# UFBmod_2V2.net
KiCad netlist of a schematic drawn in EAGLE
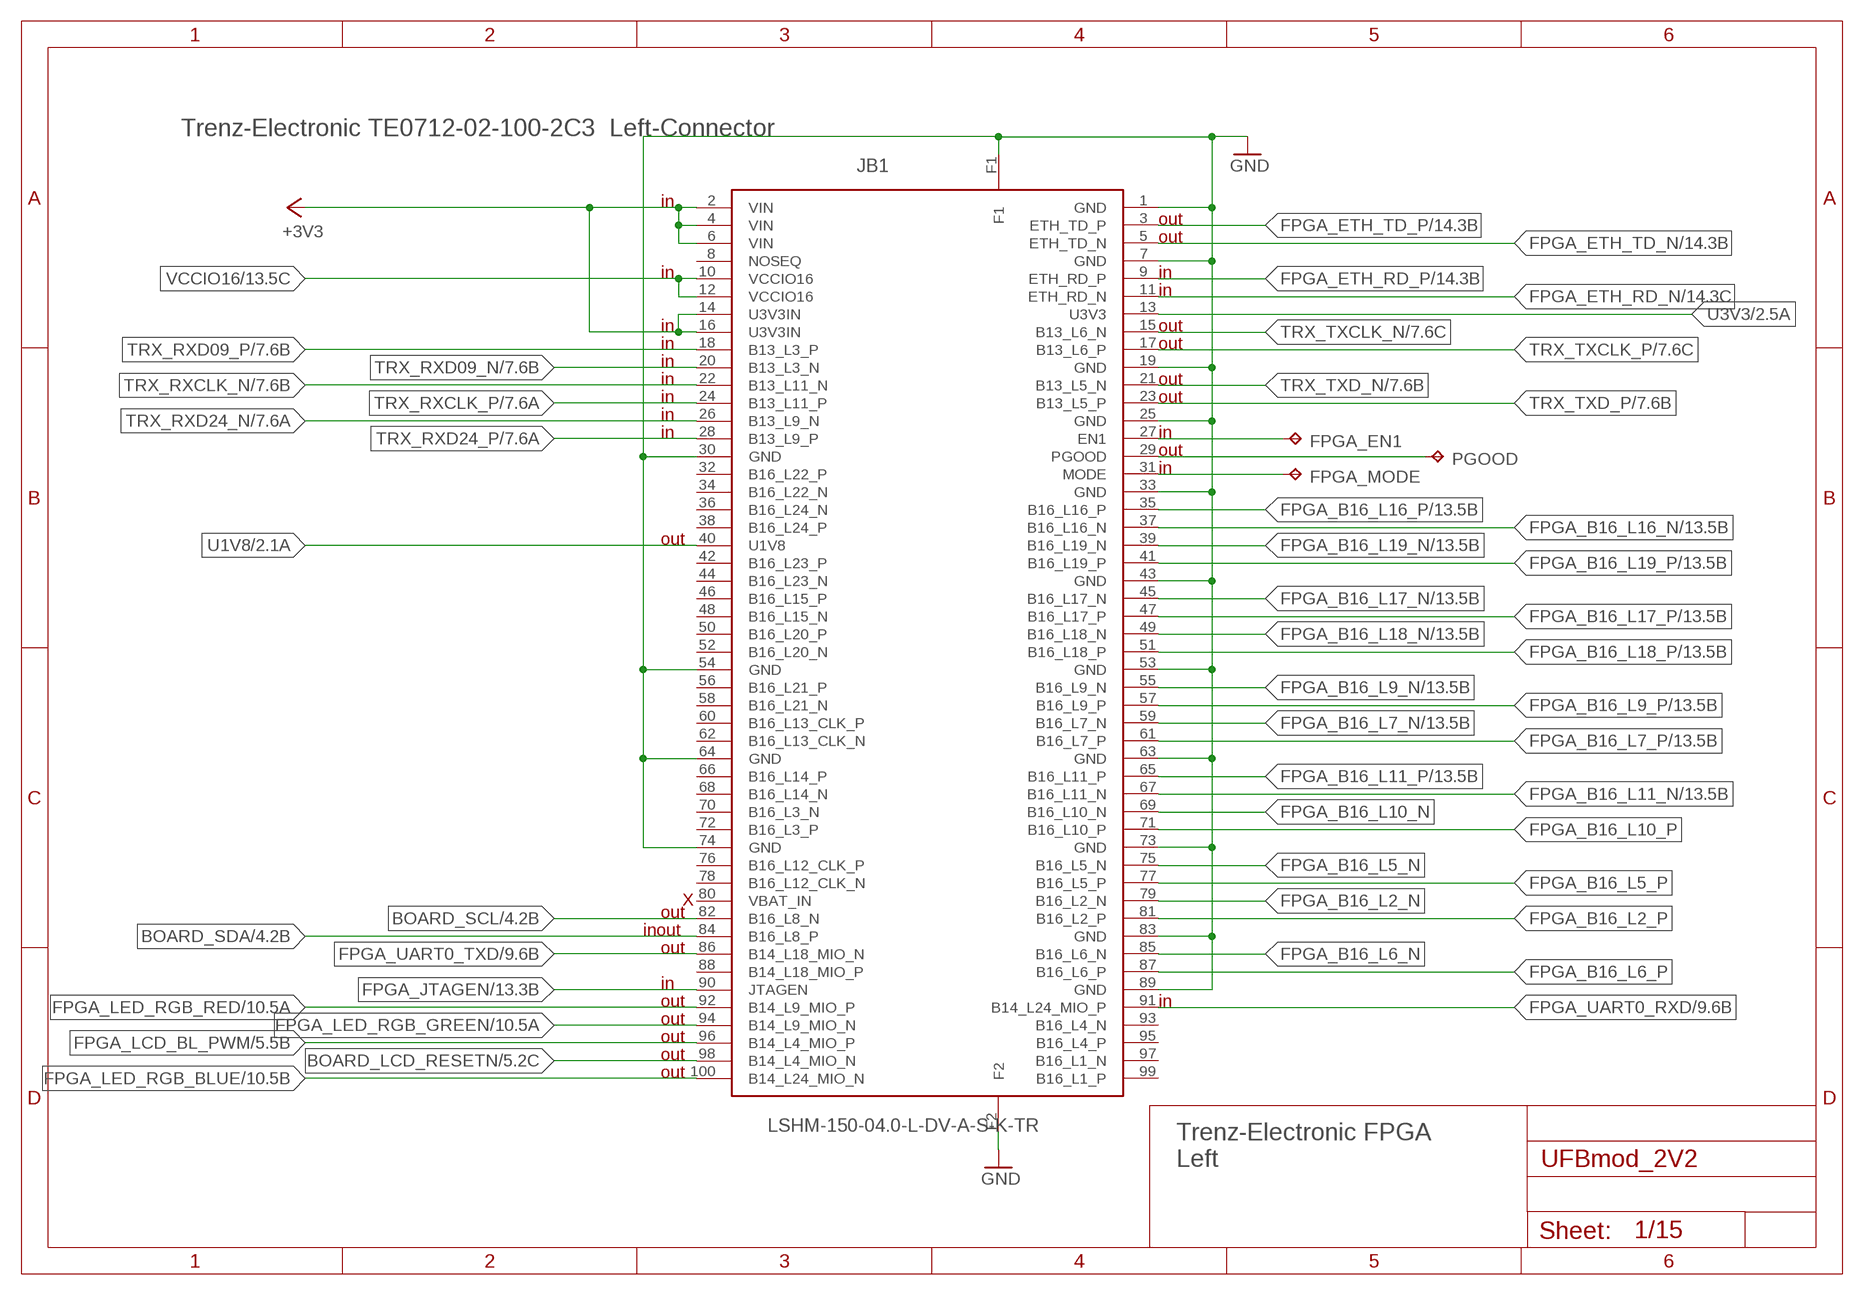
[diagram p0: schematic, sheet 1]
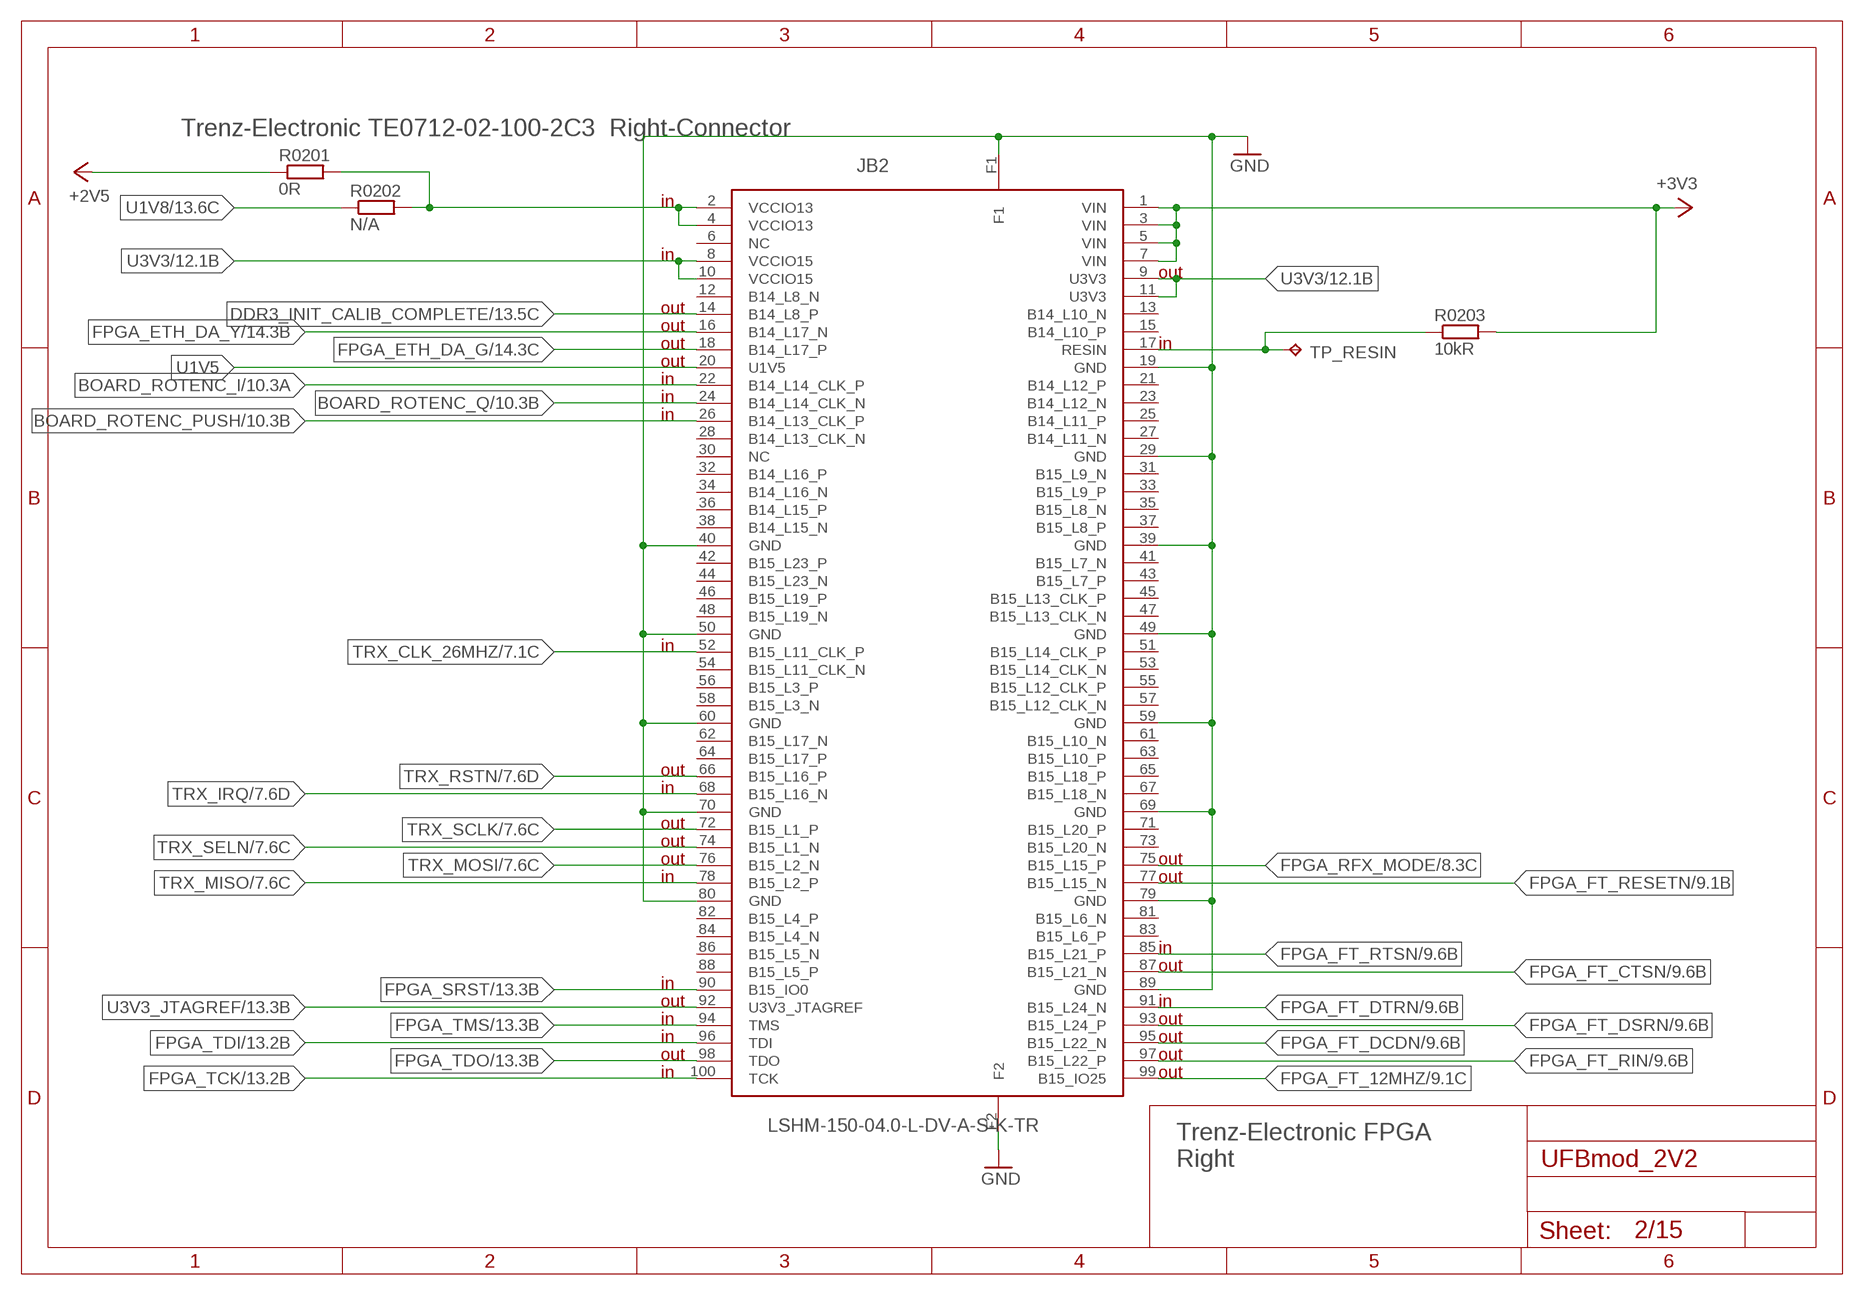
[diagram p1: schematic, sheet 2]
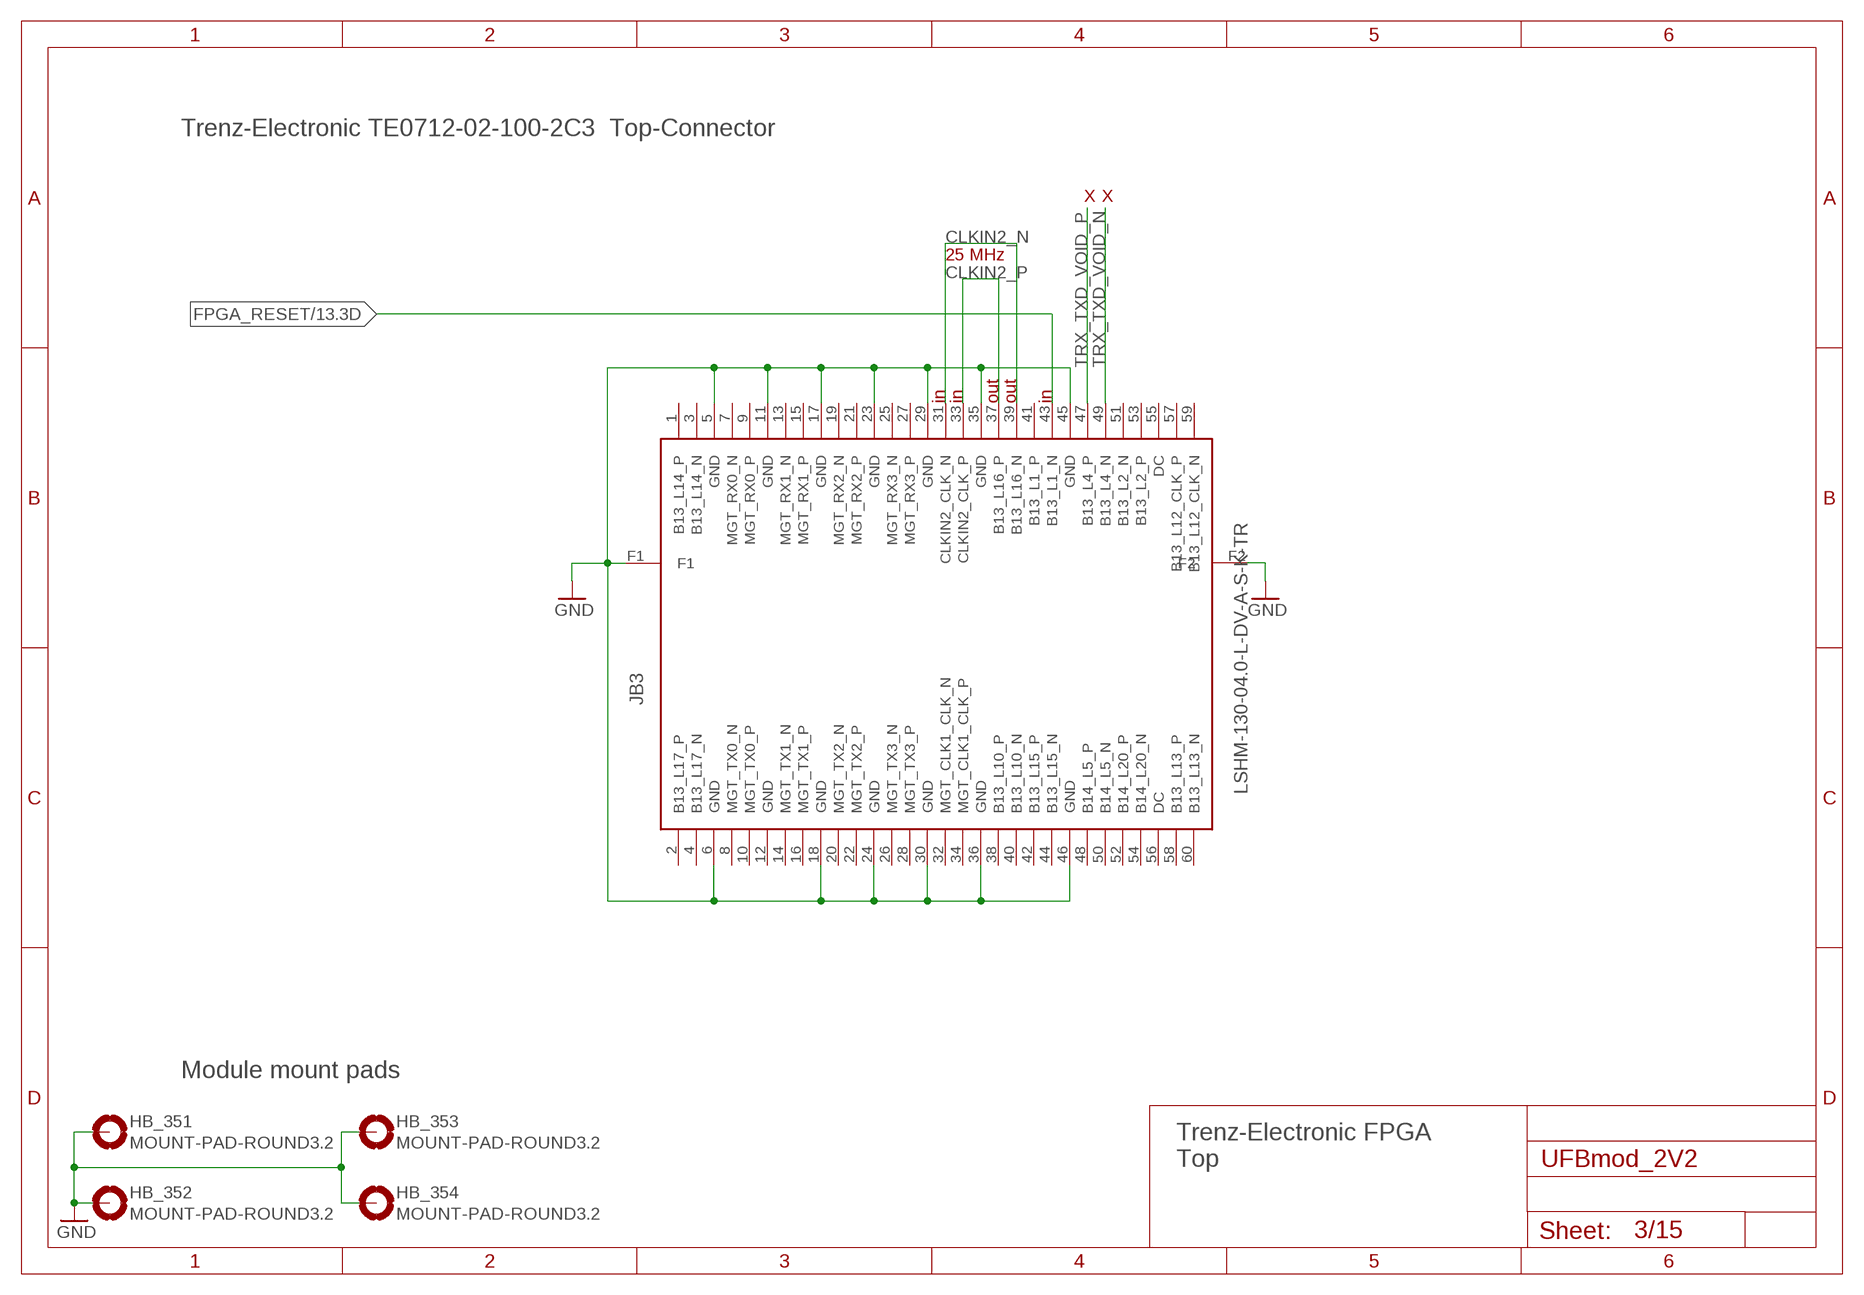
[diagram p2: schematic, sheet 3]
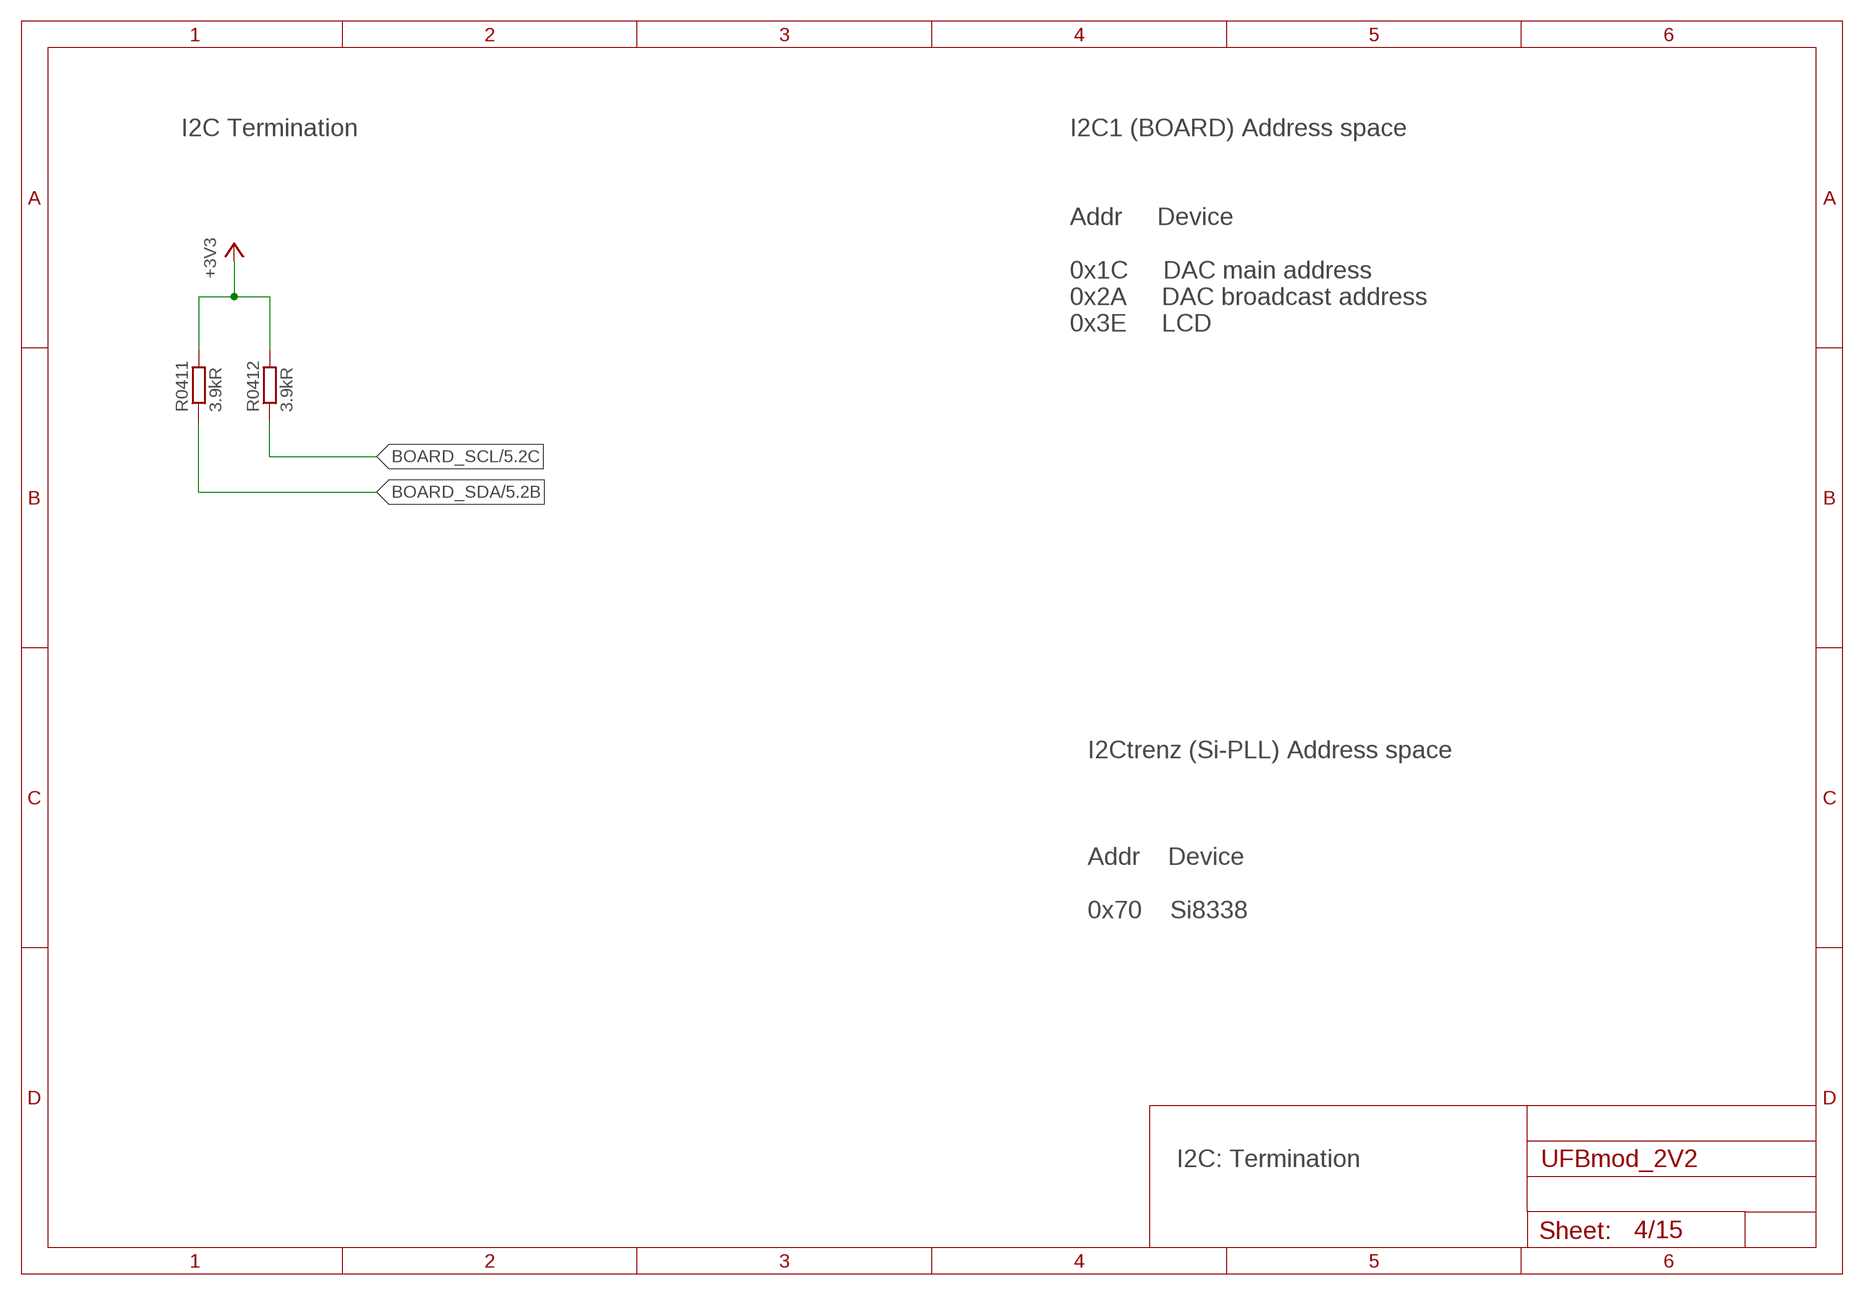
[diagram p3: schematic, sheet 4]
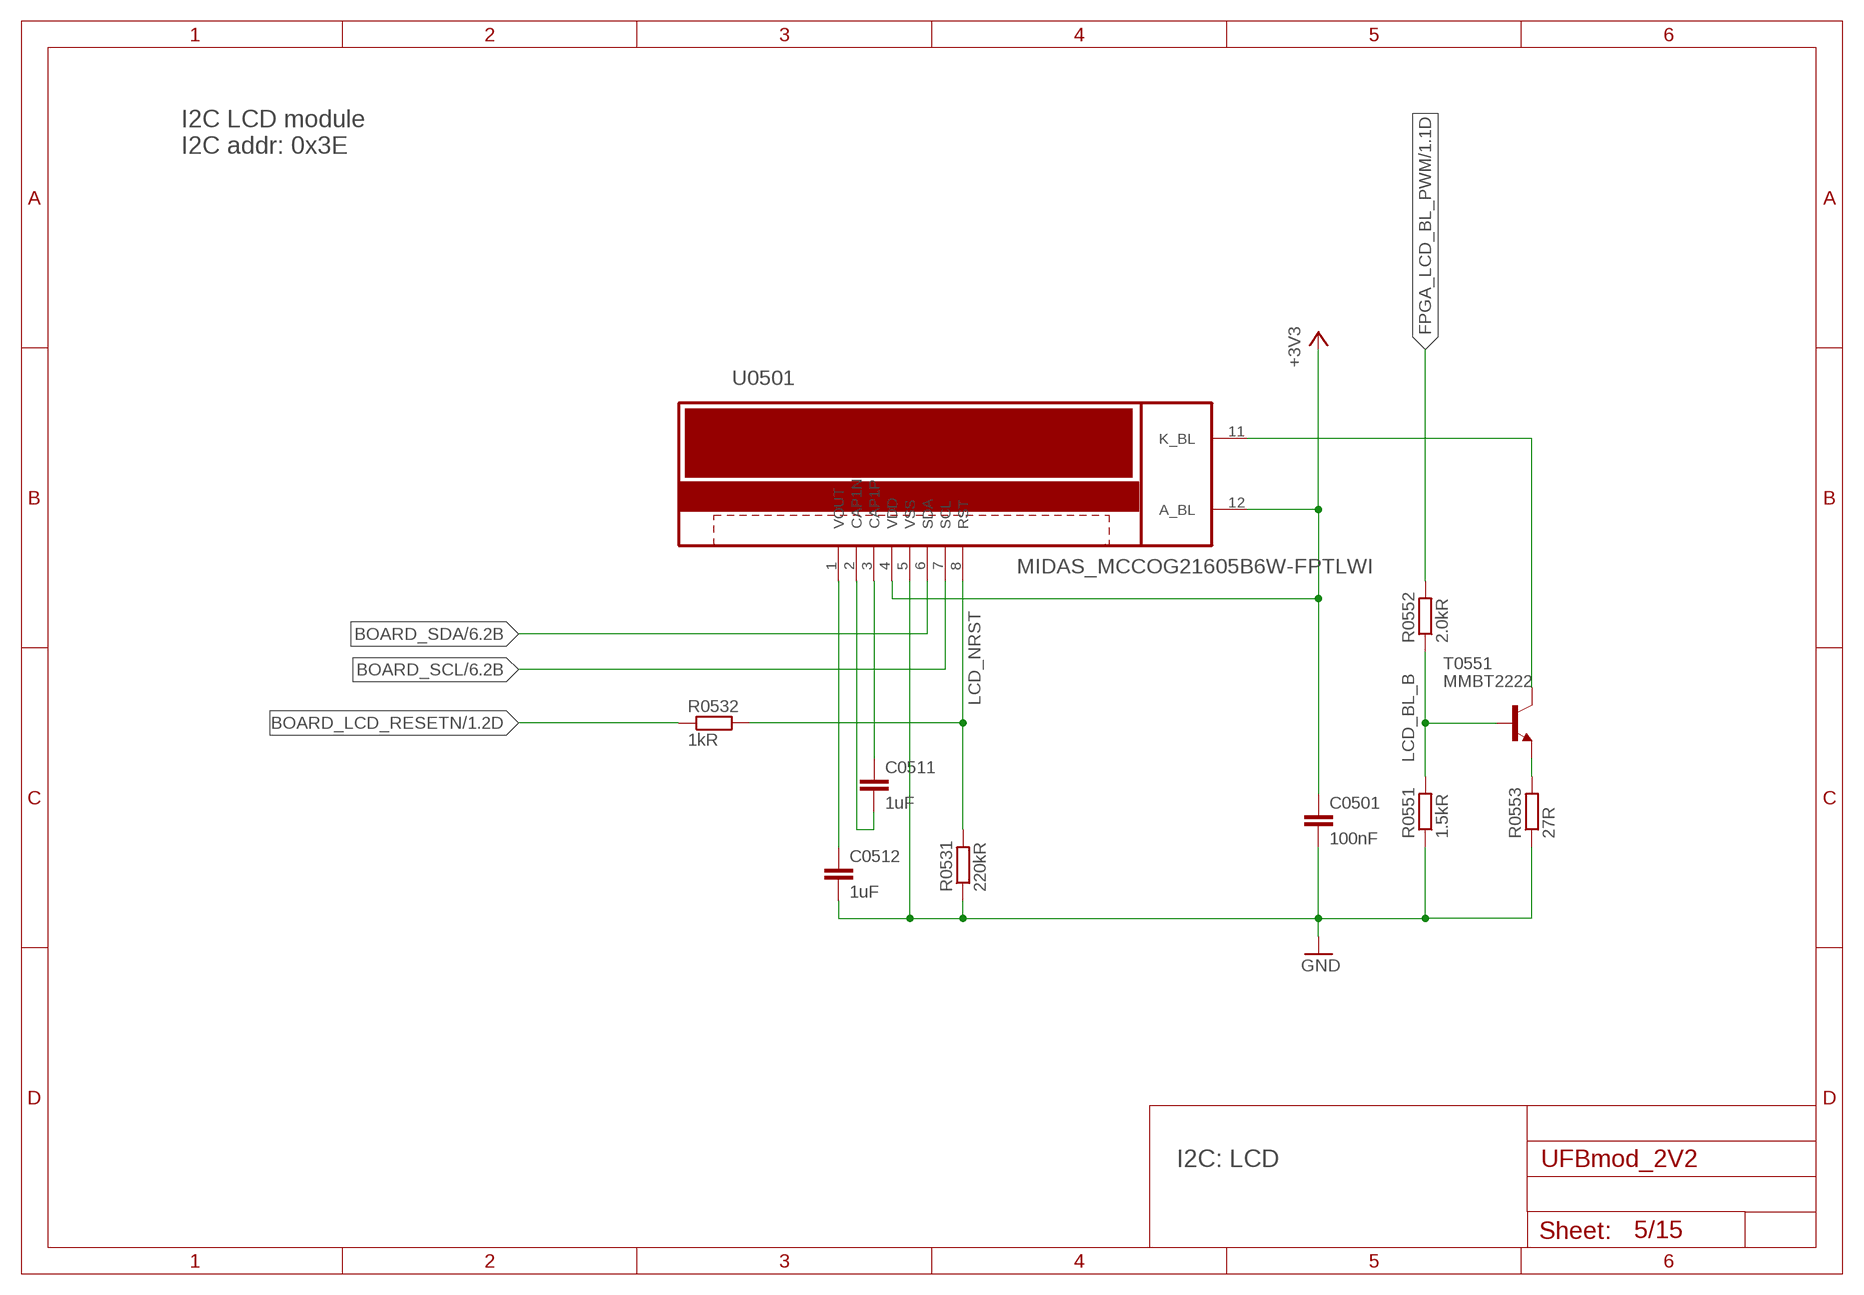
[diagram p4: schematic, sheet 5]
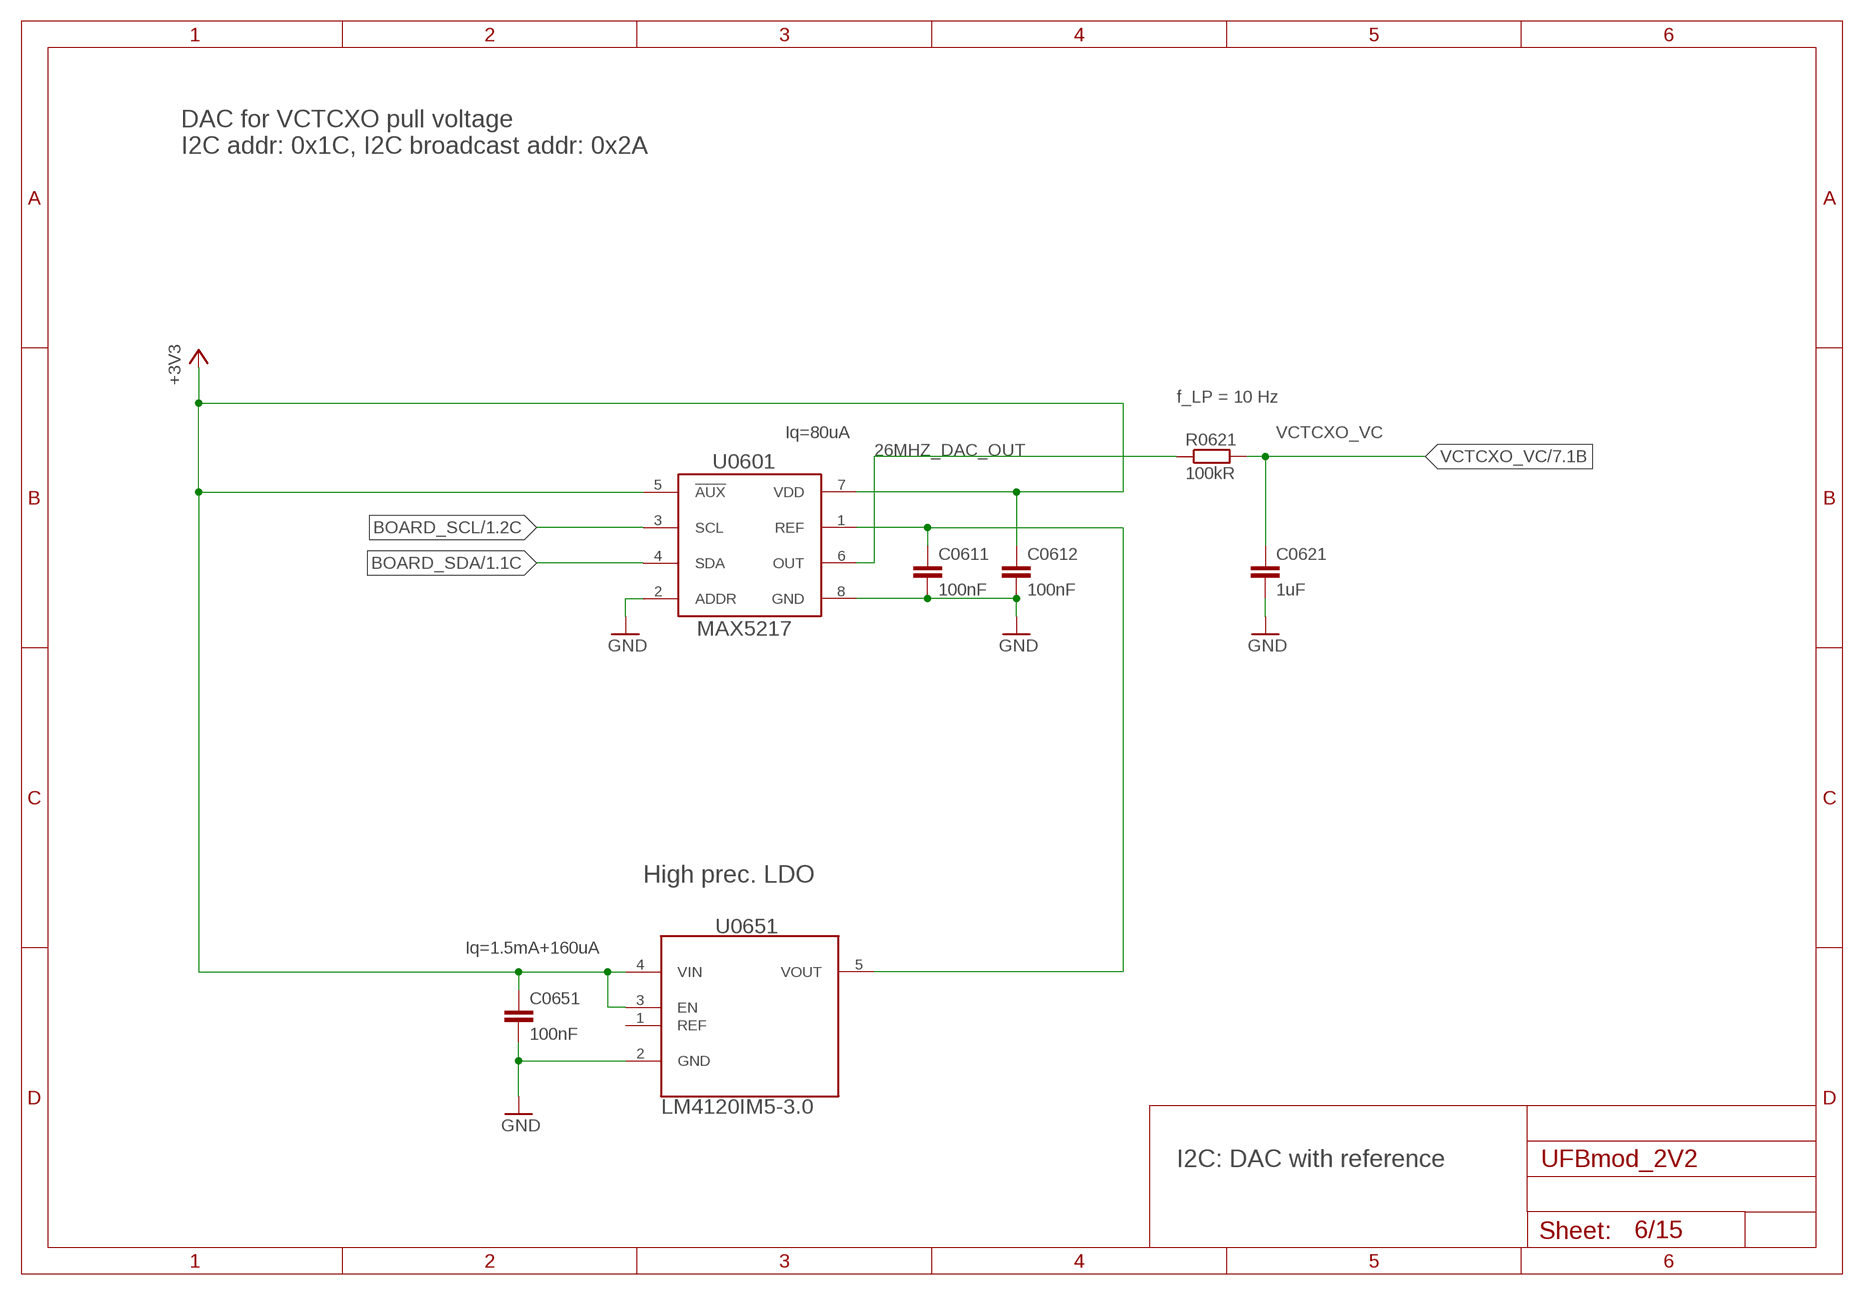
[diagram p5: schematic, sheet 6]
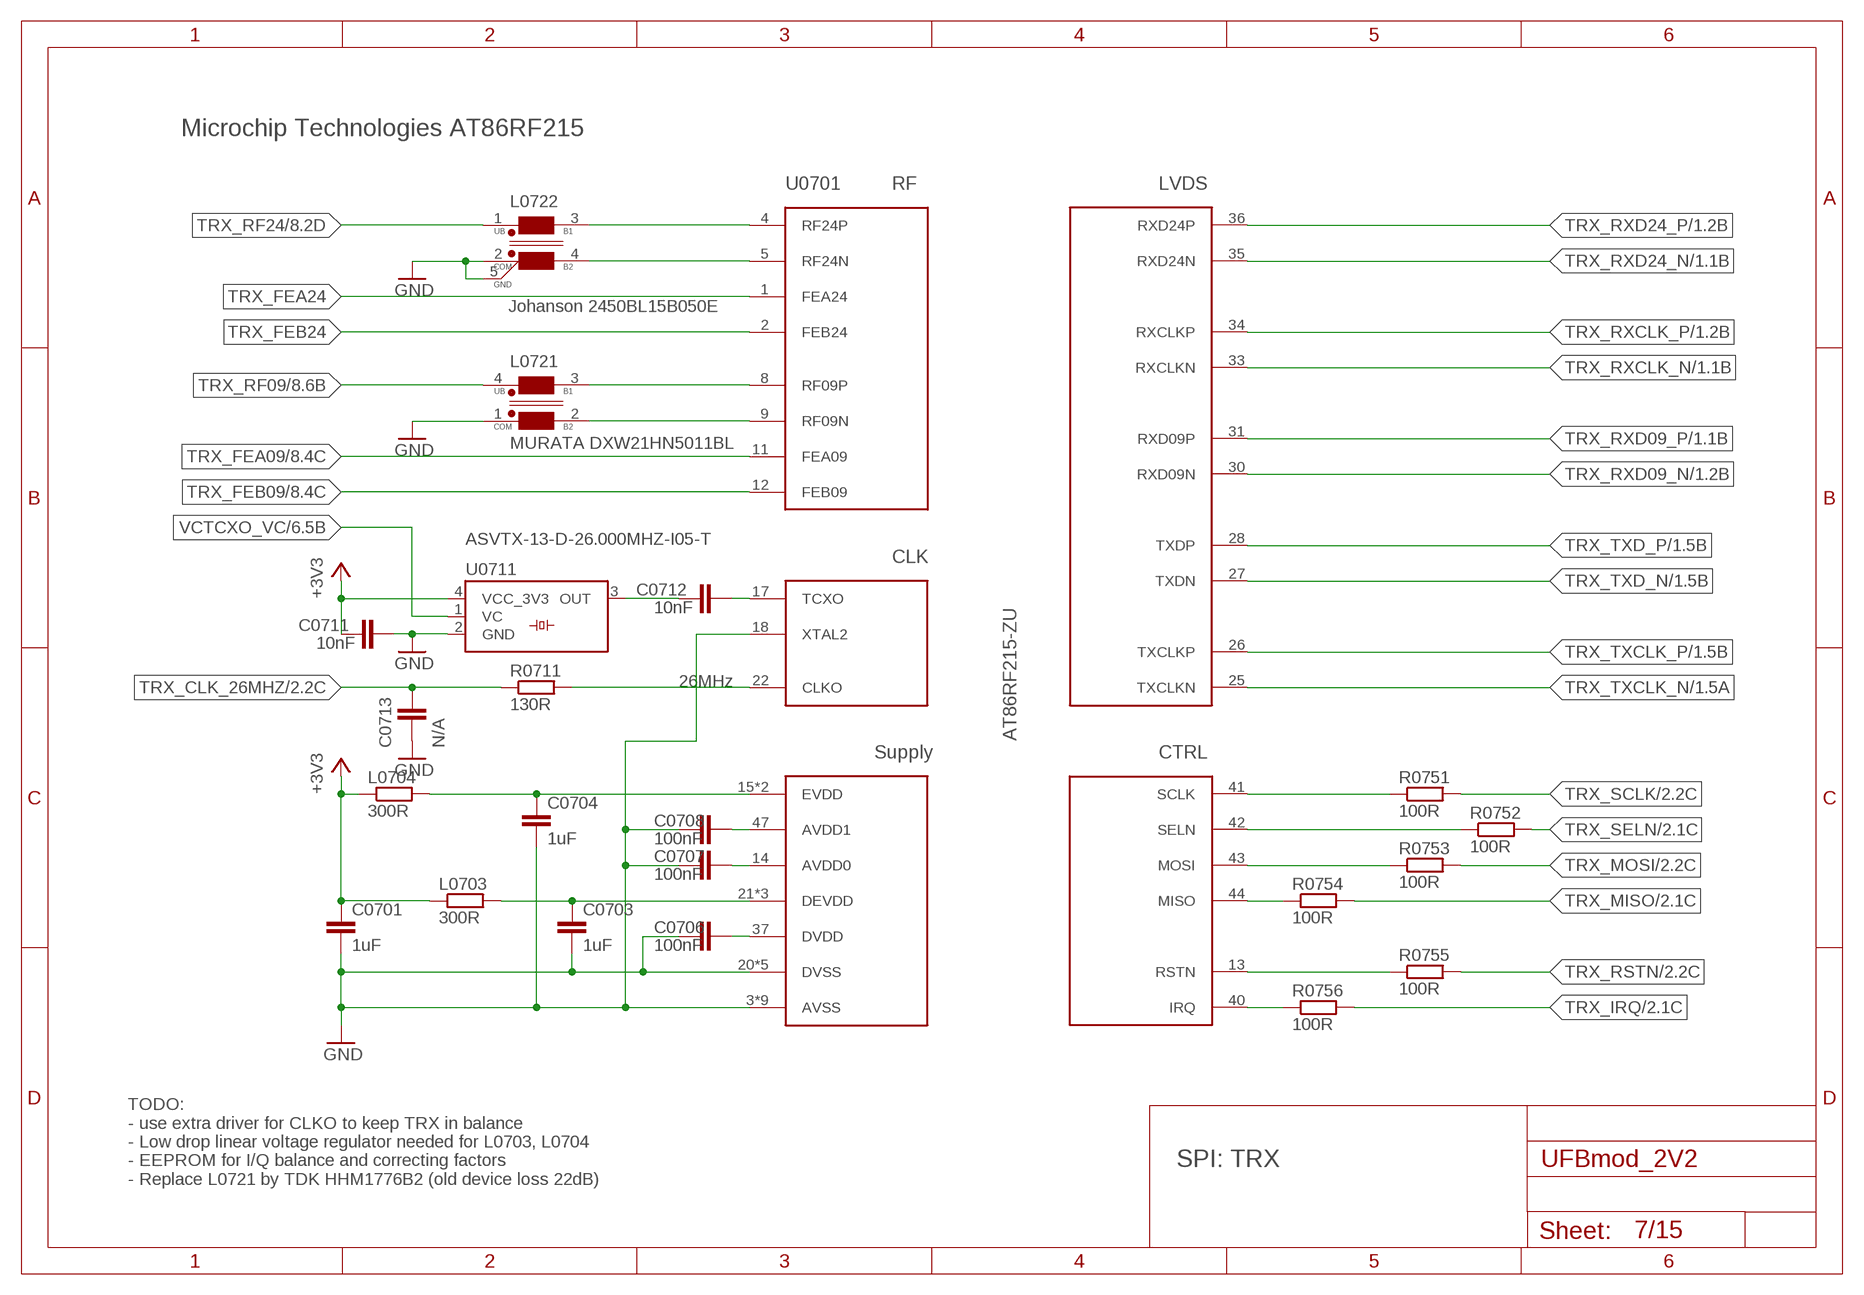
[diagram p6: schematic, sheet 7]
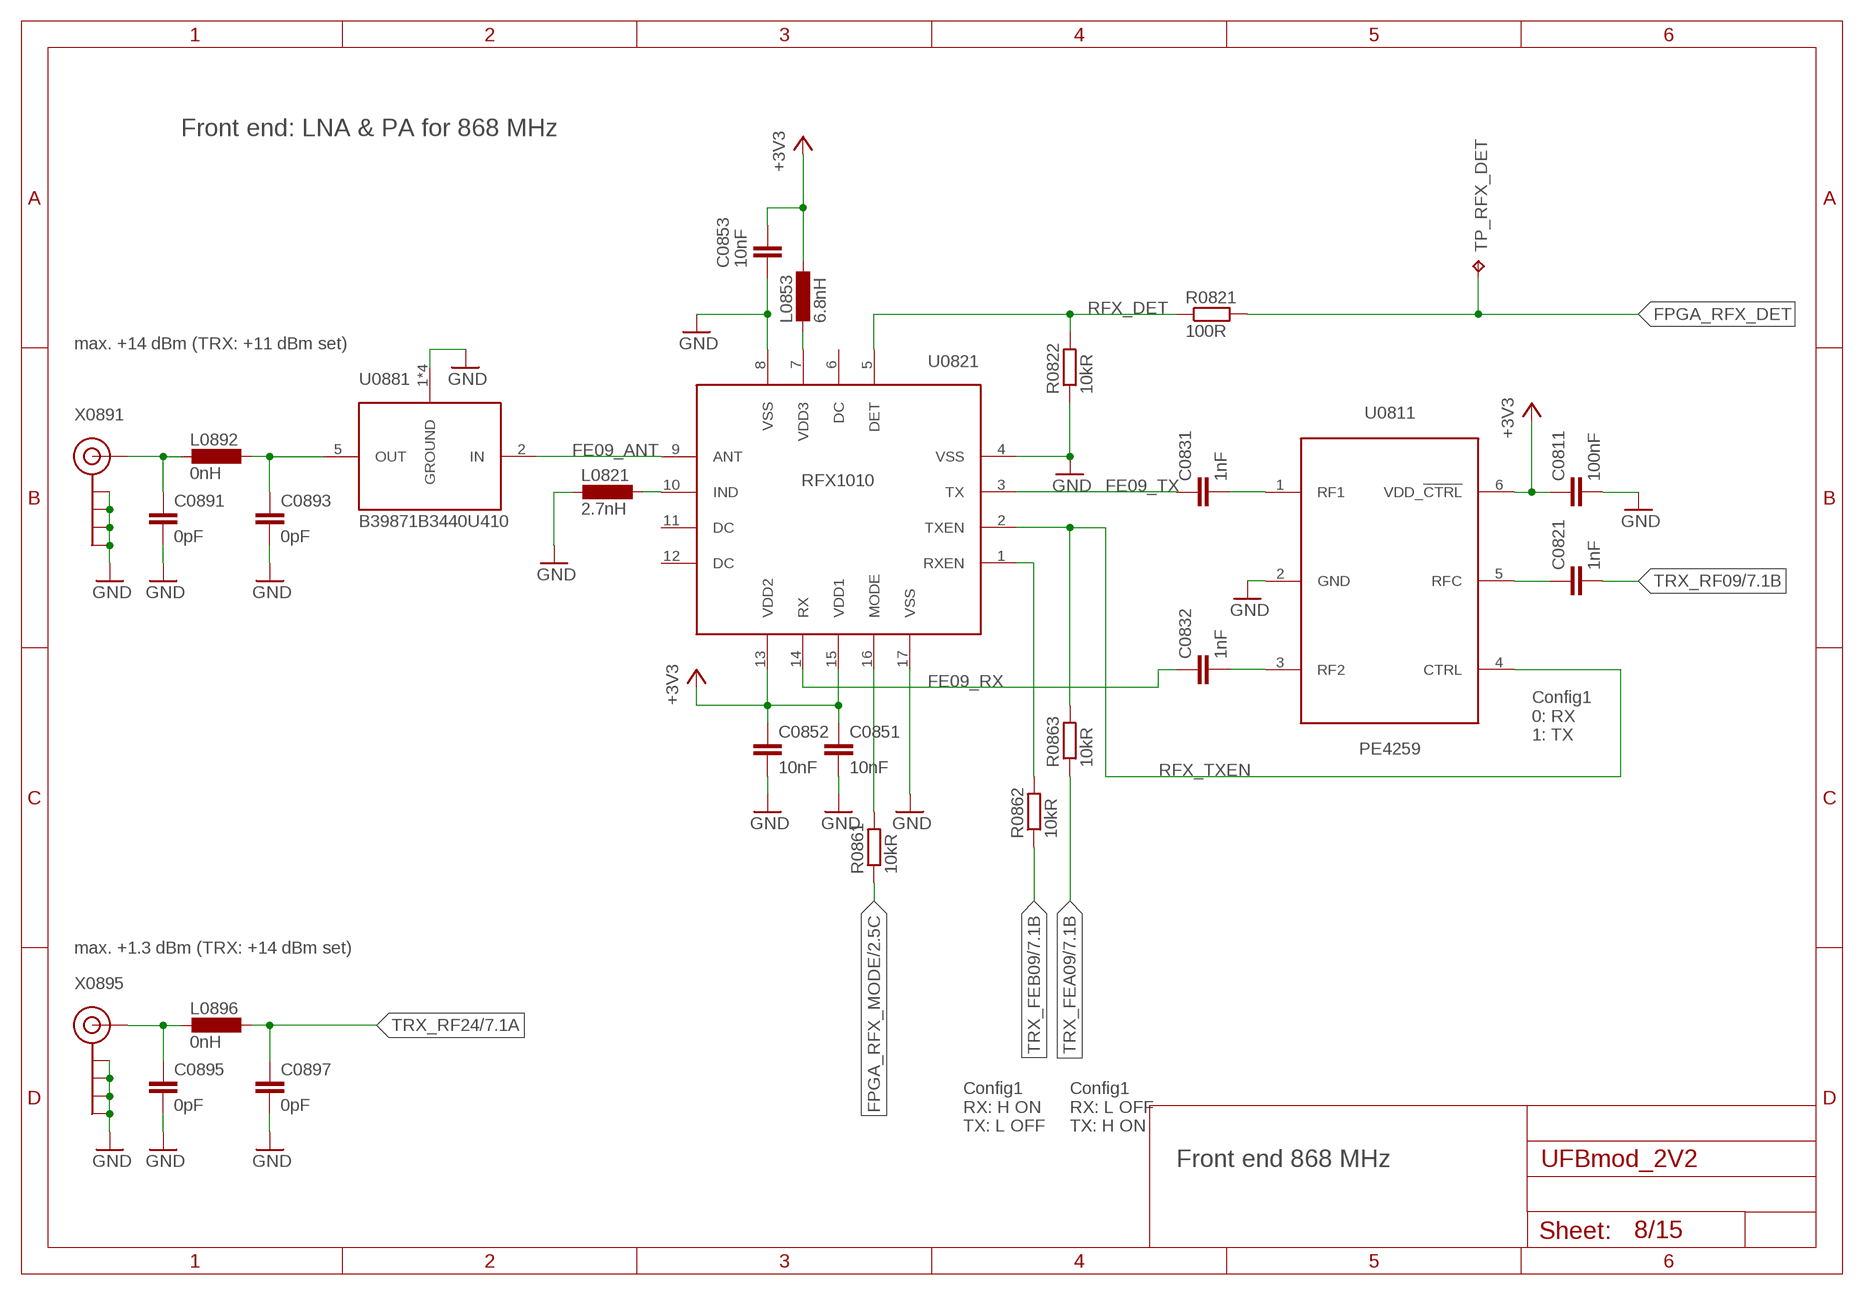
[diagram p7: schematic, sheet 8]
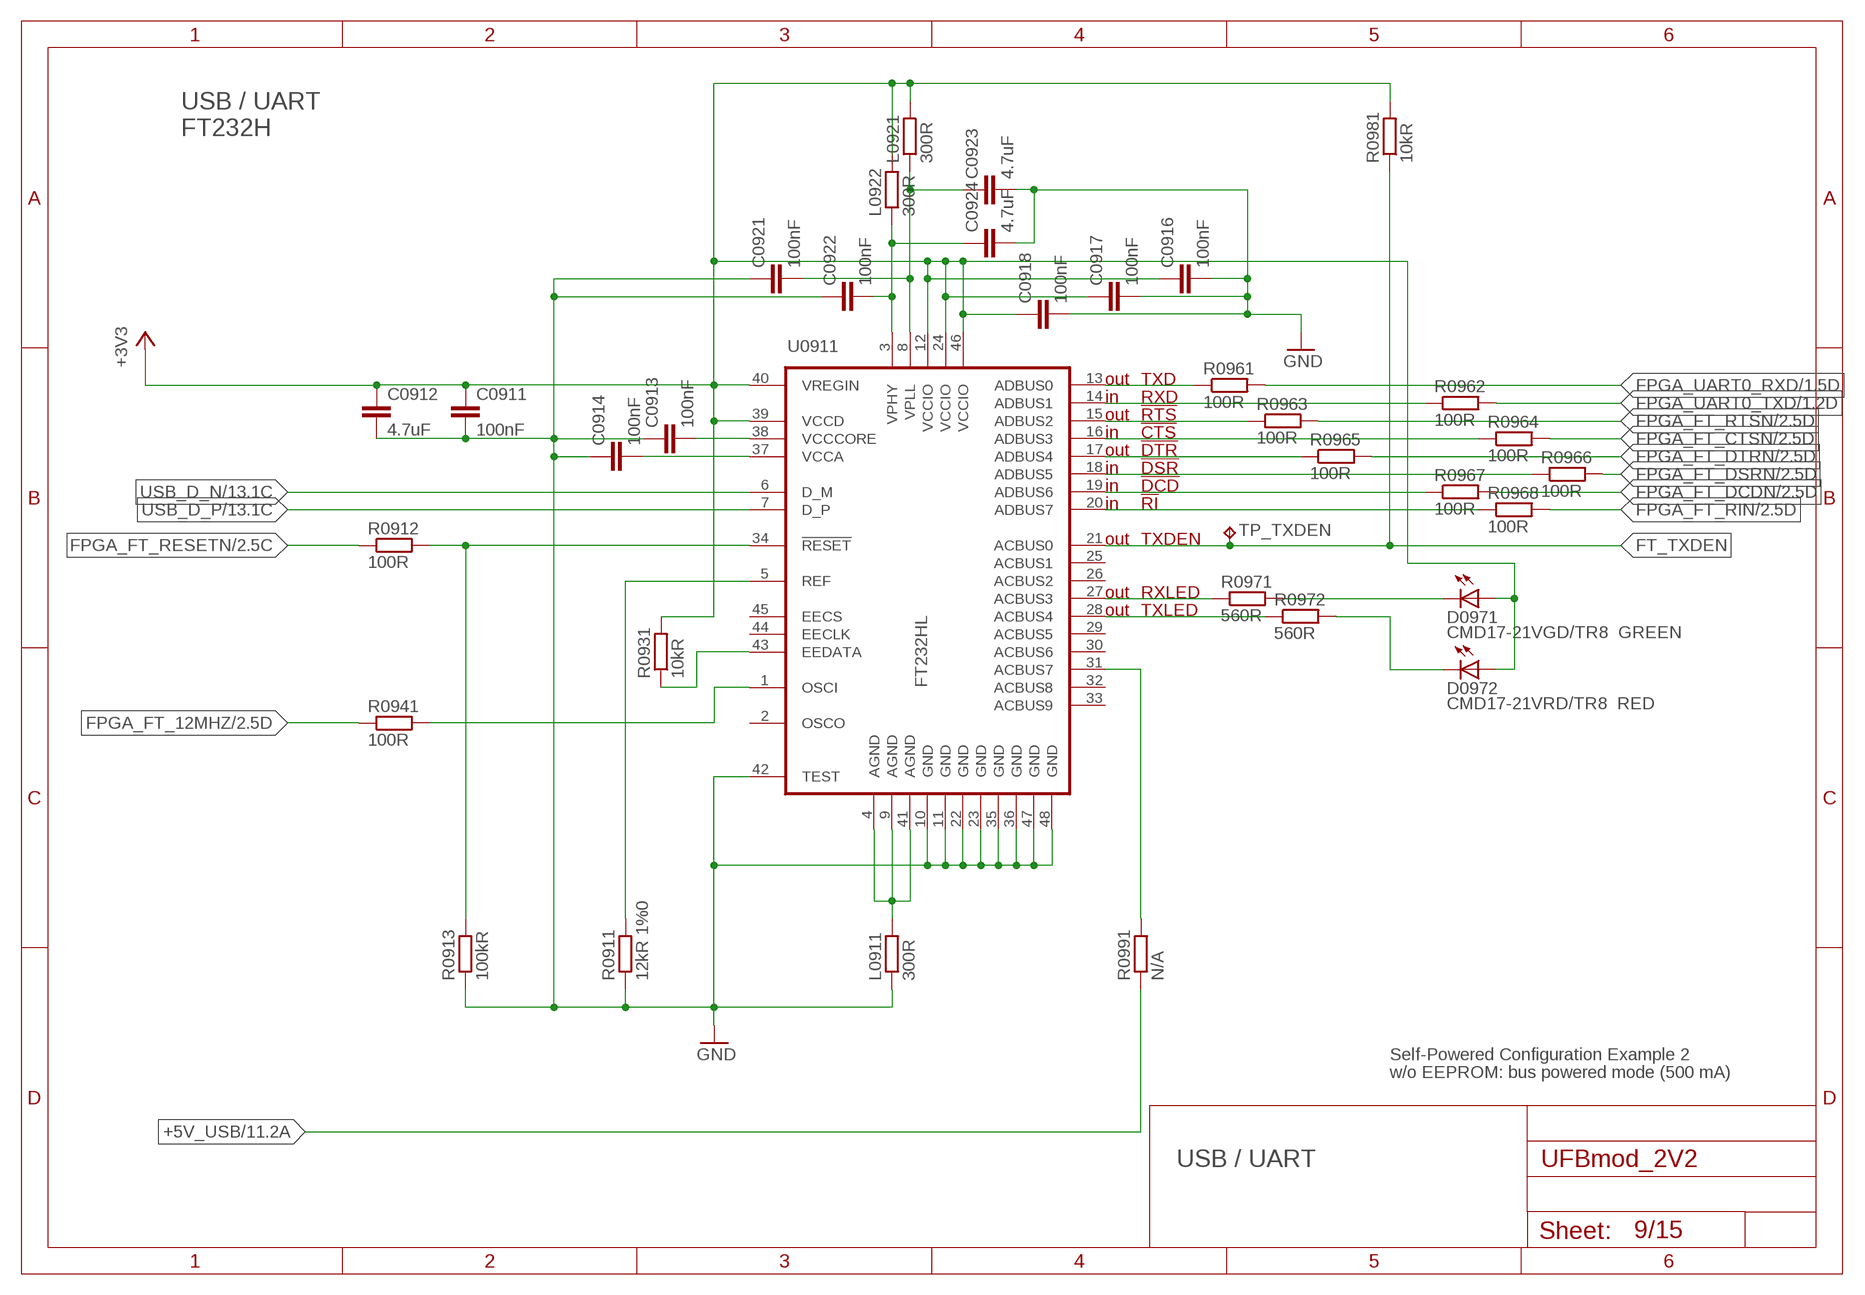
[diagram p8: schematic, sheet 9]
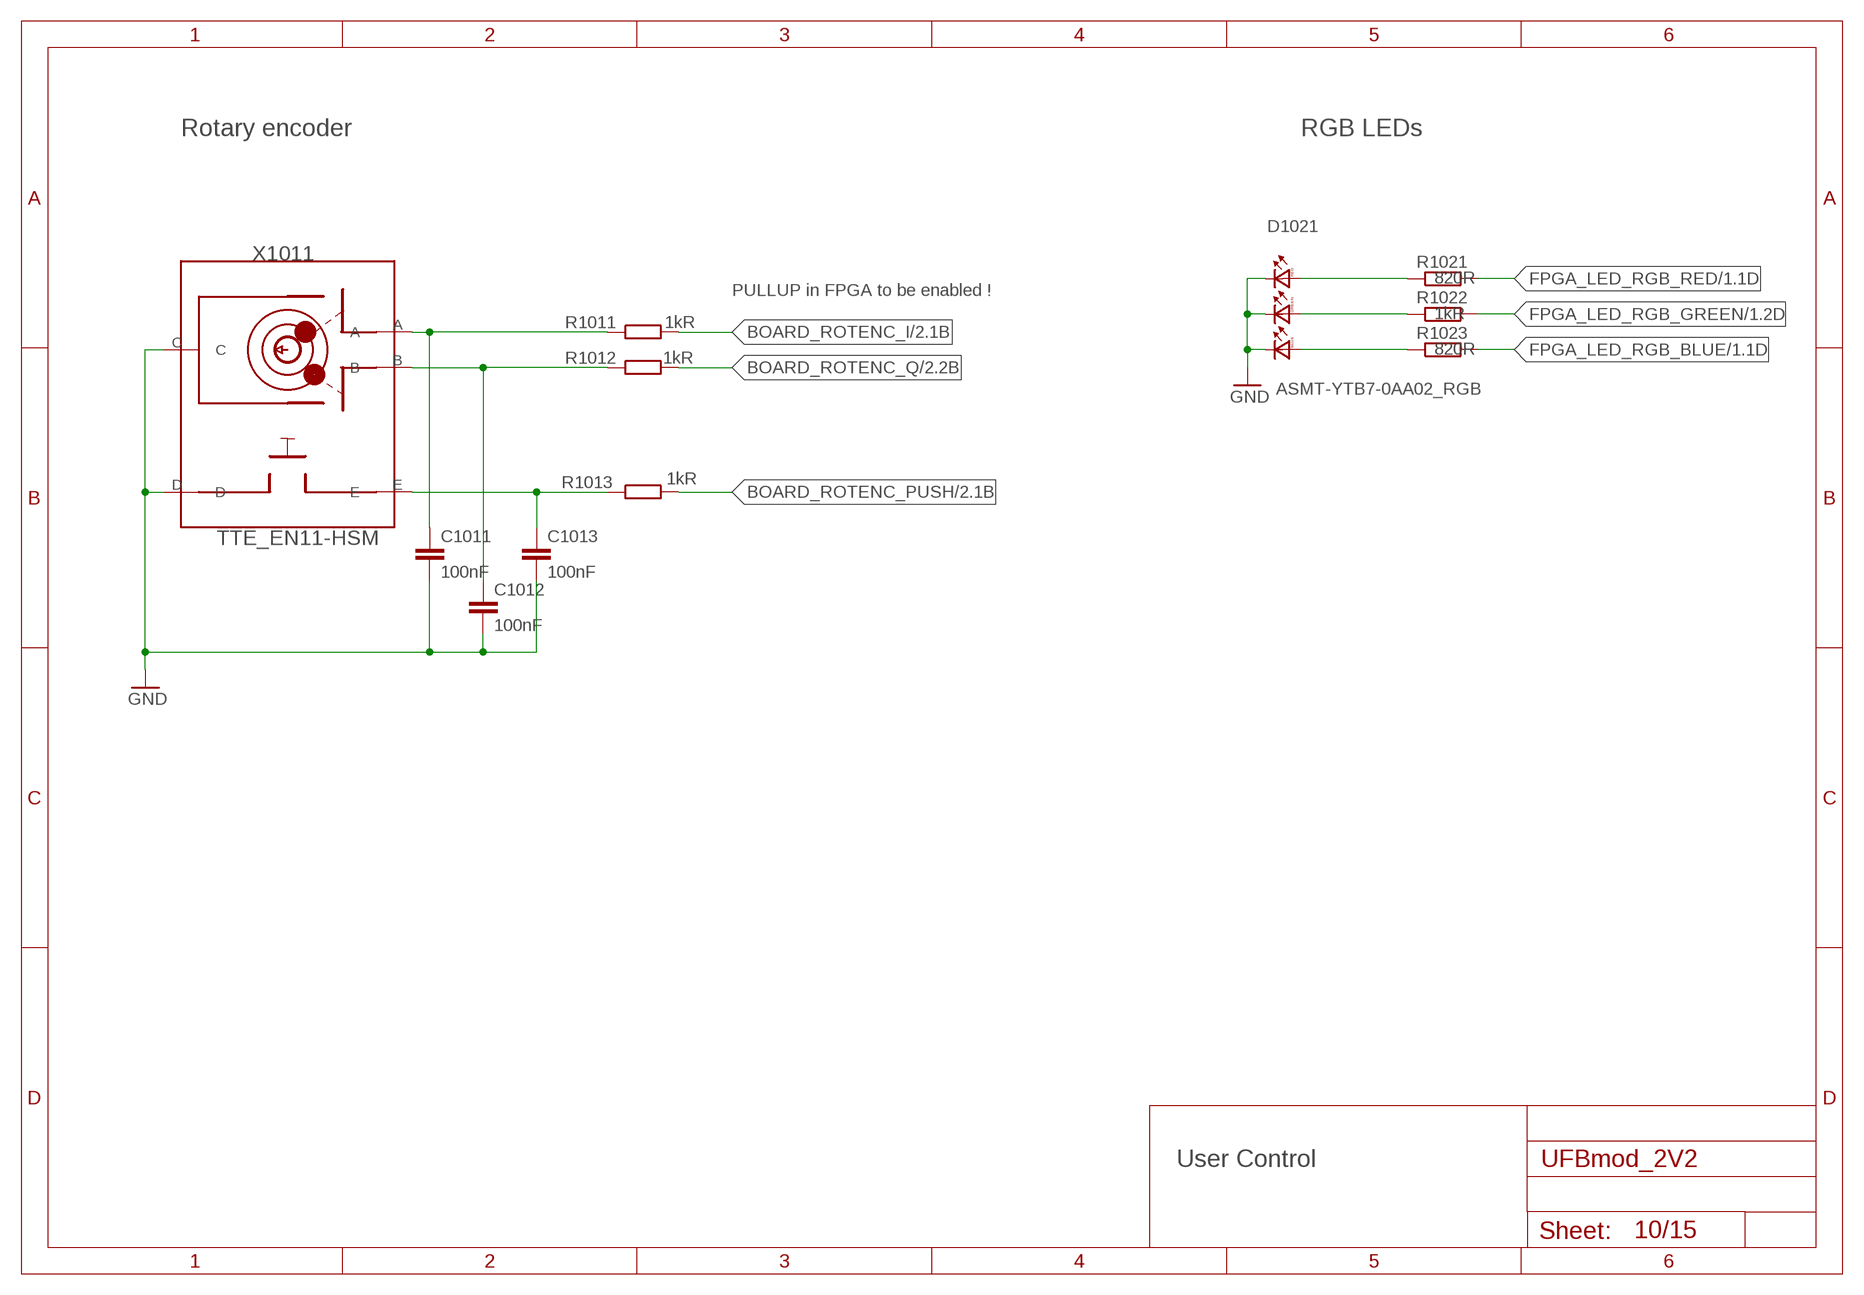
[diagram p9: schematic, sheet 10]
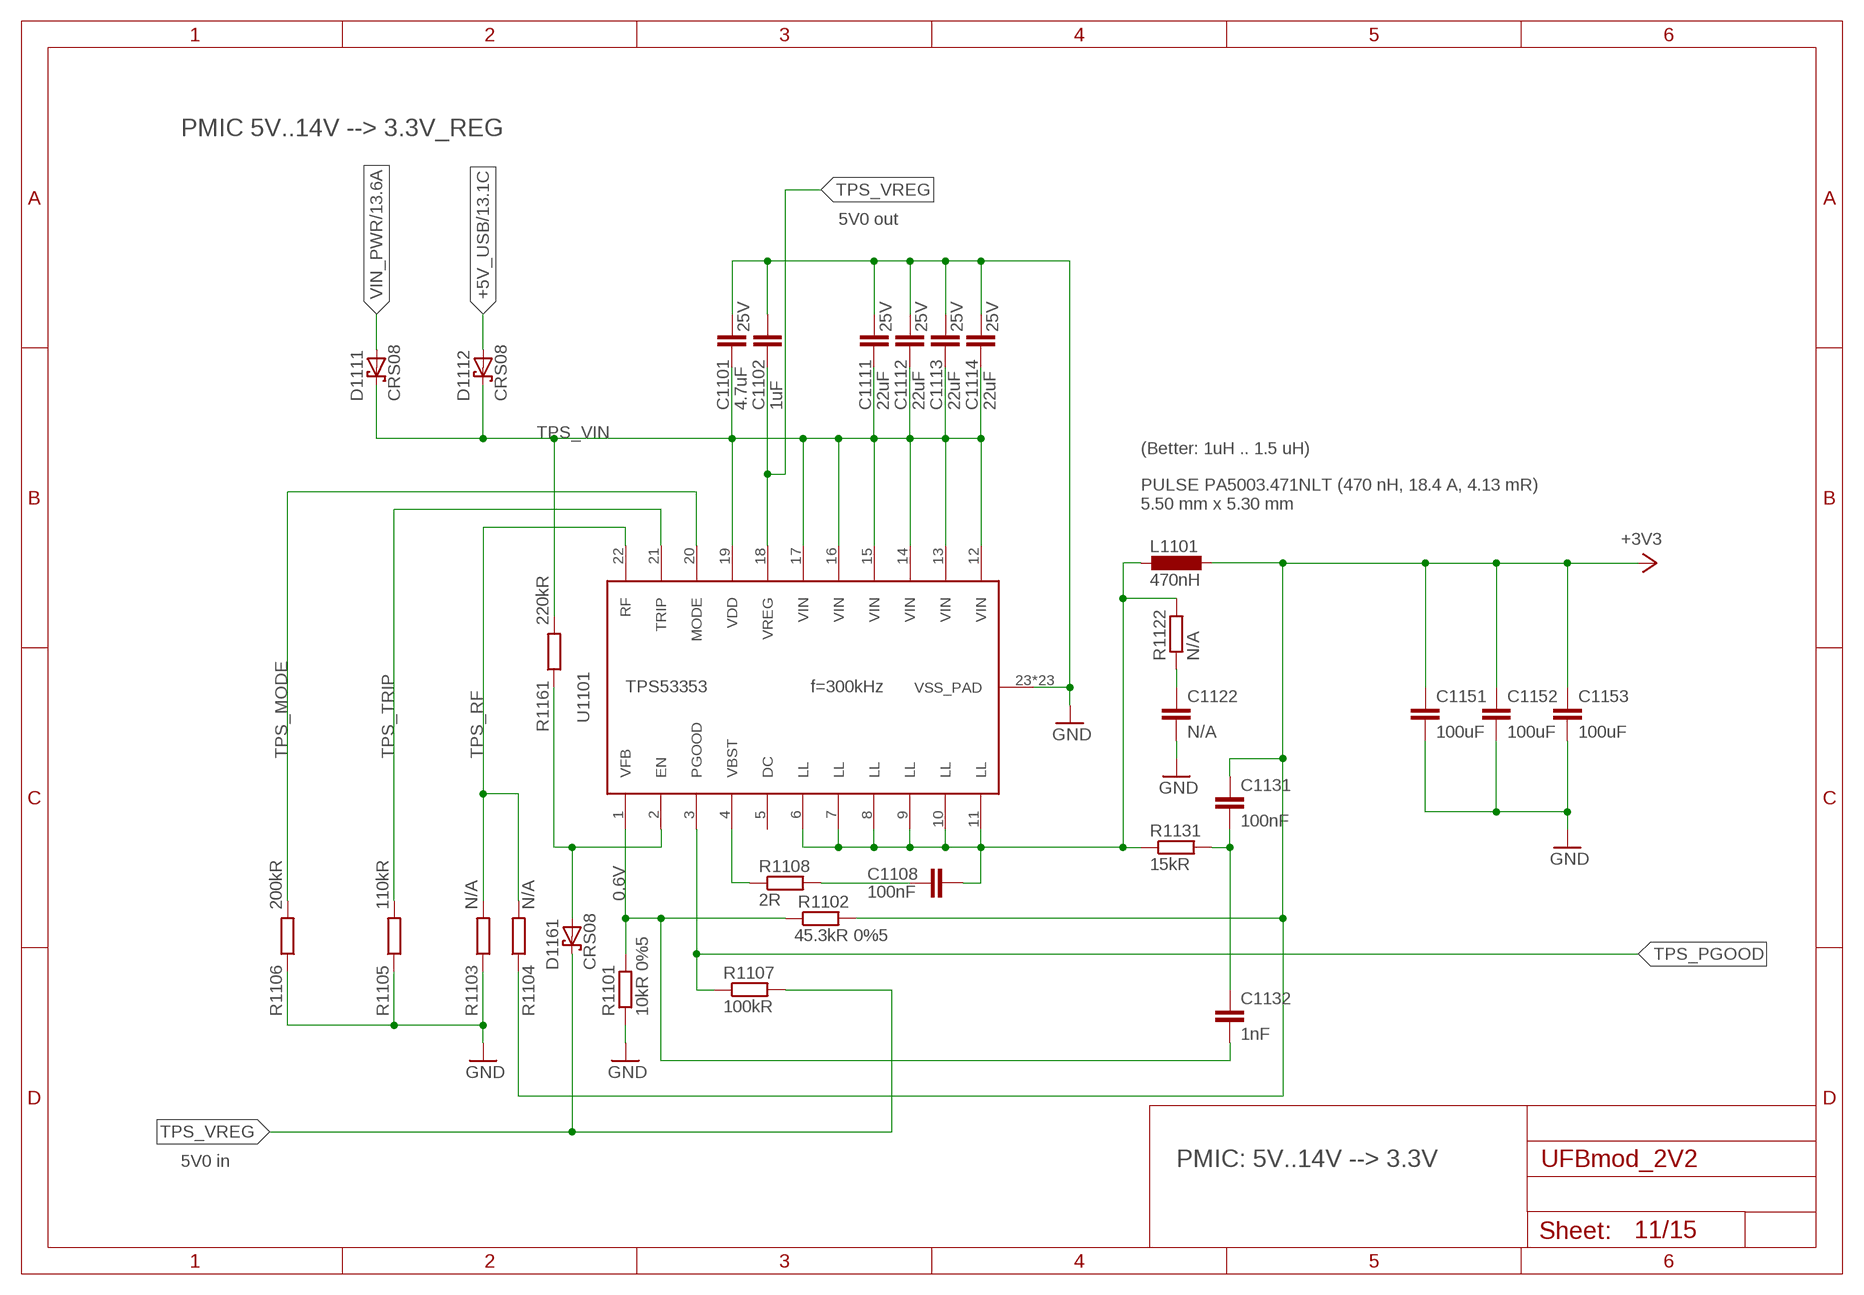
[diagram p10: schematic, sheet 11]
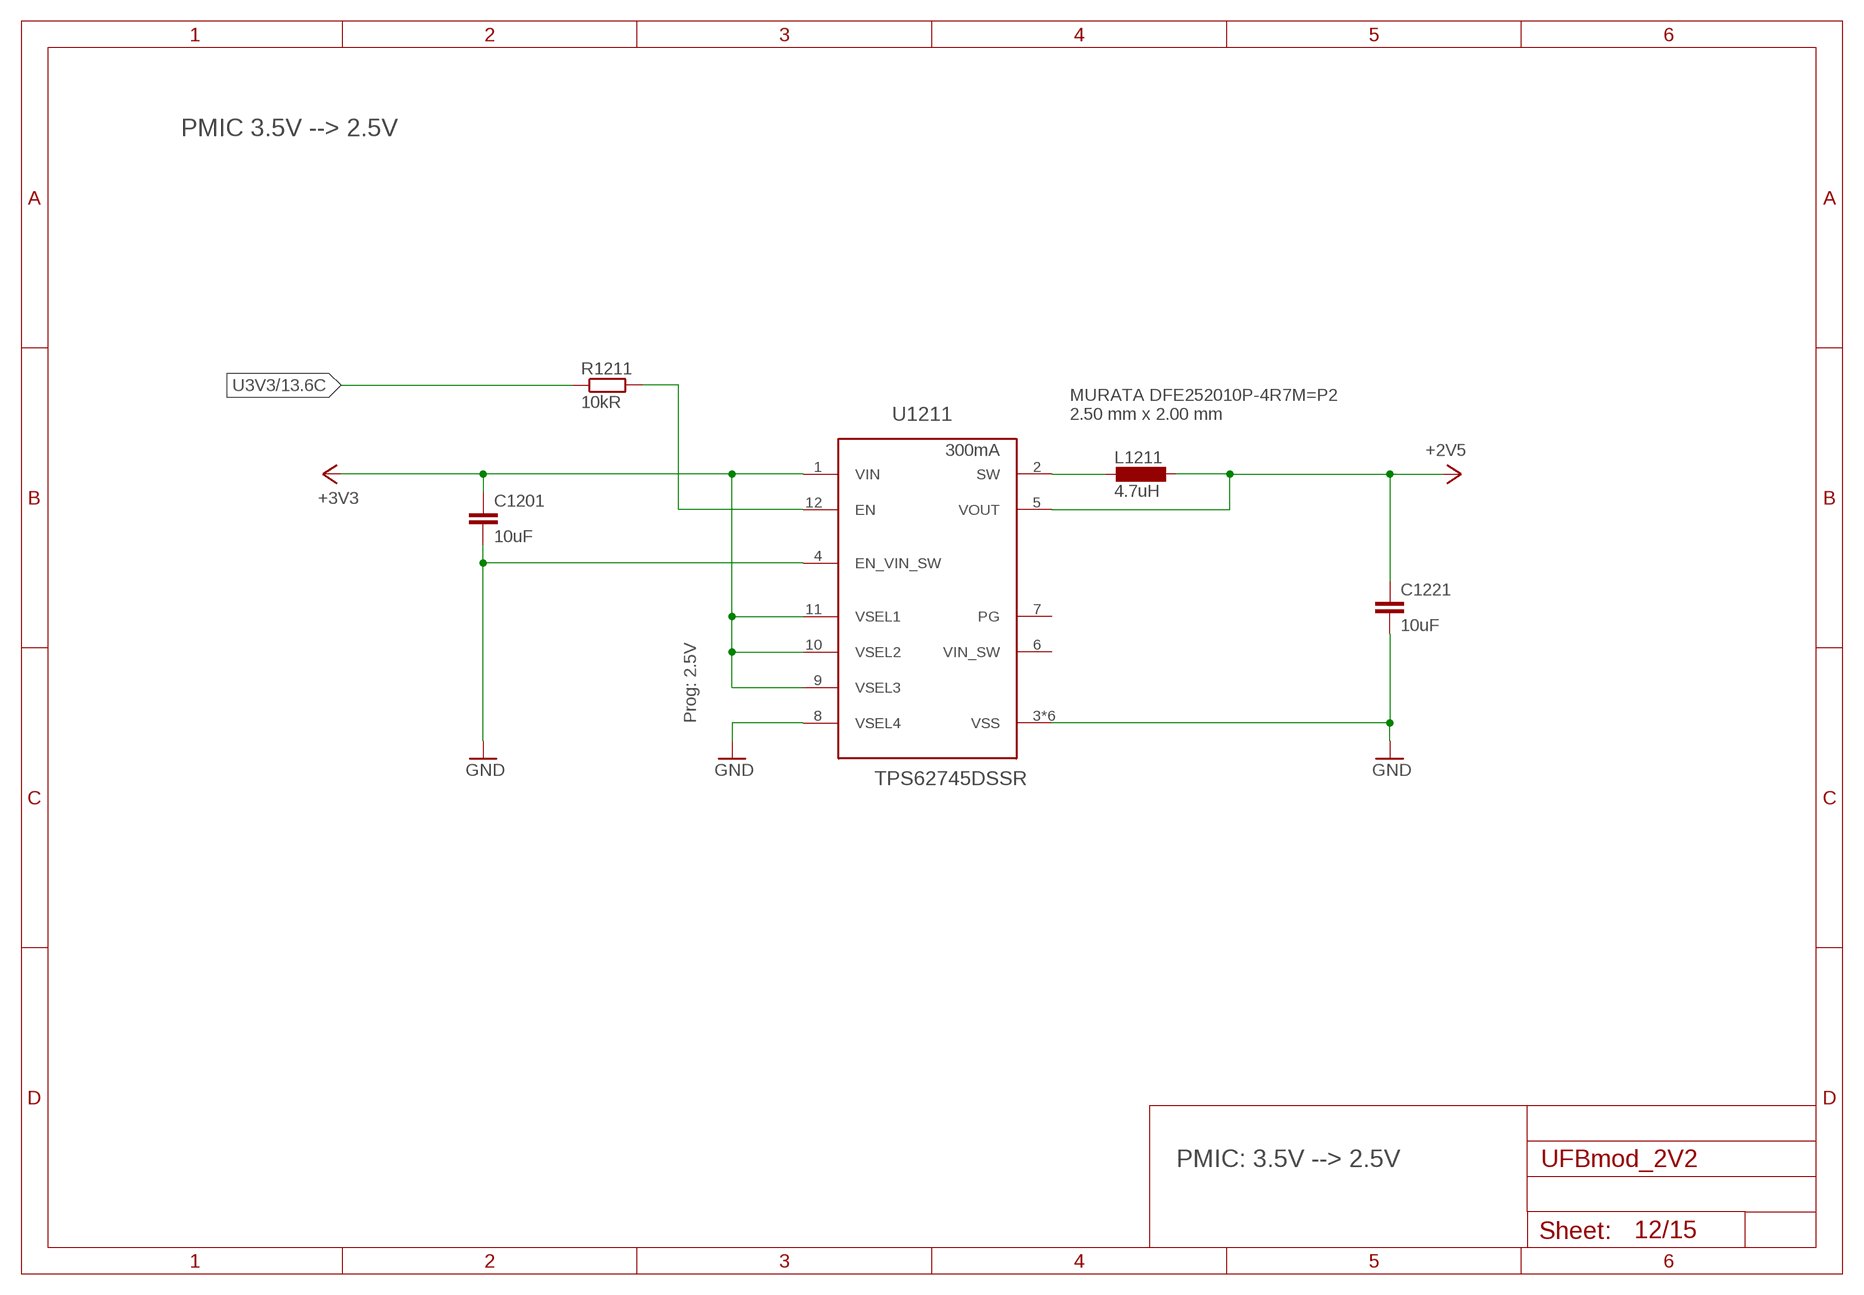
[diagram p11: schematic, sheet 12]
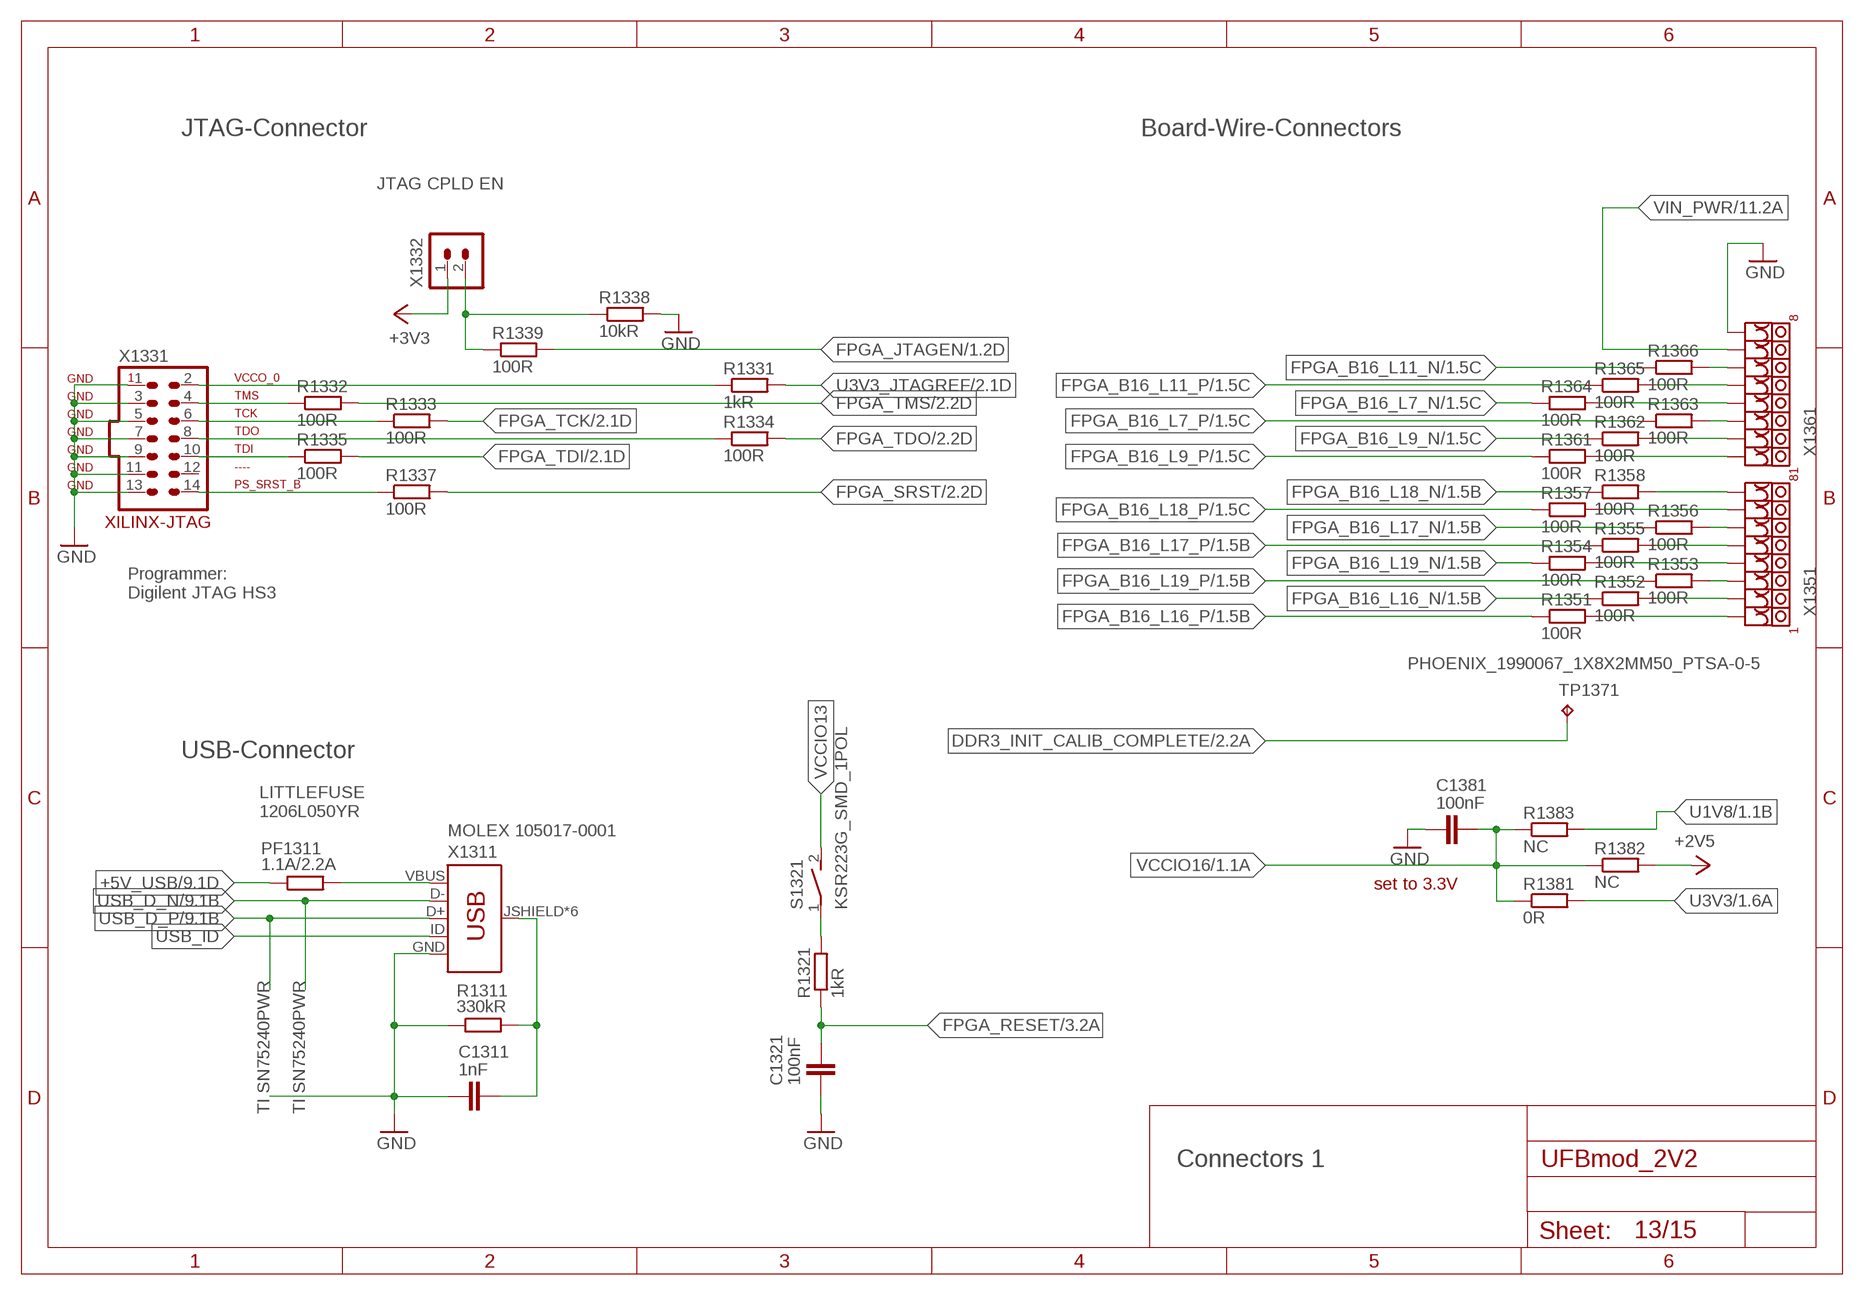
[diagram p12: schematic, sheet 13]
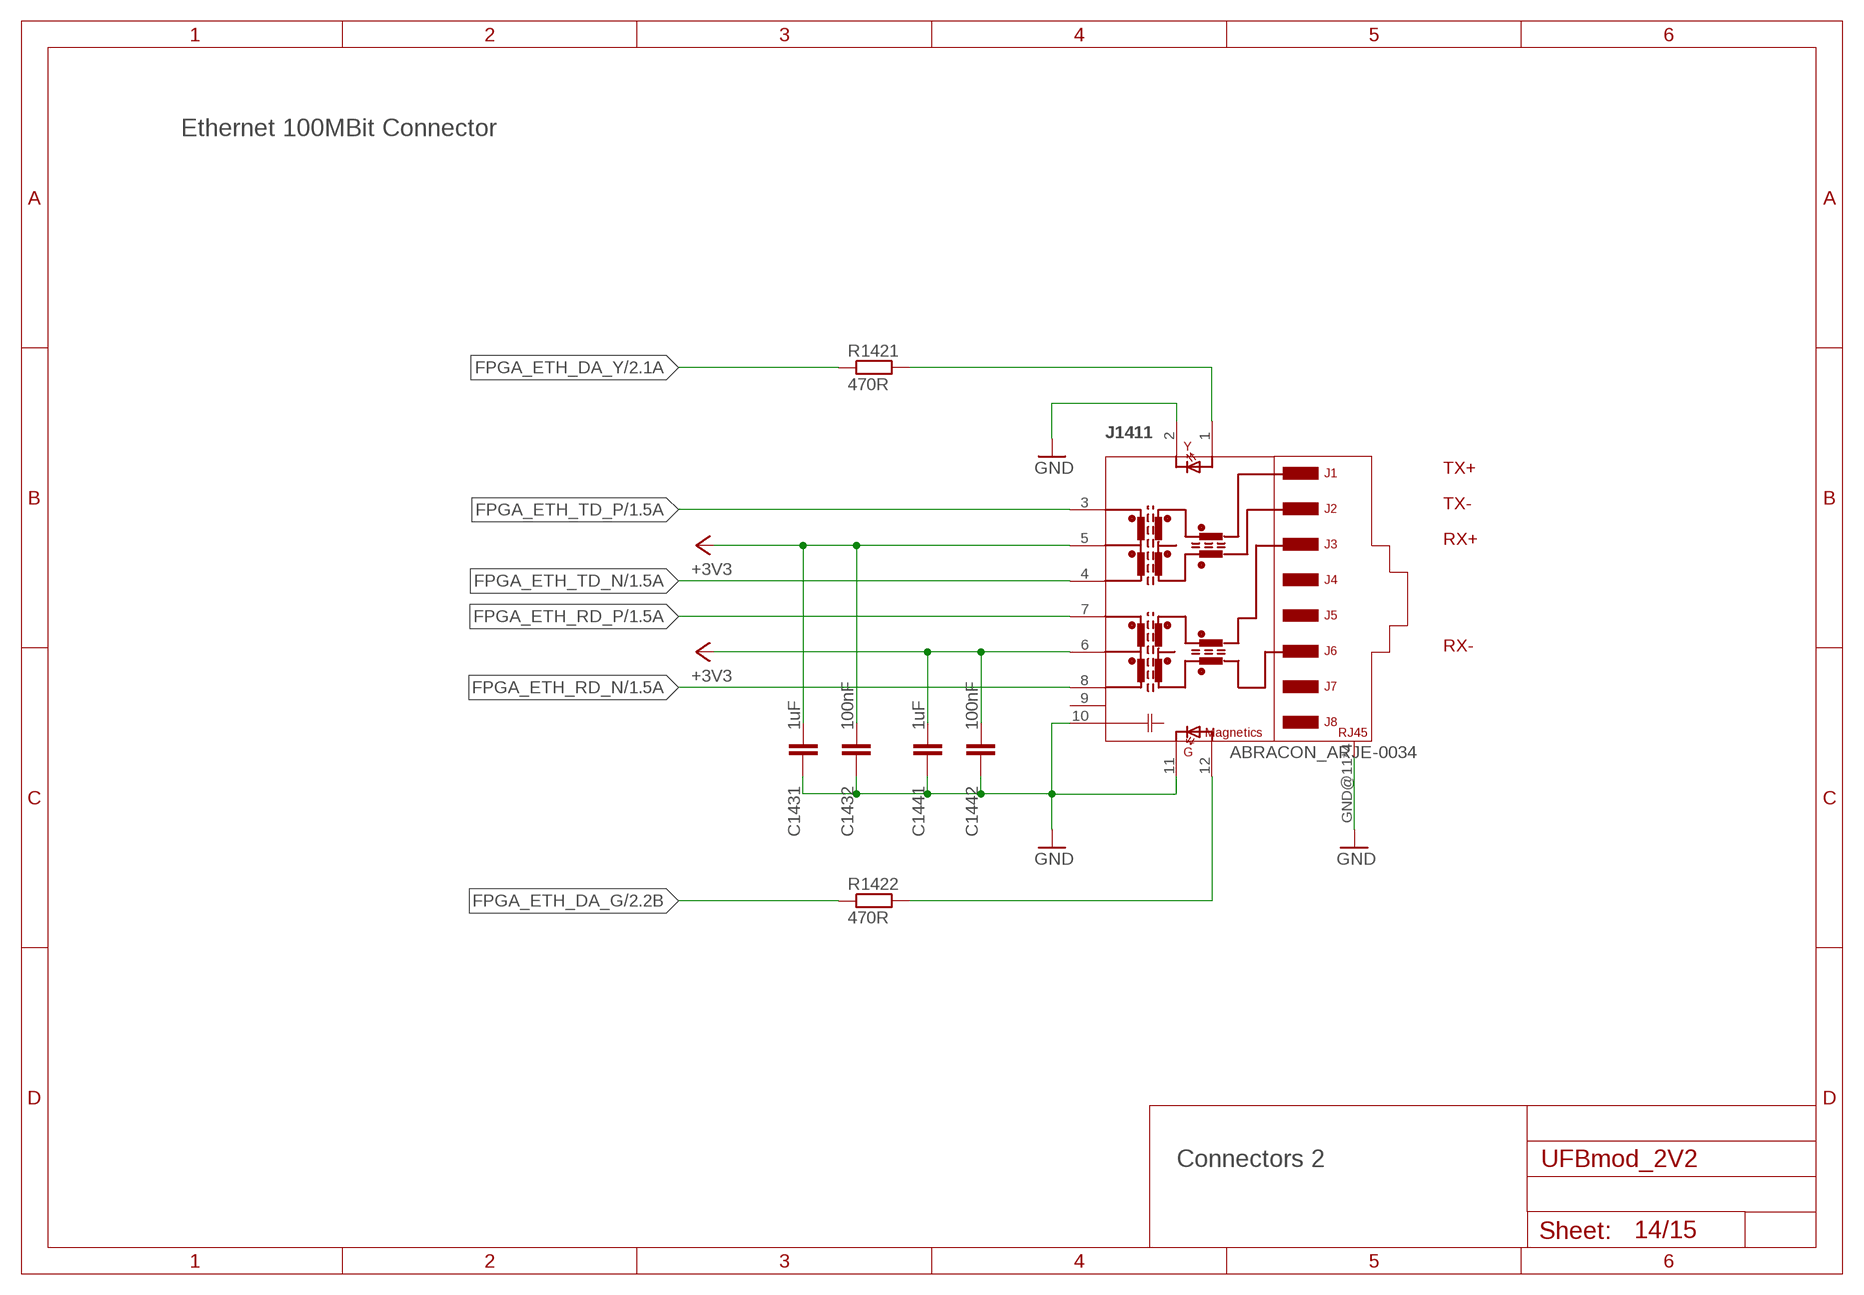
[diagram p13: schematic, sheet 14]
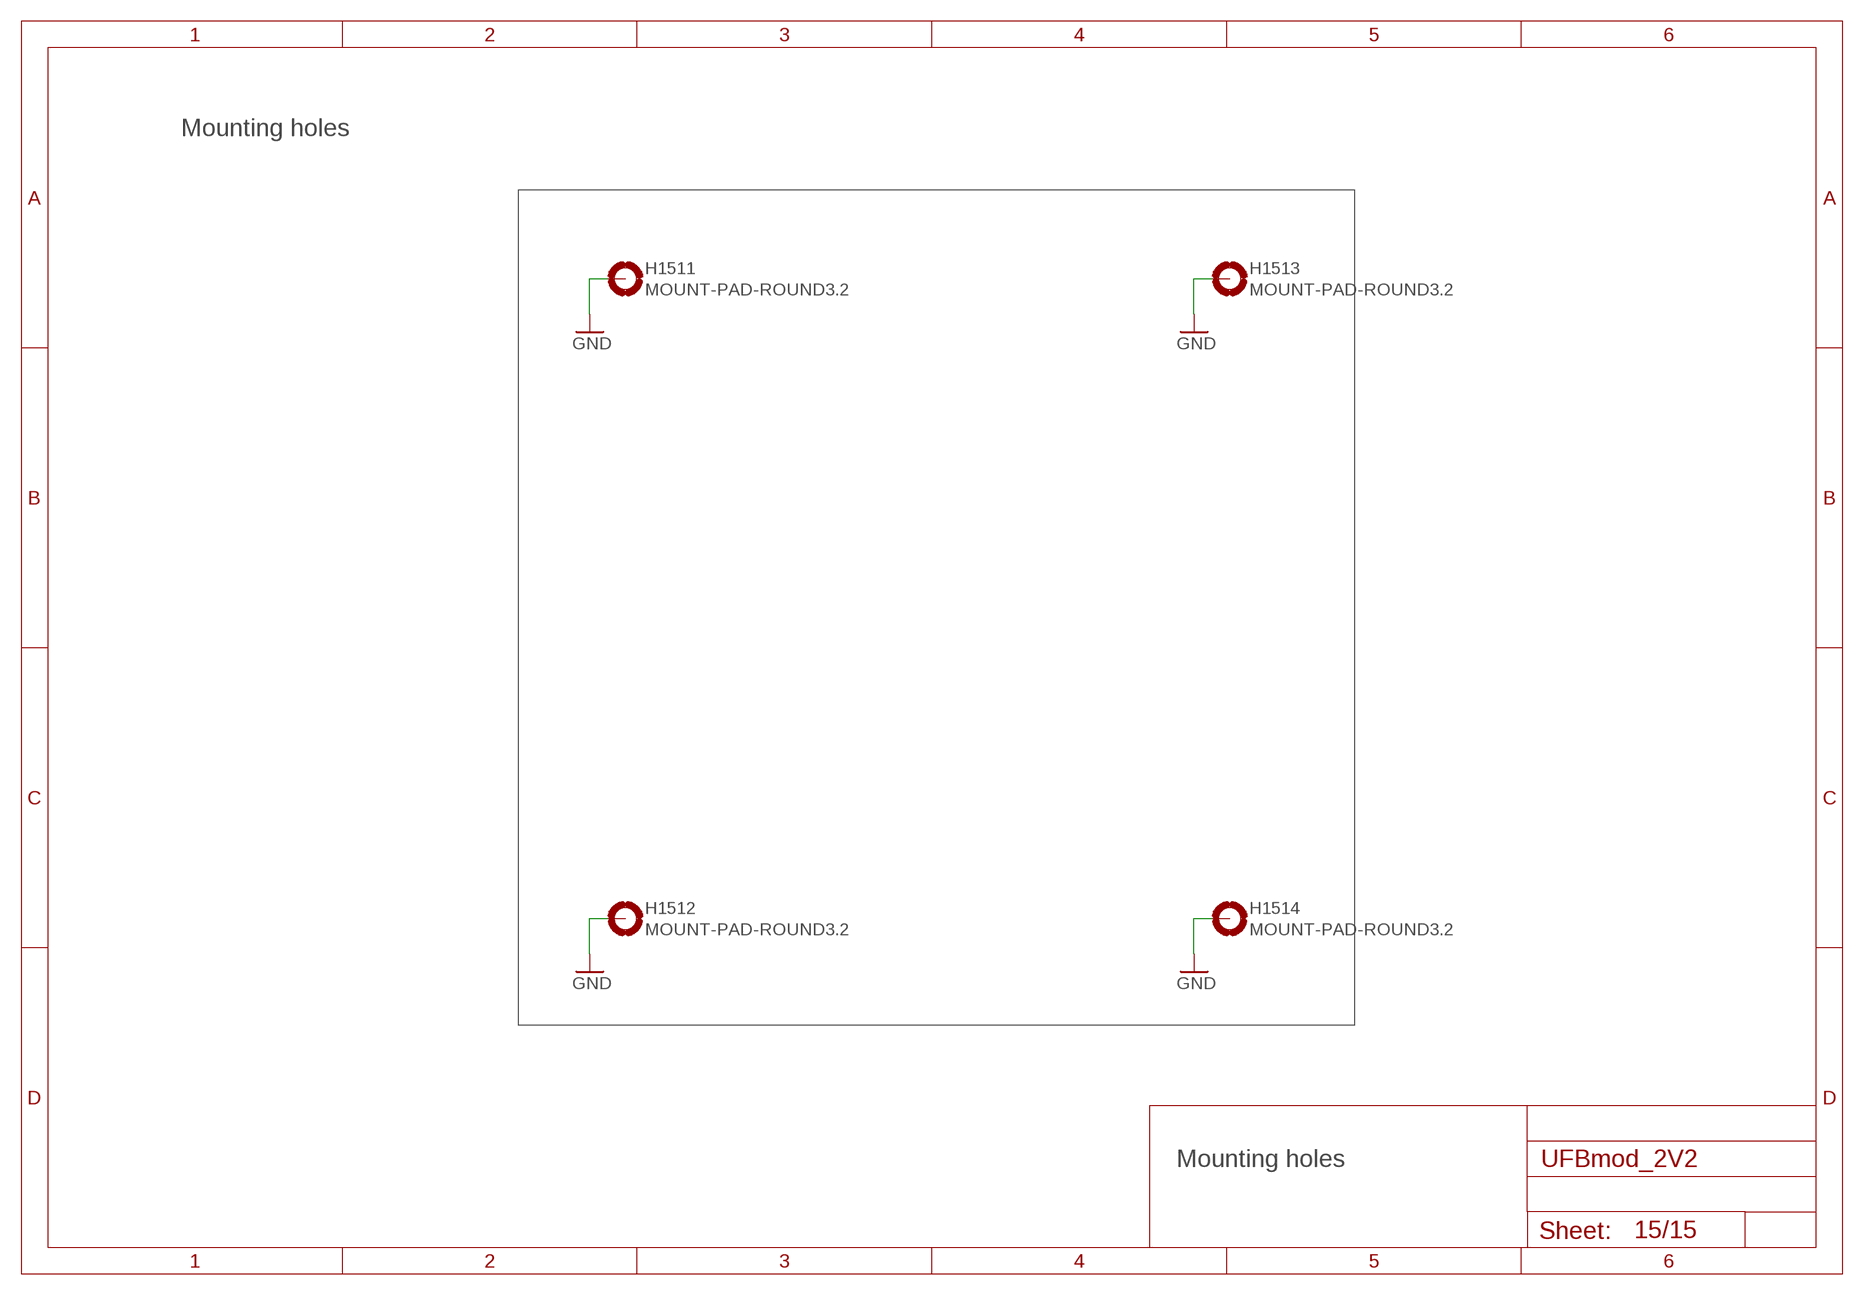
[diagram p14: schematic, sheet 15]

(export (version "E")
  (design (tool "Eeschema 10.0.6"))
  (components
    (comp (ref "JB2")
      (value "LSHM-150-04.0-L-DV-A-S-K-TR")
      (footprint "eagle-import:SAMTEC_LSHM-150-DV")
      (libsource (lib "eagle-import") (part "SAMTEC_LSHM-150-DV_JB2"))
    )
    (comp (ref "R0201")
      (value "0R")
      (footprint "eagle-import:R0402")
      (libsource (lib "eagle-import") (part "R-EU_R0402"))
    )
    (comp (ref "R0202")
      (value "N/A")
      (footprint "eagle-import:R0402")
      (libsource (lib "eagle-import") (part "R-EU_R0402"))
    )
    (comp (ref "R0203")
      (value "10kR")
      (footprint "eagle-import:R0402")
      (libsource (lib "eagle-import") (part "R-EU_R0402"))
    )
    (comp (ref "TP_RESIN")
      (value "TPB1,27")
      (footprint "eagle-import:B1,27")
      (libsource (lib "eagle-import") (part "TPB1,27"))
    )
    (comp (ref "C0911")
      (value "100nF")
      (footprint "eagle-import:C0402")
      (libsource (lib "eagle-import") (part "C-EUC0402"))
    )
    (comp (ref "C0912")
      (value "4.7uF")
      (footprint "eagle-import:C0603")
      (libsource (lib "eagle-import") (part "C-EUC0603"))
    )
    (comp (ref "C0913")
      (value "100nF")
      (footprint "eagle-import:C0402")
      (libsource (lib "eagle-import") (part "C-EUC0402"))
    )
    (comp (ref "C0914")
      (value "100nF")
      (footprint "eagle-import:C0402")
      (libsource (lib "eagle-import") (part "C-EUC0402"))
    )
    (comp (ref "C0916")
      (value "100nF")
      (footprint "eagle-import:C0402")
      (libsource (lib "eagle-import") (part "C-EUC0402"))
    )
    (comp (ref "C0917")
      (value "100nF")
      (footprint "eagle-import:C0402")
      (libsource (lib "eagle-import") (part "C-EUC0402"))
    )
    (comp (ref "C0918")
      (value "100nF")
      (footprint "eagle-import:C0402")
      (libsource (lib "eagle-import") (part "C-EUC0402"))
    )
    (comp (ref "C0921")
      (value "100nF")
      (footprint "eagle-import:C0402")
      (libsource (lib "eagle-import") (part "C-EUC0402"))
    )
    (comp (ref "C0922")
      (value "100nF")
      (footprint "eagle-import:C0402")
      (libsource (lib "eagle-import") (part "C-EUC0402"))
    )
    (comp (ref "C0923")
      (value "4.7uF")
      (footprint "eagle-import:C0603")
      (libsource (lib "eagle-import") (part "C-EUC0603"))
    )
    (comp (ref "C0924")
      (value "4.7uF")
      (footprint "eagle-import:C0603")
      (libsource (lib "eagle-import") (part "C-EUC0603"))
    )
    (comp (ref "D0971")
      (value "CMD17-21VGD/TR8 GREEN")
      (footprint "eagle-import:CHIP-LED0805")
      (libsource (lib "eagle-import") (part "LEDCHIP-LED0805"))
    )
    (comp (ref "D0972")
      (value "CMD17-21VRD/TR8 RED")
      (footprint "eagle-import:CHIP-LED0805")
      (libsource (lib "eagle-import") (part "LEDCHIP-LED0805"))
    )
    (comp (ref "L0911")
      (value "300R")
      (footprint "eagle-import:R1206")
      (libsource (lib "eagle-import") (part "R-EU_R1206"))
    )
    (comp (ref "L0921")
      (value "300R")
      (footprint "eagle-import:R1206")
      (libsource (lib "eagle-import") (part "R-EU_R1206"))
    )
    (comp (ref "L0922")
      (value "300R")
      (footprint "eagle-import:R1206")
      (libsource (lib "eagle-import") (part "R-EU_R1206"))
    )
    (comp (ref "R0911")
      (value "12kR 1%0")
      (footprint "eagle-import:R0402")
      (libsource (lib "eagle-import") (part "R-EU_R0402"))
    )
    (comp (ref "R0912")
      (value "100R")
      (footprint "eagle-import:R0402")
      (libsource (lib "eagle-import") (part "R-EU_R0402"))
    )
    (comp (ref "R0913")
      (value "100kR")
      (footprint "eagle-import:R0402")
      (libsource (lib "eagle-import") (part "R-EU_R0402"))
    )
    (comp (ref "R0931")
      (value "10kR")
      (footprint "eagle-import:R0402")
      (libsource (lib "eagle-import") (part "R-EU_R0402"))
    )
    (comp (ref "R0941")
      (value "100R")
      (footprint "eagle-import:R0402")
      (libsource (lib "eagle-import") (part "R-EU_R0402"))
    )
    (comp (ref "R0961")
      (value "100R")
      (footprint "eagle-import:R0402")
      (libsource (lib "eagle-import") (part "R-EU_R0402"))
    )
    (comp (ref "R0962")
      (value "100R")
      (footprint "eagle-import:R0402")
      (libsource (lib "eagle-import") (part "R-EU_R0402"))
    )
    (comp (ref "R0963")
      (value "100R")
      (footprint "eagle-import:R0402")
      (libsource (lib "eagle-import") (part "R-EU_R0402"))
    )
    (comp (ref "R0964")
      (value "100R")
      (footprint "eagle-import:R0402")
      (libsource (lib "eagle-import") (part "R-EU_R0402"))
    )
    (comp (ref "R0965")
      (value "100R")
      (footprint "eagle-import:R0402")
      (libsource (lib "eagle-import") (part "R-EU_R0402"))
    )
    (comp (ref "R0966")
      (value "100R")
      (footprint "eagle-import:R0402")
      (libsource (lib "eagle-import") (part "R-EU_R0402"))
    )
    (comp (ref "R0967")
      (value "100R")
      (footprint "eagle-import:R0402")
      (libsource (lib "eagle-import") (part "R-EU_R0402"))
    )
    (comp (ref "R0968")
      (value "100R")
      (footprint "eagle-import:R0402")
      (libsource (lib "eagle-import") (part "R-EU_R0402"))
    )
    (comp (ref "R0971")
      (value "560R")
      (footprint "eagle-import:R0402")
      (libsource (lib "eagle-import") (part "R-EU_R0402"))
    )
    (comp (ref "R0972")
      (value "560R")
      (footprint "eagle-import:R0402")
      (libsource (lib "eagle-import") (part "R-EU_R0402"))
    )
    (comp (ref "R0981")
      (value "10kR")
      (footprint "eagle-import:R0402")
      (libsource (lib "eagle-import") (part "R-EU_R0402"))
    )
    (comp (ref "R0991")
      (value "N/A")
      (footprint "eagle-import:R0402")
      (libsource (lib "eagle-import") (part "R-EU_R0402"))
    )
    (comp (ref "TP_TXDEN")
      (value "TPB1,27")
      (footprint "eagle-import:B1,27")
      (libsource (lib "eagle-import") (part "TPB1,27"))
    )
    (comp (ref "U0911")
      (value "FT232HL")
      (footprint "eagle-import:LQFP48")
      (libsource (lib "eagle-import") (part "FTDI232HL"))
    )
    (comp (ref "C1011")
      (value "100nF")
      (footprint "eagle-import:C0402")
      (libsource (lib "eagle-import") (part "C-EUC0402"))
    )
    (comp (ref "C1012")
      (value "100nF")
      (footprint "eagle-import:C0402")
      (libsource (lib "eagle-import") (part "C-EUC0402"))
    )
    (comp (ref "C1013")
      (value "100nF")
      (footprint "eagle-import:C0402")
      (libsource (lib "eagle-import") (part "C-EUC0402"))
    )
    (comp (ref "D1021")
      (value "ASMT-YTB7-0AA02_RGB")
      (footprint "eagle-import:ASMT-YTB7_0AA02_RGB")
      (libsource (lib "eagle-import") (part "ASMT-YTB7-0AA02_RGB"))
    )
    (comp (ref "R1011")
      (value "1kR")
      (footprint "eagle-import:R0402")
      (libsource (lib "eagle-import") (part "R-EU_R0402"))
    )
    (comp (ref "R1012")
      (value "1kR")
      (footprint "eagle-import:R0402")
      (libsource (lib "eagle-import") (part "R-EU_R0402"))
    )
    (comp (ref "R1013")
      (value "1kR")
      (footprint "eagle-import:R0402")
      (libsource (lib "eagle-import") (part "R-EU_R0402"))
    )
    (comp (ref "R1021")
      (value "820R")
      (footprint "eagle-import:R0402")
      (libsource (lib "eagle-import") (part "R-EU_R0402"))
    )
    (comp (ref "R1022")
      (value "1kR")
      (footprint "eagle-import:R0402")
      (libsource (lib "eagle-import") (part "R-EU_R0402"))
    )
    (comp (ref "R1023")
      (value "820R")
      (footprint "eagle-import:R0402")
      (libsource (lib "eagle-import") (part "R-EU_R0402"))
    )
    (comp (ref "X1011")
      (value "TTE_EN11-HSM")
      (footprint "eagle-import:TTE_EN11-HSM")
      (libsource (lib "eagle-import") (part "TTE_EN11-HSM"))
    )
    (comp (ref "C1101")
      (value "4.7uF")
      (footprint "eagle-import:C0805")
      (libsource (lib "eagle-import") (part "C-EUC0805"))
    )
    (comp (ref "C1102")
      (value "1uF")
      (footprint "eagle-import:C0402")
      (libsource (lib "eagle-import") (part "C-EUC0402"))
    )
    (comp (ref "C1108")
      (value "100nF")
      (footprint "eagle-import:C0805")
      (libsource (lib "eagle-import") (part "C-EUC0805"))
    )
    (comp (ref "C1111")
      (value "22uF")
      (footprint "eagle-import:C0805")
      (libsource (lib "eagle-import") (part "C-EUC0805"))
    )
    (comp (ref "C1112")
      (value "22uF")
      (footprint "eagle-import:C0805")
      (libsource (lib "eagle-import") (part "C-EUC0805"))
    )
    (comp (ref "C1113")
      (value "22uF")
      (footprint "eagle-import:C0805")
      (libsource (lib "eagle-import") (part "C-EUC0805"))
    )
    (comp (ref "C1114")
      (value "22uF")
      (footprint "eagle-import:C0805")
      (libsource (lib "eagle-import") (part "C-EUC0805"))
    )
    (comp (ref "C1122")
      (value "N/A")
      (footprint "eagle-import:C0805")
      (libsource (lib "eagle-import") (part "C-EUC0805"))
    )
    (comp (ref "C1131")
      (value "100nF")
      (footprint "eagle-import:C0402")
      (libsource (lib "eagle-import") (part "C-EUC0402"))
    )
    (comp (ref "C1132")
      (value "1nF")
      (footprint "eagle-import:C0402")
      (libsource (lib "eagle-import") (part "C-EUC0402"))
    )
    (comp (ref "C1151")
      (value "100uF")
      (footprint "eagle-import:C0805")
      (libsource (lib "eagle-import") (part "C-EUC0805"))
    )
    (comp (ref "C1152")
      (value "100uF")
      (footprint "eagle-import:C0805")
      (libsource (lib "eagle-import") (part "C-EUC0805"))
    )
    (comp (ref "C1153")
      (value "100uF")
      (footprint "eagle-import:C0805")
      (libsource (lib "eagle-import") (part "C-EUC0805"))
    )
    (comp (ref "D1111")
      (value "CRS08")
      (footprint "eagle-import:SOD80C")
      (libsource (lib "eagle-import") (part "CRS08"))
    )
    (comp (ref "D1112")
      (value "CRS08")
      (footprint "eagle-import:SOD80C")
      (libsource (lib "eagle-import") (part "CRS08"))
    )
    (comp (ref "D1161")
      (value "CRS08")
      (footprint "eagle-import:SOD80C")
      (libsource (lib "eagle-import") (part "CRS08"))
    )
    (comp (ref "L1101")
      (value "470nH")
      (footprint "eagle-import:L5650M")
      (libsource (lib "eagle-import") (part "L-EUL5650M"))
    )
    (comp (ref "R1101")
      (value "10kR 0%5")
      (footprint "eagle-import:R0402")
      (libsource (lib "eagle-import") (part "R-EU_R0402"))
    )
    (comp (ref "R1102")
      (value "45.3kR 0%5")
      (footprint "eagle-import:R0402")
      (libsource (lib "eagle-import") (part "R-EU_R0402"))
    )
    (comp (ref "R1103")
      (value "N/A")
      (footprint "eagle-import:R0402")
      (libsource (lib "eagle-import") (part "R-EU_R0402"))
    )
    (comp (ref "R1104")
      (value "N/A")
      (footprint "eagle-import:R0402")
      (libsource (lib "eagle-import") (part "R-EU_R0402"))
    )
    (comp (ref "R1105")
      (value "110kR")
      (footprint "eagle-import:R0402")
      (libsource (lib "eagle-import") (part "R-EU_R0402"))
    )
    (comp (ref "R1106")
      (value "200kR")
      (footprint "eagle-import:R0402")
      (libsource (lib "eagle-import") (part "R-EU_R0402"))
    )
    (comp (ref "R1107")
      (value "100kR")
      (footprint "eagle-import:R0402")
      (libsource (lib "eagle-import") (part "R-EU_R0402"))
    )
    (comp (ref "R1108")
      (value "2R")
      (footprint "eagle-import:R0805")
      (libsource (lib "eagle-import") (part "R-EU_R0805"))
    )
    (comp (ref "R1122")
      (value "N/A")
      (footprint "eagle-import:R0805")
      (libsource (lib "eagle-import") (part "R-EU_R0805"))
    )
    (comp (ref "R1131")
      (value "15kR")
      (footprint "eagle-import:R0402")
      (libsource (lib "eagle-import") (part "R-EU_R0402"))
    )
    (comp (ref "R1161")
      (value "220kR")
      (footprint "eagle-import:R0402")
      (libsource (lib "eagle-import") (part "R-EU_R0402"))
    )
    (comp (ref "U1101")
      (value "TPS53353")
      (footprint "eagle-import:DQP-22")
      (libsource (lib "eagle-import") (part "TPS53353"))
    )
    (comp (ref "FPGA_EN1")
      (value "TPB1,27")
      (footprint "eagle-import:B1,27")
      (libsource (lib "eagle-import") (part "TPB1,27"))
    )
    (comp (ref "FPGA_MODE")
      (value "TPB1,27")
      (footprint "eagle-import:B1,27")
      (libsource (lib "eagle-import") (part "TPB1,27"))
    )
    (comp (ref "JB1")
      (value "LSHM-150-04.0-L-DV-A-S-K-TR")
      (footprint "eagle-import:SAMTEC_LSHM-150-DV")
      (libsource (lib "eagle-import") (part "SAMTEC_LSHM-150-DV_JB1"))
    )
    (comp (ref "PGOOD")
      (value "TPB1,27")
      (footprint "eagle-import:B1,27")
      (libsource (lib "eagle-import") (part "TPB1,27"))
    )
    (comp (ref "R0411")
      (value "3.9kR")
      (footprint "eagle-import:R0402")
      (libsource (lib "eagle-import") (part "R-EU_R0402"))
    )
    (comp (ref "R0412")
      (value "3.9kR")
      (footprint "eagle-import:R0402")
      (libsource (lib "eagle-import") (part "R-EU_R0402"))
    )
    (comp (ref "H1511")
      (value "MOUNT-PAD-ROUND3.2")
      (footprint "eagle-import:3,2-PAD")
      (libsource (lib "eagle-import") (part "MOUNT-PAD-ROUND3.2"))
    )
    (comp (ref "H1512")
      (value "MOUNT-PAD-ROUND3.2")
      (footprint "eagle-import:3,2-PAD")
      (libsource (lib "eagle-import") (part "MOUNT-PAD-ROUND3.2"))
    )
    (comp (ref "H1513")
      (value "MOUNT-PAD-ROUND3.2")
      (footprint "eagle-import:3,2-PAD")
      (libsource (lib "eagle-import") (part "MOUNT-PAD-ROUND3.2"))
    )
    (comp (ref "H1514")
      (value "MOUNT-PAD-ROUND3.2")
      (footprint "eagle-import:3,2-PAD")
      (libsource (lib "eagle-import") (part "MOUNT-PAD-ROUND3.2"))
    )
    (comp (ref "C0701")
      (value "1uF")
      (footprint "eagle-import:C0402")
      (libsource (lib "eagle-import") (part "C-EUC0402"))
    )
    (comp (ref "C0703")
      (value "1uF")
      (footprint "eagle-import:C0402")
      (libsource (lib "eagle-import") (part "C-EUC0402"))
    )
    (comp (ref "C0704")
      (value "1uF")
      (footprint "eagle-import:C0402")
      (libsource (lib "eagle-import") (part "C-EUC0402"))
    )
    (comp (ref "C0706")
      (value "100nF")
      (footprint "eagle-import:C0402")
      (libsource (lib "eagle-import") (part "C-EUC0402"))
    )
    (comp (ref "C0707")
      (value "100nF")
      (footprint "eagle-import:C0402")
      (libsource (lib "eagle-import") (part "C-EUC0402"))
    )
    (comp (ref "C0708")
      (value "100nF")
      (footprint "eagle-import:C0402")
      (libsource (lib "eagle-import") (part "C-EUC0402"))
    )
    (comp (ref "C0711")
      (value "10nF")
      (footprint "eagle-import:C0402")
      (libsource (lib "eagle-import") (part "C-EUC0402"))
    )
    (comp (ref "C0712")
      (value "10nF")
      (footprint "eagle-import:C0402")
      (libsource (lib "eagle-import") (part "C-EUC0402"))
    )
    (comp (ref "C0713")
      (value "N/A")
      (footprint "eagle-import:C0402")
      (libsource (lib "eagle-import") (part "C-EUC0402"))
    )
    (comp (ref "L0703")
      (value "300R")
      (footprint "eagle-import:R1206")
      (libsource (lib "eagle-import") (part "R-EU_R1206"))
    )
    (comp (ref "L0704")
      (value "300R")
      (footprint "eagle-import:R1206")
      (libsource (lib "eagle-import") (part "R-EU_R1206"))
    )
    (comp (ref "L0721")
      (value "MURATA DXW21HN5011BL")
      (footprint "eagle-import:DXW21HN5011BL")
      (libsource (lib "eagle-import") (part "DXW21HN5011BL"))
    )
    (comp (ref "L0722")
      (value "Johanson 2450BL15B050E")
      (footprint "eagle-import:2450BL15B050")
      (libsource (lib "eagle-import") (part "2450BL15B050"))
    )
    (comp (ref "R0711")
      (value "130R")
      (footprint "eagle-import:R0402")
      (libsource (lib "eagle-import") (part "R-EU_R0402"))
    )
    (comp (ref "R0751")
      (value "100R")
      (footprint "eagle-import:R0402")
      (libsource (lib "eagle-import") (part "R-EU_R0402"))
    )
    (comp (ref "R0752")
      (value "100R")
      (footprint "eagle-import:R0402")
      (libsource (lib "eagle-import") (part "R-EU_R0402"))
    )
    (comp (ref "R0753")
      (value "100R")
      (footprint "eagle-import:R0402")
      (libsource (lib "eagle-import") (part "R-EU_R0402"))
    )
    (comp (ref "R0754")
      (value "100R")
      (footprint "eagle-import:R0402")
      (libsource (lib "eagle-import") (part "R-EU_R0402"))
    )
    (comp (ref "R0755")
      (value "100R")
      (footprint "eagle-import:R0402")
      (libsource (lib "eagle-import") (part "R-EU_R0402"))
    )
    (comp (ref "R0756")
      (value "100R")
      (footprint "eagle-import:R0402")
      (libsource (lib "eagle-import") (part "R-EU_R0402"))
    )
    (comp (ref "U0701")
      (value "AT86RF215-ZU")
      (footprint "eagle-import:QFN48_7X7-0P5-PAD")
      (libsource (lib "eagle-import") (part "AT86RF215"))
    )
    (comp (ref "U0711")
      (value "ASVTX-13-D-26.000MHZ-I05-T")
      (footprint "eagle-import:ASVTX-13")
      (libsource (lib "eagle-import") (part "ASVTX-13-D"))
    )
    (comp (ref "C1431")
      (value "1uF")
      (footprint "eagle-import:C0402")
      (libsource (lib "eagle-import") (part "C-EUC0402"))
    )
    (comp (ref "C1432")
      (value "100nF")
      (footprint "eagle-import:C0402")
      (libsource (lib "eagle-import") (part "C-EUC0402"))
    )
    (comp (ref "C1441")
      (value "1uF")
      (footprint "eagle-import:C0402")
      (libsource (lib "eagle-import") (part "C-EUC0402"))
    )
    (comp (ref "C1442")
      (value "100nF")
      (footprint "eagle-import:C0402")
      (libsource (lib "eagle-import") (part "C-EUC0402"))
    )
    (comp (ref "J1411")
      (value "ABRACON_ARJE-0034")
      (footprint "eagle-import:ARJE-0034_RJ45_WITH_MAGNETICS")
      (libsource (lib "eagle-import") (part "ARJE-0034_RJ45_WITH_MAGNETICS"))
    )
    (comp (ref "R1421")
      (value "470R")
      (footprint "eagle-import:R0402")
      (libsource (lib "eagle-import") (part "R-EU_R0402"))
    )
    (comp (ref "R1422")
      (value "470R")
      (footprint "eagle-import:R0402")
      (libsource (lib "eagle-import") (part "R-EU_R0402"))
    )
    (comp (ref "C1311")
      (value "1nF")
      (footprint "eagle-import:C0402")
      (libsource (lib "eagle-import") (part "C-EUC0402"))
    )
    (comp (ref "C1321")
      (value "100nF")
      (footprint "eagle-import:C0402")
      (libsource (lib "eagle-import") (part "C-EUC0402"))
    )
    (comp (ref "C1381")
      (value "100nF")
      (footprint "eagle-import:C0402")
      (libsource (lib "eagle-import") (part "C-EUC0402"))
    )
    (comp (ref "PF1311")
      (value "1.1A/2.2A")
      (footprint "eagle-import:M1206")
      (libsource (lib "eagle-import") (part "rcl_R-EU_M1206"))
    )
    (comp (ref "R1311")
      (value "330kR")
      (footprint "eagle-import:R0402")
      (libsource (lib "eagle-import") (part "R-EU_R0402"))
    )
    (comp (ref "R1321")
      (value "1kR")
      (footprint "eagle-import:R0402")
      (libsource (lib "eagle-import") (part "R-EU_R0402"))
    )
    (comp (ref "R1331")
      (value "1kR")
      (footprint "eagle-import:R0402")
      (libsource (lib "eagle-import") (part "R-EU_R0402"))
    )
    (comp (ref "R1332")
      (value "100R")
      (footprint "eagle-import:R0402")
      (libsource (lib "eagle-import") (part "R-EU_R0402"))
    )
    (comp (ref "R1333")
      (value "100R")
      (footprint "eagle-import:R0402")
      (libsource (lib "eagle-import") (part "R-EU_R0402"))
    )
    (comp (ref "R1334")
      (value "100R")
      (footprint "eagle-import:R0402")
      (libsource (lib "eagle-import") (part "R-EU_R0402"))
    )
    (comp (ref "R1335")
      (value "100R")
      (footprint "eagle-import:R0402")
      (libsource (lib "eagle-import") (part "R-EU_R0402"))
    )
    (comp (ref "R1337")
      (value "100R")
      (footprint "eagle-import:R0402")
      (libsource (lib "eagle-import") (part "R-EU_R0402"))
    )
    (comp (ref "R1338")
      (value "10kR")
      (footprint "eagle-import:R0402")
      (libsource (lib "eagle-import") (part "R-EU_R0402"))
    )
    (comp (ref "R1339")
      (value "100R")
      (footprint "eagle-import:R0402")
      (libsource (lib "eagle-import") (part "R-EU_R0402"))
    )
    (comp (ref "R1351")
      (value "100R")
      (footprint "eagle-import:R0402")
      (libsource (lib "eagle-import") (part "R-EU_R0402"))
    )
    (comp (ref "R1352")
      (value "100R")
      (footprint "eagle-import:R0402")
      (libsource (lib "eagle-import") (part "R-EU_R0402"))
    )
    (comp (ref "R1353")
      (value "100R")
      (footprint "eagle-import:R0402")
      (libsource (lib "eagle-import") (part "R-EU_R0402"))
    )
    (comp (ref "R1354")
      (value "100R")
      (footprint "eagle-import:R0402")
      (libsource (lib "eagle-import") (part "R-EU_R0402"))
    )
    (comp (ref "R1355")
      (value "100R")
      (footprint "eagle-import:R0402")
      (libsource (lib "eagle-import") (part "R-EU_R0402"))
    )
    (comp (ref "R1356")
      (value "100R")
      (footprint "eagle-import:R0402")
      (libsource (lib "eagle-import") (part "R-EU_R0402"))
    )
    (comp (ref "R1357")
      (value "100R")
      (footprint "eagle-import:R0402")
      (libsource (lib "eagle-import") (part "R-EU_R0402"))
    )
    (comp (ref "R1358")
      (value "100R")
      (footprint "eagle-import:R0402")
      (libsource (lib "eagle-import") (part "R-EU_R0402"))
    )
    (comp (ref "R1361")
      (value "100R")
      (footprint "eagle-import:R0402")
      (libsource (lib "eagle-import") (part "R-EU_R0402"))
    )
    (comp (ref "R1362")
      (value "100R")
      (footprint "eagle-import:R0402")
      (libsource (lib "eagle-import") (part "R-EU_R0402"))
    )
    (comp (ref "R1363")
      (value "100R")
      (footprint "eagle-import:R0402")
      (libsource (lib "eagle-import") (part "R-EU_R0402"))
    )
    (comp (ref "R1364")
      (value "100R")
      (footprint "eagle-import:R0402")
      (libsource (lib "eagle-import") (part "R-EU_R0402"))
    )
    (comp (ref "R1365")
      (value "100R")
      (footprint "eagle-import:R0402")
      (libsource (lib "eagle-import") (part "R-EU_R0402"))
    )
    (comp (ref "R1366")
      (value "100R")
      (footprint "eagle-import:R0402")
      (libsource (lib "eagle-import") (part "R-EU_R0402"))
    )
    (comp (ref "R1381")
      (value "0R")
      (footprint "eagle-import:R0402")
      (libsource (lib "eagle-import") (part "R-EU_R0402"))
    )
    (comp (ref "R1382")
      (value "NC")
      (footprint "eagle-import:R0402")
      (libsource (lib "eagle-import") (part "R-EU_R0402"))
    )
    (comp (ref "R1383")
      (value "NC")
      (footprint "eagle-import:R0402")
      (libsource (lib "eagle-import") (part "R-EU_R0402"))
    )
    (comp (ref "S1321")
      (value "KSR223G_SMD_1POL")
      (footprint "eagle-import:KSR223G_SMD_1POL")
      (libsource (lib "eagle-import") (part "KSR223G_SMD_1POL"))
    )
    (comp (ref "TP1371")
      (value "TPB1,27")
      (footprint "eagle-import:B1,27")
      (libsource (lib "eagle-import") (part "TPB1,27"))
    )
    (comp (ref "X1311")
      (value "MOLEX 105017-0001")
      (footprint "eagle-import:USB-B-MICRO-SMD_MOLEX-105017-0001")
      (libsource (lib "eagle-import") (part "USB_MICRO-B_MOLEX"))
    )
    (comp (ref "X1331")
      (value "XILINX-JTAG-14")
      (footprint "eagle-import:2X07_2MM00_SHROUDED_XILINX_JTAG")
      (libsource (lib "eagle-import") (part "XILINX-JTAG-14"))
    )
    (comp (ref "X1332")
      (value "HEADER-1X2")
      (footprint "eagle-import:1X02")
      (libsource (lib "eagle-import") (part "HEADER-1X2"))
    )
    (comp (ref "X1351")
      (value "PHOENIX_1990067_1X8X2MM50_PTSA-0-5")
      (footprint "eagle-import:PHOENIX_1990067_1X8X2MM50_PTSA-0-5")
      (libsource (lib "eagle-import") (part "PHOENIX_1990067_1X8X2MM50_PTSA-0-5"))
    )
    (comp (ref "X1361")
      (value "PHOENIX_1990067_1X8X2MM50_PTSA-0-5")
      (footprint "eagle-import:PHOENIX_1990067_1X8X2MM50_PTSA-0-5")
      (libsource (lib "eagle-import") (part "PHOENIX_1990067_1X8X2MM50_PTSA-0-5"))
    )
    (comp (ref "C0501")
      (value "100nF")
      (footprint "eagle-import:C0402")
      (libsource (lib "eagle-import") (part "C-EUC0402"))
    )
    (comp (ref "C0511")
      (value "1uF")
      (footprint "eagle-import:C0402")
      (libsource (lib "eagle-import") (part "C-EUC0402"))
    )
    (comp (ref "C0512")
      (value "1uF")
      (footprint "eagle-import:C0402")
      (libsource (lib "eagle-import") (part "C-EUC0402"))
    )
    (comp (ref "R0531")
      (value "220kR")
      (footprint "eagle-import:R0402")
      (libsource (lib "eagle-import") (part "R-EU_R0402"))
    )
    (comp (ref "R0532")
      (value "1kR")
      (footprint "eagle-import:R0402")
      (libsource (lib "eagle-import") (part "R-EU_R0402"))
    )
    (comp (ref "R0551")
      (value "1.5kR")
      (footprint "eagle-import:R0402")
      (libsource (lib "eagle-import") (part "R-EU_R0402"))
    )
    (comp (ref "R0552")
      (value "2.0kR")
      (footprint "eagle-import:R0402")
      (libsource (lib "eagle-import") (part "R-EU_R0402"))
    )
    (comp (ref "R0553")
      (value "27R")
      (footprint "eagle-import:R0603")
      (libsource (lib "eagle-import") (part "R-EU_R0603"))
    )
    (comp (ref "T0551")
      (value "MMBT2222")
      (footprint "eagle-import:SOT23")
      (libsource (lib "eagle-import") (part "BC846"))
    )
    (comp (ref "U0501")
      (value "MIDAS_MCCOG21605B6W-FPTLWI")
      (footprint "eagle-import:MIDAS_MCCOG21605B6W-FPTLWI")
      (libsource (lib "eagle-import") (part "MIDAS_MCCOG21605B6W-FPTLWI"))
    )
    (comp (ref "HB_351")
      (value "MOUNT-PAD-ROUND3.2")
      (footprint "eagle-import:3,2-PAD")
      (libsource (lib "eagle-import") (part "MOUNT-PAD-ROUND3.2"))
    )
    (comp (ref "HB_352")
      (value "MOUNT-PAD-ROUND3.2")
      (footprint "eagle-import:3,2-PAD")
      (libsource (lib "eagle-import") (part "MOUNT-PAD-ROUND3.2"))
    )
    (comp (ref "HB_353")
      (value "MOUNT-PAD-ROUND3.2")
      (footprint "eagle-import:3,2-PAD")
      (libsource (lib "eagle-import") (part "MOUNT-PAD-ROUND3.2"))
    )
    (comp (ref "HB_354")
      (value "MOUNT-PAD-ROUND3.2")
      (footprint "eagle-import:3,2-PAD")
      (libsource (lib "eagle-import") (part "MOUNT-PAD-ROUND3.2"))
    )
    (comp (ref "JB3")
      (value "LSHM-130-04.0-L-DV-A-S-K-TR")
      (footprint "eagle-import:SAMTEC_LSHM-130-DV")
      (libsource (lib "eagle-import") (part "SAMTEC_LSHM-130-DV_JB3"))
    )
    (comp (ref "C0811")
      (value "100nF")
      (footprint "eagle-import:C0402")
      (libsource (lib "eagle-import") (part "C-EUC0402"))
    )
    (comp (ref "C0821")
      (value "1nF")
      (footprint "eagle-import:C0402")
      (libsource (lib "eagle-import") (part "C-EUC0402"))
    )
    (comp (ref "C0831")
      (value "1nF")
      (footprint "eagle-import:C0402")
      (libsource (lib "eagle-import") (part "C-EUC0402"))
    )
    (comp (ref "C0832")
      (value "1nF")
      (footprint "eagle-import:C0402")
      (libsource (lib "eagle-import") (part "C-EUC0402"))
    )
    (comp (ref "C0851")
      (value "10nF")
      (footprint "eagle-import:C0402")
      (libsource (lib "eagle-import") (part "C-EUC0402"))
    )
    (comp (ref "C0852")
      (value "10nF")
      (footprint "eagle-import:C0402")
      (libsource (lib "eagle-import") (part "C-EUC0402"))
    )
    (comp (ref "C0853")
      (value "10nF")
      (footprint "eagle-import:C0402")
      (libsource (lib "eagle-import") (part "C-EUC0402"))
    )
    (comp (ref "C0891")
      (value "0pF")
      (footprint "eagle-import:C0402")
      (libsource (lib "eagle-import") (part "C-EUC0402"))
    )
    (comp (ref "C0893")
      (value "0pF")
      (footprint "eagle-import:C0402")
      (libsource (lib "eagle-import") (part "C-EUC0402"))
    )
    (comp (ref "C0895")
      (value "0pF")
      (footprint "eagle-import:C0402")
      (libsource (lib "eagle-import") (part "C-EUC0402"))
    )
    (comp (ref "C0897")
      (value "0pF")
      (footprint "eagle-import:C0402")
      (libsource (lib "eagle-import") (part "C-EUC0402"))
    )
    (comp (ref "L0821")
      (value "2.7nH")
      (footprint "eagle-import:L0603")
      (libsource (lib "eagle-import") (part "L-EUL0603"))
    )
    (comp (ref "L0853")
      (value "6.8nH")
      (footprint "eagle-import:L0603")
      (libsource (lib "eagle-import") (part "L-EUL0603"))
    )
    (comp (ref "L0892")
      (value "0nH")
      (footprint "eagle-import:L0603")
      (libsource (lib "eagle-import") (part "L-EUL0603"))
    )
    (comp (ref "L0896")
      (value "0nH")
      (footprint "eagle-import:L0603")
      (libsource (lib "eagle-import") (part "L-EUL0603"))
    )
    (comp (ref "R0821")
      (value "100R")
      (footprint "eagle-import:R0402")
      (libsource (lib "eagle-import") (part "R-EU_R0402"))
    )
    (comp (ref "R0822")
      (value "10kR")
      (footprint "eagle-import:R0402")
      (libsource (lib "eagle-import") (part "R-EU_R0402"))
    )
    (comp (ref "R0861")
      (value "10kR")
      (footprint "eagle-import:R0402")
      (libsource (lib "eagle-import") (part "R-EU_R0402"))
    )
    (comp (ref "R0862")
      (value "10kR")
      (footprint "eagle-import:R0402")
      (libsource (lib "eagle-import") (part "R-EU_R0402"))
    )
    (comp (ref "R0863")
      (value "10kR")
      (footprint "eagle-import:R0402")
      (libsource (lib "eagle-import") (part "R-EU_R0402"))
    )
    (comp (ref "TP_RFX_DET")
      (value "TPB1,27")
      (footprint "eagle-import:B1,27")
      (libsource (lib "eagle-import") (part "TPB1,27"))
    )
    (comp (ref "U0811")
      (value "PE4259")
      (footprint "eagle-import:SC-70_6-LEAD_2X1MM25_0P65")
      (libsource (lib "eagle-import") (part "PE4259"))
    )
    (comp (ref "U0821")
      (value "RFX1010")
      (footprint "eagle-import:QFN16-3X3-0P5-PAD")
      (libsource (lib "eagle-import") (part "RFX1010"))
    )
    (comp (ref "U0881")
      (value "B39871B3440U410")
      (footprint "eagle-import:B3440_3MM-X-3MM")
      (libsource (lib "eagle-import") (part "B3440"))
    )
    (comp (ref "X0891")
      (value "ANTENNATINY")
      (footprint "eagle-import:SMA_UFL_PAD_TINY")
      (libsource (lib "eagle-import") (part "ANTENNATINY"))
    )
    (comp (ref "X0895")
      (value "ANTENNATINY")
      (footprint "eagle-import:SMA_UFL_PAD_TINY")
      (libsource (lib "eagle-import") (part "ANTENNATINY"))
    )
    (comp (ref "C0611")
      (value "100nF")
      (footprint "eagle-import:C0402")
      (libsource (lib "eagle-import") (part "C-EUC0402"))
    )
    (comp (ref "C0612")
      (value "100nF")
      (footprint "eagle-import:C0402")
      (libsource (lib "eagle-import") (part "C-EUC0402"))
    )
    (comp (ref "C0621")
      (value "1uF")
      (footprint "eagle-import:C0402")
      (libsource (lib "eagle-import") (part "C-EUC0402"))
    )
    (comp (ref "C0651")
      (value "100nF")
      (footprint "eagle-import:C0402")
      (libsource (lib "eagle-import") (part "C-EUC0402"))
    )
    (comp (ref "R0621")
      (value "100kR")
      (footprint "eagle-import:R0402")
      (libsource (lib "eagle-import") (part "R-EU_R0402"))
    )
    (comp (ref "U0601")
      (value "MAX5217")
      (footprint "eagle-import:µMAX8")
      (libsource (lib "eagle-import") (part "MAX5217"))
    )
    (comp (ref "U0651")
      (value "LM4120IM5-3.0")
      (footprint "eagle-import:SOT95P285X120-5N")
      (libsource (lib "eagle-import") (part "LM4120IM5-3.0"))
    )
    (comp (ref "C1201")
      (value "10uF")
      (footprint "eagle-import:C0603")
      (libsource (lib "eagle-import") (part "C-EUC0603"))
    )
    (comp (ref "C1221")
      (value "10uF")
      (footprint "eagle-import:C0603")
      (libsource (lib "eagle-import") (part "C-EUC0603"))
    )
    (comp (ref "L1211")
      (value "4.7uH")
      (footprint "eagle-import:L2520")
      (libsource (lib "eagle-import") (part "L-EUL2520"))
    )
    (comp (ref "R1211")
      (value "10kR")
      (footprint "eagle-import:R0402")
      (libsource (lib "eagle-import") (part "R-EU_R0402"))
    )
    (comp (ref "U1211")
      (value "TPS62745DSSR")
      (footprint "eagle-import:WSON-12")
      (libsource (lib "eagle-import") (part "TPS62745"))
    )
  )
  (nets
    (net (code "1") (name "+2V5") (class "Default")
      (node (ref "C1221") (pin "1") (pinfunction "1_1") (pintype "passive"))
      (node (ref "L1211") (pin "1") (pinfunction "1_1") (pintype "passive"))
      (node (ref "R0201") (pin "1") (pinfunction "1_1") (pintype "passive"))
      (node (ref "R1382") (pin "2") (pinfunction "2_2") (pintype "passive"))
      (node (ref "U1211") (pin "5") (pinfunction "VOUT_5") (pintype "passive"))
    )
    (net (code "2") (name "+3V3") (class "Default")
      (node (ref "C0501") (pin "1") (pinfunction "1_1") (pintype "passive"))
      (node (ref "C0612") (pin "1") (pinfunction "1_1") (pintype "passive"))
      (node (ref "C0651") (pin "1") (pinfunction "1_1") (pintype "passive"))
      (node (ref "C0701") (pin "1") (pinfunction "1_1") (pintype "passive"))
      (node (ref "C0711") (pin "1") (pinfunction "1_1") (pintype "passive"))
      (node (ref "C0811") (pin "1") (pinfunction "1_1") (pintype "passive"))
      (node (ref "C0851") (pin "1") (pinfunction "1_1") (pintype "passive"))
      (node (ref "C0852") (pin "1") (pinfunction "1_1") (pintype "passive"))
      (node (ref "C0853") (pin "1") (pinfunction "1_1") (pintype "passive"))
      (node (ref "C0911") (pin "1") (pinfunction "1_1") (pintype "passive"))
      (node (ref "C0912") (pin "1") (pinfunction "1_1") (pintype "passive"))
      (node (ref "C0916") (pin "1") (pinfunction "1_1") (pintype "passive"))
      (node (ref "C0917") (pin "1") (pinfunction "1_1") (pintype "passive"))
      (node (ref "C0918") (pin "1") (pinfunction "1_1") (pintype "passive"))
      (node (ref "C1131") (pin "1") (pinfunction "1_1") (pintype "passive"))
      (node (ref "C1151") (pin "1") (pinfunction "1_1") (pintype "passive"))
      (node (ref "C1152") (pin "1") (pinfunction "1_1") (pintype "passive"))
      (node (ref "C1153") (pin "1") (pinfunction "1_1") (pintype "passive"))
      (node (ref "C1201") (pin "1") (pinfunction "1_1") (pintype "passive"))
      (node (ref "C1431") (pin "1") (pinfunction "1_1") (pintype "passive"))
      (node (ref "C1432") (pin "1") (pinfunction "1_1") (pintype "passive"))
      (node (ref "C1441") (pin "1") (pinfunction "1_1") (pintype "passive"))
      (node (ref "C1442") (pin "1") (pinfunction "1_1") (pintype "passive"))
      (node (ref "D0971") (pin "A") (pinfunction "A_A") (pintype "passive"))
      (node (ref "D0972") (pin "A") (pinfunction "A_A") (pintype "passive"))
      (node (ref "J1411") (pin "5") (pinfunction "5_5") (pintype "passive"))
      (node (ref "J1411") (pin "6") (pinfunction "6_6") (pintype "passive"))
      (node (ref "JB1") (pin "14") (pinfunction "U3V3IN_14") (pintype "power_in"))
      (node (ref "JB1") (pin "16") (pinfunction "U3V3IN_16") (pintype "power_in"))
      (node (ref "JB1") (pin "2") (pinfunction "VIN_2") (pintype "power_in"))
      (node (ref "JB1") (pin "4") (pinfunction "VIN_4") (pintype "power_in"))
      (node (ref "JB1") (pin "6") (pinfunction "VIN_6") (pintype "power_in"))
      (node (ref "JB2") (pin "1") (pinfunction "VIN_1") (pintype "power_in"))
      (node (ref "JB2") (pin "3") (pinfunction "VIN_3") (pintype "power_in"))
      (node (ref "JB2") (pin "5") (pinfunction "VIN_5") (pintype "power_in"))
      (node (ref "JB2") (pin "7") (pinfunction "VIN_7") (pintype "power_in"))
      (node (ref "L0703") (pin "1") (pinfunction "1_1") (pintype "passive"))
      (node (ref "L0704") (pin "1") (pinfunction "1_1") (pintype "passive"))
      (node (ref "L0853") (pin "1") (pinfunction "1_1") (pintype "passive"))
      (node (ref "L0921") (pin "2") (pinfunction "2_2") (pintype "passive"))
      (node (ref "L0922") (pin "2") (pinfunction "2_2") (pintype "passive"))
      (node (ref "L1101") (pin "1") (pinfunction "1_1") (pintype "passive"))
      (node (ref "R0203") (pin "2") (pinfunction "2_2") (pintype "passive"))
      (node (ref "R0411") (pin "2") (pinfunction "2_2") (pintype "passive"))
      (node (ref "R0412") (pin "2") (pinfunction "2_2") (pintype "passive"))
      (node (ref "R0931") (pin "2") (pinfunction "2_2") (pintype "passive"))
      (node (ref "R0981") (pin "2") (pinfunction "2_2") (pintype "passive"))
      (node (ref "R1102") (pin "2") (pinfunction "2_2") (pintype "passive"))
      (node (ref "R1104") (pin "1") (pinfunction "1_1") (pintype "passive"))
      (node (ref "U0501") (pin "12") (pinfunction "A_BL_12") (pintype "passive"))
      (node (ref "U0501") (pin "4") (pinfunction "VDD_4") (pintype "power_in"))
      (node (ref "U0601") (pin "5") (pinfunction "~{AUX}_5") (pintype "input"))
      (node (ref "U0601") (pin "7") (pinfunction "VDD_7") (pintype "power_in"))
      (node (ref "U0651") (pin "3") (pinfunction "EN_3") (pintype "input"))
      (node (ref "U0651") (pin "4") (pinfunction "VIN_4") (pintype "power_in"))
      (node (ref "U0711") (pin "4") (pinfunction "VCC_3V3_4") (pintype "power_in"))
      (node (ref "U0811") (pin "6") (pinfunction "VDD_~{CTRL}_6") (pintype "passive"))
      (node (ref "U0821") (pin "13") (pinfunction "VDD2_13") (pintype "power_in"))
      (node (ref "U0821") (pin "15") (pinfunction "VDD1_15") (pintype "power_in"))
      (node (ref "U0911") (pin "12") (pinfunction "VCCIO_12") (pintype "power_in"))
      (node (ref "U0911") (pin "24") (pinfunction "VCCIO_24") (pintype "power_in"))
      (node (ref "U0911") (pin "39") (pinfunction "VCCD_39") (pintype "power_in"))
      (node (ref "U0911") (pin "40") (pinfunction "VREGIN_40") (pintype "power_in"))
      (node (ref "U0911") (pin "46") (pinfunction "VCCIO_46") (pintype "power_in"))
      (node (ref "U1211") (pin "1") (pinfunction "VIN_1") (pintype "power_in"))
      (node (ref "U1211") (pin "10") (pinfunction "VSEL2_10") (pintype "input"))
      (node (ref "U1211") (pin "11") (pinfunction "VSEL1_11") (pintype "input"))
      (node (ref "U1211") (pin "9") (pinfunction "VSEL3_9") (pintype "input"))
      (node (ref "X1332") (pin "1") (pinfunction "1_1") (pintype "passive"))
    )
    (net (code "3") (name "+5V_USB") (class "Default")
      (node (ref "D1112") (pin "A") (pinfunction "A_A") (pintype "passive"))
      (node (ref "PF1311") (pin "1") (pinfunction "1_1") (pintype "passive"))
      (node (ref "R0991") (pin "1") (pinfunction "1_1") (pintype "passive"))
    )
    (net (code "4") (name "26MHZ_DAC_OUT") (class "Default")
      (node (ref "R0621") (pin "1") (pinfunction "1_1") (pintype "passive"))
      (node (ref "U0601") (pin "6") (pinfunction "OUT_6") (pintype "passive"))
    )
    (net (code "5") (name "BOARD_LCD_RESETN") (class "Default")
      (node (ref "JB1") (pin "98") (pinfunction "B14_L4_MIO_N_98") (pintype "passive"))
      (node (ref "R0532") (pin "1") (pinfunction "1_1") (pintype "passive"))
    )
    (net (code "6") (name "BOARD_ROTENC_I") (class "Default")
      (node (ref "JB2") (pin "22") (pinfunction "B14_L14_CLK_P_22") (pintype "passive"))
      (node (ref "R1011") (pin "2") (pinfunction "2_2") (pintype "passive"))
    )
    (net (code "7") (name "BOARD_ROTENC_PUSH") (class "Default")
      (node (ref "JB2") (pin "26") (pinfunction "B14_L13_CLK_P_26") (pintype "passive"))
      (node (ref "R1013") (pin "2") (pinfunction "2_2") (pintype "passive"))
    )
    (net (code "8") (name "BOARD_ROTENC_Q") (class "Default")
      (node (ref "JB2") (pin "24") (pinfunction "B14_L14_CLK_N_24") (pintype "passive"))
      (node (ref "R1012") (pin "2") (pinfunction "2_2") (pintype "passive"))
    )
    (net (code "9") (name "BOARD_SCL") (class "Default")
      (node (ref "JB1") (pin "82") (pinfunction "B16_L8_N_82") (pintype "passive"))
      (node (ref "R0412") (pin "1") (pinfunction "1_1") (pintype "passive"))
      (node (ref "U0501") (pin "7") (pinfunction "SCL_7") (pintype "input"))
      (node (ref "U0601") (pin "3") (pinfunction "SCL_3") (pintype "input"))
    )
    (net (code "10") (name "BOARD_SDA") (class "Default")
      (node (ref "JB1") (pin "84") (pinfunction "B16_L8_P_84") (pintype "passive"))
      (node (ref "R0411") (pin "1") (pinfunction "1_1") (pintype "passive"))
      (node (ref "U0501") (pin "6") (pinfunction "SDA_6") (pintype "bidirectional"))
      (node (ref "U0601") (pin "4") (pinfunction "SDA_4") (pintype "tri_state"))
    )
    (net (code "11") (name "CLKIN2_N") (class "Default")
      (node (ref "JB3") (pin "31") (pinfunction "CLKIN2_CLK_N_31") (pintype "passive"))
      (node (ref "JB3") (pin "39") (pinfunction "B13_L16_N_39") (pintype "passive"))
    )
    (net (code "12") (name "CLKIN2_P") (class "Default")
      (node (ref "JB3") (pin "33") (pinfunction "CLKIN2_CLK_P_33") (pintype "passive"))
      (node (ref "JB3") (pin "37") (pinfunction "B13_L16_P_37") (pintype "passive"))
    )
    (net (code "13") (name "DDR3_INIT_CALIB_COMPLETE") (class "Default")
      (node (ref "JB2") (pin "14") (pinfunction "B14_L8_P_14") (pintype "passive"))
      (node (ref "TP1371") (pin "TP") (pinfunction "TP_TP") (pintype "input"))
    )
    (net (code "14") (name "FE09_ANT") (class "Default")
      (node (ref "U0821") (pin "9") (pinfunction "ANT_9") (pintype "bidirectional"))
      (node (ref "U0881") (pin "2") (pinfunction "IN_2") (pintype "passive"))
    )
    (net (code "15") (name "FE09_RX") (class "Default")
      (node (ref "C0832") (pin "1") (pinfunction "1_1") (pintype "passive"))
      (node (ref "U0821") (pin "14") (pinfunction "RX_14") (pintype "output"))
    )
    (net (code "16") (name "FE09_TX") (class "Default")
      (node (ref "C0831") (pin "1") (pinfunction "1_1") (pintype "passive"))
      (node (ref "U0821") (pin "3") (pinfunction "TX_3") (pintype "input"))
    )
    (net (code "17") (name "FPGA_B16_L2_N") (class "Default")
      (node (ref "JB1") (pin "79") (pinfunction "B16_L2_N_79") (pintype "passive"))
    )
    (net (code "18") (name "FPGA_B16_L2_P") (class "Default")
      (node (ref "JB1") (pin "81") (pinfunction "B16_L2_P_81") (pintype "passive"))
    )
    (net (code "19") (name "FPGA_B16_L5_N") (class "Default")
      (node (ref "JB1") (pin "75") (pinfunction "B16_L5_N_75") (pintype "passive"))
    )
    (net (code "20") (name "FPGA_B16_L5_P") (class "Default")
      (node (ref "JB1") (pin "77") (pinfunction "B16_L5_P_77") (pintype "passive"))
    )
    (net (code "21") (name "FPGA_B16_L6_N") (class "Default")
      (node (ref "JB1") (pin "85") (pinfunction "B16_L6_N_85") (pintype "passive"))
    )
    (net (code "22") (name "FPGA_B16_L6_P") (class "Default")
      (node (ref "JB1") (pin "87") (pinfunction "B16_L6_P_87") (pintype "passive"))
    )
    (net (code "23") (name "FPGA_B16_L7_N") (class "Default")
      (node (ref "JB1") (pin "59") (pinfunction "B16_L7_N_59") (pintype "passive"))
      (node (ref "R1364") (pin "1") (pinfunction "1_1") (pintype "passive"))
    )
    (net (code "24") (name "FPGA_B16_L7_P") (class "Default")
      (node (ref "JB1") (pin "61") (pinfunction "B16_L7_P_61") (pintype "passive"))
      (node (ref "R1363") (pin "1") (pinfunction "1_1") (pintype "passive"))
    )
    (net (code "25") (name "FPGA_B16_L9_N") (class "Default")
      (node (ref "JB1") (pin "55") (pinfunction "B16_L9_N_55") (pintype "passive"))
      (node (ref "R1362") (pin "1") (pinfunction "1_1") (pintype "passive"))
    )
    (net (code "26") (name "FPGA_B16_L9_P") (class "Default")
      (node (ref "JB1") (pin "57") (pinfunction "B16_L9_P_57") (pintype "passive"))
      (node (ref "R1361") (pin "1") (pinfunction "1_1") (pintype "passive"))
    )
    (net (code "27") (name "FPGA_B16_L10_N") (class "Default")
      (node (ref "JB1") (pin "69") (pinfunction "B16_L10_N_69") (pintype "passive"))
    )
    (net (code "28") (name "FPGA_B16_L10_P") (class "Default")
      (node (ref "JB1") (pin "71") (pinfunction "B16_L10_P_71") (pintype "passive"))
    )
    (net (code "29") (name "FPGA_B16_L11_N") (class "Default")
      (node (ref "JB1") (pin "67") (pinfunction "B16_L11_N_67") (pintype "passive"))
      (node (ref "R1366") (pin "1") (pinfunction "1_1") (pintype "passive"))
    )
    (net (code "30") (name "FPGA_B16_L11_P") (class "Default")
      (node (ref "JB1") (pin "65") (pinfunction "B16_L11_P_65") (pintype "passive"))
      (node (ref "R1365") (pin "1") (pinfunction "1_1") (pintype "passive"))
    )
    (net (code "31") (name "FPGA_B16_L16_N") (class "Default")
      (node (ref "JB1") (pin "37") (pinfunction "B16_L16_N_37") (pintype "passive"))
      (node (ref "R1352") (pin "1") (pinfunction "1_1") (pintype "passive"))
    )
    (net (code "32") (name "FPGA_B16_L16_P") (class "Default")
      (node (ref "JB1") (pin "35") (pinfunction "B16_L16_P_35") (pintype "passive"))
      (node (ref "R1351") (pin "1") (pinfunction "1_1") (pintype "passive"))
    )
    (net (code "33") (name "FPGA_B16_L17_N") (class "Default")
      (node (ref "JB1") (pin "45") (pinfunction "B16_L17_N_45") (pintype "passive"))
      (node (ref "R1356") (pin "1") (pinfunction "1_1") (pintype "passive"))
    )
    (net (code "34") (name "FPGA_B16_L17_P") (class "Default")
      (node (ref "JB1") (pin "47") (pinfunction "B16_L17_P_47") (pintype "passive"))
      (node (ref "R1355") (pin "1") (pinfunction "1_1") (pintype "passive"))
    )
    (net (code "35") (name "FPGA_B16_L18_N") (class "Default")
      (node (ref "JB1") (pin "49") (pinfunction "B16_L18_N_49") (pintype "passive"))
      (node (ref "R1358") (pin "1") (pinfunction "1_1") (pintype "passive"))
    )
    (net (code "36") (name "FPGA_B16_L18_P") (class "Default")
      (node (ref "JB1") (pin "51") (pinfunction "B16_L18_P_51") (pintype "passive"))
      (node (ref "R1357") (pin "1") (pinfunction "1_1") (pintype "passive"))
    )
    (net (code "37") (name "FPGA_B16_L19_N") (class "Default")
      (node (ref "JB1") (pin "39") (pinfunction "B16_L19_N_39") (pintype "passive"))
      (node (ref "R1354") (pin "1") (pinfunction "1_1") (pintype "passive"))
    )
    (net (code "38") (name "FPGA_B16_L19_P") (class "Default")
      (node (ref "JB1") (pin "41") (pinfunction "B16_L19_P_41") (pintype "passive"))
      (node (ref "R1353") (pin "1") (pinfunction "1_1") (pintype "passive"))
    )
    (net (code "39") (name "FPGA_ETH_DA_G") (class "Default")
      (node (ref "JB2") (pin "18") (pinfunction "B14_L17_P_18") (pintype "passive"))
      (node (ref "R1422") (pin "1") (pinfunction "1_1") (pintype "passive"))
    )
    (net (code "40") (name "FPGA_ETH_DA_Y") (class "Default")
      (node (ref "JB2") (pin "16") (pinfunction "B14_L17_N_16") (pintype "passive"))
      (node (ref "R1421") (pin "1") (pinfunction "1_1") (pintype "passive"))
    )
    (net (code "41") (name "FPGA_ETH_RD_N") (class "Default")
      (node (ref "J1411") (pin "8") (pinfunction "8_8") (pintype "passive"))
      (node (ref "JB1") (pin "11") (pinfunction "ETH_RD_N_11") (pintype "input"))
    )
    (net (code "42") (name "FPGA_ETH_RD_P") (class "Default")
      (node (ref "J1411") (pin "7") (pinfunction "7_7") (pintype "passive"))
      (node (ref "JB1") (pin "9") (pinfunction "ETH_RD_P_9") (pintype "input"))
    )
    (net (code "43") (name "FPGA_ETH_TD_N") (class "Default")
      (node (ref "J1411") (pin "4") (pinfunction "4_4") (pintype "passive"))
      (node (ref "JB1") (pin "5") (pinfunction "ETH_TD_N_5") (pintype "output"))
    )
    (net (code "44") (name "FPGA_ETH_TD_P") (class "Default")
      (node (ref "J1411") (pin "3") (pinfunction "3_3") (pintype "passive"))
      (node (ref "JB1") (pin "3") (pinfunction "ETH_TD_P_3") (pintype "output"))
    )
    (net (code "45") (name "FPGA_FT_12MHZ") (class "Default")
      (node (ref "JB2") (pin "99") (pinfunction "B15_IO25_99") (pintype "passive"))
      (node (ref "R0941") (pin "1") (pinfunction "1_1") (pintype "passive"))
    )
    (net (code "46") (name "FPGA_FT_CTSN") (class "Default")
      (node (ref "JB2") (pin "87") (pinfunction "B15_L21_N_87") (pintype "passive"))
      (node (ref "R0964") (pin "2") (pinfunction "2_2") (pintype "passive"))
    )
    (net (code "47") (name "FPGA_FT_DCDN") (class "Default")
      (node (ref "JB2") (pin "95") (pinfunction "B15_L22_N_95") (pintype "passive"))
      (node (ref "R0967") (pin "2") (pinfunction "2_2") (pintype "passive"))
    )
    (net (code "48") (name "FPGA_FT_DSRN") (class "Default")
      (node (ref "JB2") (pin "93") (pinfunction "B15_L24_P_93") (pintype "passive"))
      (node (ref "R0966") (pin "2") (pinfunction "2_2") (pintype "passive"))
    )
    (net (code "49") (name "FPGA_FT_DTRN") (class "Default")
      (node (ref "JB2") (pin "91") (pinfunction "B15_L24_N_91") (pintype "passive"))
      (node (ref "R0965") (pin "2") (pinfunction "2_2") (pintype "passive"))
    )
    (net (code "50") (name "FPGA_FT_RESETN") (class "Default")
      (node (ref "JB2") (pin "77") (pinfunction "B15_L15_N_77") (pintype "passive"))
      (node (ref "R0912") (pin "1") (pinfunction "1_1") (pintype "passive"))
    )
    (net (code "51") (name "FPGA_FT_RIN") (class "Default")
      (node (ref "JB2") (pin "97") (pinfunction "B15_L22_P_97") (pintype "passive"))
      (node (ref "R0968") (pin "2") (pinfunction "2_2") (pintype "passive"))
    )
    (net (code "52") (name "FPGA_FT_RTSN") (class "Default")
      (node (ref "JB2") (pin "85") (pinfunction "B15_L21_P_85") (pintype "passive"))
      (node (ref "R0963") (pin "2") (pinfunction "2_2") (pintype "passive"))
    )
    (net (code "53") (name "FPGA_JTAGEN") (class "Default")
      (node (ref "JB1") (pin "90") (pinfunction "JTAGEN_90") (pintype "input"))
      (node (ref "R1339") (pin "2") (pinfunction "2_2") (pintype "passive"))
    )
    (net (code "54") (name "FPGA_LCD_BL_PWM") (class "Default")
      (node (ref "JB1") (pin "96") (pinfunction "B14_L4_MIO_P_96") (pintype "passive"))
      (node (ref "R0552") (pin "2") (pinfunction "2_2") (pintype "passive"))
    )
    (net (code "55") (name "FPGA_LED_RGB_BLUE") (class "Default")
      (node (ref "JB1") (pin "100") (pinfunction "B14_L24_MIO_N_100") (pintype "passive"))
      (node (ref "R1023") (pin "2") (pinfunction "2_2") (pintype "passive"))
    )
    (net (code "56") (name "FPGA_LED_RGB_GREEN") (class "Default")
      (node (ref "JB1") (pin "94") (pinfunction "B14_L9_MIO_N_94") (pintype "passive"))
      (node (ref "R1022") (pin "2") (pinfunction "2_2") (pintype "passive"))
    )
    (net (code "57") (name "FPGA_LED_RGB_RED") (class "Default")
      (node (ref "JB1") (pin "92") (pinfunction "B14_L9_MIO_P_92") (pintype "passive"))
      (node (ref "R1021") (pin "2") (pinfunction "2_2") (pintype "passive"))
    )
    (net (code "58") (name "FPGA_RESET") (class "Default")
      (node (ref "C1321") (pin "2") (pinfunction "2_2") (pintype "passive"))
      (node (ref "JB3") (pin "43") (pinfunction "B13_L1_N_43") (pintype "passive"))
      (node (ref "R1321") (pin "1") (pinfunction "1_1") (pintype "passive"))
    )
    (net (code "59") (name "FPGA_RFX_DET") (class "Default")
      (node (ref "R0821") (pin "2") (pinfunction "2_2") (pintype "passive"))
      (node (ref "TP_RFX_DET") (pin "TP") (pinfunction "TP_TP") (pintype "input"))
    )
    (net (code "60") (name "FPGA_RFX_MODE") (class "Default")
      (node (ref "JB2") (pin "75") (pinfunction "B15_L15_P_75") (pintype "passive"))
      (node (ref "R0861") (pin "1") (pinfunction "1_1") (pintype "passive"))
    )
    (net (code "61") (name "FPGA_SRST") (class "Default")
      (node (ref "JB2") (pin "90") (pinfunction "B15_IO0_90") (pintype "passive"))
      (node (ref "R1337") (pin "2") (pinfunction "2_2") (pintype "passive"))
    )
    (net (code "62") (name "FPGA_TCK") (class "Default")
      (node (ref "JB2") (pin "100") (pinfunction "TCK_100") (pintype "input"))
      (node (ref "R1333") (pin "2") (pinfunction "2_2") (pintype "passive"))
    )
    (net (code "63") (name "FPGA_TDI") (class "Default")
      (node (ref "JB2") (pin "96") (pinfunction "TDI_96") (pintype "input"))
      (node (ref "R1335") (pin "2") (pinfunction "2_2") (pintype "passive"))
    )
    (net (code "64") (name "FPGA_TDO") (class "Default")
      (node (ref "JB2") (pin "98") (pinfunction "TDO_98") (pintype "output"))
      (node (ref "R1334") (pin "2") (pinfunction "2_2") (pintype "passive"))
    )
    (net (code "65") (name "FPGA_TMS") (class "Default")
      (node (ref "JB2") (pin "94") (pinfunction "TMS_94") (pintype "input"))
      (node (ref "R1332") (pin "2") (pinfunction "2_2") (pintype "passive"))
    )
    (net (code "66") (name "FPGA_UART0_RXD") (class "Default")
      (node (ref "JB1") (pin "91") (pinfunction "B14_L24_MIO_P_91") (pintype "passive"))
      (node (ref "R0961") (pin "2") (pinfunction "2_2") (pintype "passive"))
    )
    (net (code "67") (name "FPGA_UART0_TXD") (class "Default")
      (node (ref "JB1") (pin "86") (pinfunction "B14_L18_MIO_N_86") (pintype "passive"))
      (node (ref "R0962") (pin "2") (pinfunction "2_2") (pintype "passive"))
    )
    (net (code "68") (name "FT_TXDEN") (class "Default")
      (node (ref "R0981") (pin "1") (pinfunction "1_1") (pintype "passive"))
      (node (ref "TP_TXDEN") (pin "TP") (pinfunction "TP_TP") (pintype "input"))
      (node (ref "U0911") (pin "21") (pinfunction "ACBUS0_21") (pintype "output"))
    )
    (net (code "69") (name "GND") (class "Default")
      (node (ref "C0501") (pin "2") (pinfunction "2_2") (pintype "passive"))
      (node (ref "C0512") (pin "2") (pinfunction "2_2") (pintype "passive"))
      (node (ref "C0611") (pin "2") (pinfunction "2_2") (pintype "passive"))
      (node (ref "C0612") (pin "2") (pinfunction "2_2") (pintype "passive"))
      (node (ref "C0621") (pin "2") (pinfunction "2_2") (pintype "passive"))
      (node (ref "C0651") (pin "2") (pinfunction "2_2") (pintype "passive"))
      (node (ref "C0701") (pin "2") (pinfunction "2_2") (pintype "passive"))
      (node (ref "C0703") (pin "2") (pinfunction "2_2") (pintype "passive"))
      (node (ref "C0704") (pin "2") (pinfunction "2_2") (pintype "passive"))
      (node (ref "C0706") (pin "1") (pinfunction "1_1") (pintype "passive"))
      (node (ref "C0707") (pin "1") (pinfunction "1_1") (pintype "passive"))
      (node (ref "C0708") (pin "1") (pinfunction "1_1") (pintype "passive"))
      (node (ref "C0711") (pin "2") (pinfunction "2_2") (pintype "passive"))
      (node (ref "C0713") (pin "1") (pinfunction "1_1") (pintype "passive"))
      (node (ref "C0811") (pin "2") (pinfunction "2_2") (pintype "passive"))
      (node (ref "C0851") (pin "2") (pinfunction "2_2") (pintype "passive"))
      (node (ref "C0852") (pin "2") (pinfunction "2_2") (pintype "passive"))
      (node (ref "C0853") (pin "2") (pinfunction "2_2") (pintype "passive"))
      (node (ref "C0891") (pin "2") (pinfunction "2_2") (pintype "passive"))
      (node (ref "C0893") (pin "2") (pinfunction "2_2") (pintype "passive"))
      (node (ref "C0895") (pin "2") (pinfunction "2_2") (pintype "passive"))
      (node (ref "C0897") (pin "2") (pinfunction "2_2") (pintype "passive"))
      (node (ref "C0911") (pin "2") (pinfunction "2_2") (pintype "passive"))
      (node (ref "C0912") (pin "2") (pinfunction "2_2") (pintype "passive"))
      (node (ref "C0913") (pin "1") (pinfunction "1_1") (pintype "passive"))
      (node (ref "C0914") (pin "1") (pinfunction "1_1") (pintype "passive"))
      (node (ref "C0916") (pin "2") (pinfunction "2_2") (pintype "passive"))
      (node (ref "C0917") (pin "2") (pinfunction "2_2") (pintype "passive"))
      (node (ref "C0918") (pin "2") (pinfunction "2_2") (pintype "passive"))
      (node (ref "C0921") (pin "1") (pinfunction "1_1") (pintype "passive"))
      (node (ref "C0922") (pin "1") (pinfunction "1_1") (pintype "passive"))
      (node (ref "C0923") (pin "2") (pinfunction "2_2") (pintype "passive"))
      (node (ref "C0924") (pin "2") (pinfunction "2_2") (pintype "passive"))
      (node (ref "C1011") (pin "2") (pinfunction "2_2") (pintype "passive"))
      (node (ref "C1012") (pin "2") (pinfunction "2_2") (pintype "passive"))
      (node (ref "C1013") (pin "2") (pinfunction "2_2") (pintype "passive"))
      (node (ref "C1101") (pin "1") (pinfunction "1_1") (pintype "passive"))
      (node (ref "C1102") (pin "1") (pinfunction "1_1") (pintype "passive"))
      (node (ref "C1111") (pin "1") (pinfunction "1_1") (pintype "passive"))
      (node (ref "C1112") (pin "1") (pinfunction "1_1") (pintype "passive"))
      (node (ref "C1113") (pin "1") (pinfunction "1_1") (pintype "passive"))
      (node (ref "C1114") (pin "1") (pinfunction "1_1") (pintype "passive"))
      (node (ref "C1122") (pin "2") (pinfunction "2_2") (pintype "passive"))
      (node (ref "C1151") (pin "2") (pinfunction "2_2") (pintype "passive"))
      (node (ref "C1152") (pin "2") (pinfunction "2_2") (pintype "passive"))
      (node (ref "C1153") (pin "2") (pinfunction "2_2") (pintype "passive"))
      (node (ref "C1201") (pin "2") (pinfunction "2_2") (pintype "passive"))
      (node (ref "C1221") (pin "2") (pinfunction "2_2") (pintype "passive"))
      (node (ref "C1311") (pin "1") (pinfunction "1_1") (pintype "passive"))
      (node (ref "C1321") (pin "1") (pinfunction "1_1") (pintype "passive"))
      (node (ref "C1381") (pin "1") (pinfunction "1_1") (pintype "passive"))
      (node (ref "C1431") (pin "2") (pinfunction "2_2") (pintype "passive"))
      (node (ref "C1432") (pin "2") (pinfunction "2_2") (pintype "passive"))
      (node (ref "C1441") (pin "2") (pinfunction "2_2") (pintype "passive"))
      (node (ref "C1442") (pin "2") (pinfunction "2_2") (pintype "passive"))
      (node (ref "D1021") (pin "1") (pinfunction "BC_1") (pintype "passive"))
      (node (ref "D1021") (pin "2") (pinfunction "GC_2") (pintype "passive"))
      (node (ref "D1021") (pin "3") (pinfunction "RC_3") (pintype "passive"))
      (node (ref "H1511") (pin "B3,2") (pinfunction "MOUNT_B3,2") (pintype "passive"))
      (node (ref "H1512") (pin "B3,2") (pinfunction "MOUNT_B3,2") (pintype "passive"))
      (node (ref "H1513") (pin "B3,2") (pinfunction "MOUNT_B3,2") (pintype "passive"))
      (node (ref "H1514") (pin "B3,2") (pinfunction "MOUNT_B3,2") (pintype "passive"))
      (node (ref "HB_351") (pin "B3,2") (pinfunction "MOUNT_B3,2") (pintype "passive"))
      (node (ref "HB_352") (pin "B3,2") (pinfunction "MOUNT_B3,2") (pintype "passive"))
      (node (ref "HB_353") (pin "B3,2") (pinfunction "MOUNT_B3,2") (pintype "passive"))
      (node (ref "HB_354") (pin "B3,2") (pinfunction "MOUNT_B3,2") (pintype "passive"))
      (node (ref "J1411") (pin "10") (pinfunction "10_10") (pintype "passive"))
      (node (ref "J1411") (pin "11") (pinfunction "11_11") (pintype "passive"))
      (node (ref "J1411") (pin "2") (pinfunction "2_2") (pintype "passive"))
      (node (ref "J1411") (pin "GND@11") (pinfunction "13_GND@11") (pintype "passive"))
      (node (ref "J1411") (pin "GND@12") (pinfunction "13_GND@12") (pintype "passive"))
      (node (ref "J1411") (pin "GND@21") (pinfunction "13_GND@21") (pintype "passive"))
      (node (ref "J1411") (pin "GND@22") (pinfunction "13_GND@22") (pintype "passive"))
      (node (ref "JB1") (pin "1") (pinfunction "GND_1") (pintype "passive"))
      (node (ref "JB1") (pin "19") (pinfunction "GND_19") (pintype "passive"))
      (node (ref "JB1") (pin "25") (pinfunction "GND_25") (pintype "passive"))
      (node (ref "JB1") (pin "30") (pinfunction "GND_30") (pintype "passive"))
      (node (ref "JB1") (pin "33") (pinfunction "GND_33") (pintype "passive"))
      (node (ref "JB1") (pin "43") (pinfunction "GND_43") (pintype "passive"))
      (node (ref "JB1") (pin "53") (pinfunction "GND_53") (pintype "passive"))
      (node (ref "JB1") (pin "54") (pinfunction "GND_54") (pintype "passive"))
      (node (ref "JB1") (pin "63") (pinfunction "GND_63") (pintype "passive"))
      (node (ref "JB1") (pin "64") (pinfunction "GND_64") (pintype "passive"))
      (node (ref "JB1") (pin "7") (pinfunction "GND_7") (pintype "passive"))
      (node (ref "JB1") (pin "73") (pinfunction "GND_73") (pintype "passive"))
      (node (ref "JB1") (pin "74") (pinfunction "GND_74") (pintype "passive"))
      (node (ref "JB1") (pin "83") (pinfunction "GND_83") (pintype "passive"))
      (node (ref "JB1") (pin "89") (pinfunction "GND_89") (pintype "passive"))
      (node (ref "JB1") (pin "F1") (pinfunction "F1_F1") (pintype "passive"))
      (node (ref "JB1") (pin "F2") (pinfunction "F2_F2") (pintype "passive"))
      (node (ref "JB2") (pin "19") (pinfunction "GND_19") (pintype "passive"))
      (node (ref "JB2") (pin "29") (pinfunction "GND_29") (pintype "passive"))
      (node (ref "JB2") (pin "39") (pinfunction "GND_39") (pintype "passive"))
      (node (ref "JB2") (pin "40") (pinfunction "GND_40") (pintype "passive"))
      (node (ref "JB2") (pin "49") (pinfunction "GND_49") (pintype "passive"))
      (node (ref "JB2") (pin "50") (pinfunction "GND_50") (pintype "passive"))
      (node (ref "JB2") (pin "59") (pinfunction "GND_59") (pintype "passive"))
      (node (ref "JB2") (pin "60") (pinfunction "GND_60") (pintype "passive"))
      (node (ref "JB2") (pin "69") (pinfunction "GND_69") (pintype "passive"))
      (node (ref "JB2") (pin "70") (pinfunction "GND_70") (pintype "passive"))
      (node (ref "JB2") (pin "79") (pinfunction "GND_79") (pintype "passive"))
      (node (ref "JB2") (pin "80") (pinfunction "GND_80") (pintype "passive"))
      (node (ref "JB2") (pin "89") (pinfunction "GND_89") (pintype "passive"))
      (node (ref "JB2") (pin "F1") (pinfunction "F1_F1") (pintype "passive"))
      (node (ref "JB2") (pin "F2") (pinfunction "F2_F2") (pintype "passive"))
      (node (ref "JB3") (pin "11") (pinfunction "GND_11") (pintype "passive"))
      (node (ref "JB3") (pin "17") (pinfunction "GND_17") (pintype "passive"))
      (node (ref "JB3") (pin "18") (pinfunction "GND_18") (pintype "passive"))
      (node (ref "JB3") (pin "23") (pinfunction "GND_23") (pintype "passive"))
      (node (ref "JB3") (pin "24") (pinfunction "GND_24") (pintype "passive"))
      (node (ref "JB3") (pin "29") (pinfunction "GND_29") (pintype "passive"))
      (node (ref "JB3") (pin "30") (pinfunction "GND_30") (pintype "passive"))
      (node (ref "JB3") (pin "35") (pinfunction "GND_35") (pintype "passive"))
      (node (ref "JB3") (pin "36") (pinfunction "GND_36") (pintype "passive"))
      (node (ref "JB3") (pin "45") (pinfunction "GND_45") (pintype "passive"))
      (node (ref "JB3") (pin "46") (pinfunction "GND_46") (pintype "passive"))
      (node (ref "JB3") (pin "5") (pinfunction "GND_5") (pintype "passive"))
      (node (ref "JB3") (pin "6") (pinfunction "GND_6") (pintype "passive"))
      (node (ref "JB3") (pin "F1") (pinfunction "F1_F1") (pintype "passive"))
      (node (ref "JB3") (pin "F2") (pinfunction "F2_F2") (pintype "passive"))
      (node (ref "L0721") (pin "1") (pinfunction "COM_1") (pintype "passive"))
      (node (ref "L0722") (pin "2") (pinfunction "COM_2") (pintype "passive"))
      (node (ref "L0722") (pin "5") (pinfunction "G_N_D_5") (pintype "passive"))
      (node (ref "L0821") (pin "2") (pinfunction "2_2") (pintype "passive"))
      (node (ref "L0911") (pin "1") (pinfunction "1_1") (pintype "passive"))
      (node (ref "R0531") (pin "1") (pinfunction "1_1") (pintype "passive"))
      (node (ref "R0551") (pin "1") (pinfunction "1_1") (pintype "passive"))
      (node (ref "R0553") (pin "1") (pinfunction "1_1") (pintype "passive"))
      (node (ref "R0822") (pin "1") (pinfunction "1_1") (pintype "passive"))
      (node (ref "R0911") (pin "1") (pinfunction "1_1") (pintype "passive"))
      (node (ref "R0913") (pin "1") (pinfunction "1_1") (pintype "passive"))
      (node (ref "R1101") (pin "1") (pinfunction "1_1") (pintype "passive"))
      (node (ref "R1103") (pin "1") (pinfunction "1_1") (pintype "passive"))
      (node (ref "R1105") (pin "1") (pinfunction "1_1") (pintype "passive"))
      (node (ref "R1106") (pin "1") (pinfunction "1_1") (pintype "passive"))
      (node (ref "R1311") (pin "1") (pinfunction "1_1") (pintype "passive"))
      (node (ref "R1338") (pin "2") (pinfunction "2_2") (pintype "passive"))
      (node (ref "U0501") (pin "5") (pinfunction "VSS_5") (pintype "power_in"))
      (node (ref "U0601") (pin "2") (pinfunction "ADDR_2") (pintype "input"))
      (node (ref "U0601") (pin "8") (pinfunction "GND_8") (pintype "passive"))
      (node (ref "U0651") (pin "2") (pinfunction "GND_2") (pintype "passive"))
      (node (ref "U0701") (pin "10") (pinfunction "AVSS_10") (pintype "passive"))
      (node (ref "U0701") (pin "16") (pinfunction "AVSS_16") (pintype "passive"))
      (node (ref "U0701") (pin "18") (pinfunction "XTAL2_18") (pintype "passive"))
      (node (ref "U0701") (pin "19") (pinfunction "AVSS_19") (pintype "passive"))
      (node (ref "U0701") (pin "20") (pinfunction "DVSS_20") (pintype "passive"))
      (node (ref "U0701") (pin "23") (pinfunction "DVSS_23") (pintype "passive"))
      (node (ref "U0701") (pin "24") (pinfunction "DVSS_24") (pintype "passive"))
      (node (ref "U0701") (pin "3") (pinfunction "AVSS_3") (pintype "passive"))
      (node (ref "U0701") (pin "32") (pinfunction "DVSS_32") (pintype "passive"))
      (node (ref "U0701") (pin "38") (pinfunction "DVSS_38") (pintype "passive"))
      (node (ref "U0701") (pin "45") (pinfunction "AVSS_45") (pintype "passive"))
      (node (ref "U0701") (pin "48") (pinfunction "AVSS_48") (pintype "passive"))
      (node (ref "U0701") (pin "49") (pinfunction "AVSS_49") (pintype "passive"))
      (node (ref "U0701") (pin "6") (pinfunction "AVSS_6") (pintype "passive"))
      (node (ref "U0701") (pin "7") (pinfunction "AVSS_7") (pintype "passive"))
      (node (ref "U0711") (pin "2") (pinfunction "GND_2") (pintype "power_in"))
      (node (ref "U0811") (pin "2") (pinfunction "GND_2") (pintype "power_in"))
      (node (ref "U0821") (pin "17") (pinfunction "VSS_17") (pintype "passive"))
      (node (ref "U0821") (pin "4") (pinfunction "VSS_4") (pintype "passive"))
      (node (ref "U0821") (pin "8") (pinfunction "VSS_8") (pintype "passive"))
      (node (ref "U0881") (pin "1") (pinfunction "GROUND_1") (pintype "passive"))
      (node (ref "U0881") (pin "3") (pinfunction "GROUND_3") (pintype "passive"))
      (node (ref "U0881") (pin "4") (pinfunction "GROUND_4") (pintype "passive"))
      (node (ref "U0881") (pin "6") (pinfunction "GROUND_6") (pintype "passive"))
      (node (ref "U0911") (pin "10") (pinfunction "GND_10") (pintype "passive"))
      (node (ref "U0911") (pin "11") (pinfunction "GND_11") (pintype "passive"))
      (node (ref "U0911") (pin "22") (pinfunction "GND_22") (pintype "passive"))
      (node (ref "U0911") (pin "23") (pinfunction "GND_23") (pintype "passive"))
      (node (ref "U0911") (pin "35") (pinfunction "GND_35") (pintype "passive"))
      (node (ref "U0911") (pin "36") (pinfunction "GND_36") (pintype "passive"))
      (node (ref "U0911") (pin "42") (pinfunction "TEST_42") (pintype "input"))
      (node (ref "U0911") (pin "47") (pinfunction "GND_47") (pintype "passive"))
      (node (ref "U0911") (pin "48") (pinfunction "GND_48") (pintype "passive"))
      (node (ref "U1101") (pin "23") (pinfunction "VSS_PAD_23") (pintype "passive"))
      (node (ref "U1101") (pin "24") (pinfunction "VSS_PAD_24") (pintype "passive"))
      (node (ref "U1101") (pin "P$1") (pinfunction "VSS_PAD_P$1") (pintype "passive"))
      (node (ref "U1101") (pin "P$10") (pinfunction "VSS_PAD_P$10") (pintype "passive"))
      (node (ref "U1101") (pin "P$11") (pinfunction "VSS_PAD_P$11") (pintype "passive"))
      (node (ref "U1101") (pin "P$12") (pinfunction "VSS_PAD_P$12") (pintype "passive"))
      (node (ref "U1101") (pin "P$13") (pinfunction "VSS_PAD_P$13") (pintype "passive"))
      (node (ref "U1101") (pin "P$14") (pinfunction "VSS_PAD_P$14") (pintype "passive"))
      (node (ref "U1101") (pin "P$15") (pinfunction "VSS_PAD_P$15") (pintype "passive"))
      (node (ref "U1101") (pin "P$16") (pinfunction "VSS_PAD_P$16") (pintype "passive"))
      (node (ref "U1101") (pin "P$17") (pinfunction "VSS_PAD_P$17") (pintype "passive"))
      (node (ref "U1101") (pin "P$18") (pinfunction "VSS_PAD_P$18") (pintype "passive"))
      (node (ref "U1101") (pin "P$19") (pinfunction "VSS_PAD_P$19") (pintype "passive"))
      (node (ref "U1101") (pin "P$2") (pinfunction "VSS_PAD_P$2") (pintype "passive"))
      (node (ref "U1101") (pin "P$20") (pinfunction "VSS_PAD_P$20") (pintype "passive"))
      (node (ref "U1101") (pin "P$21") (pinfunction "VSS_PAD_P$21") (pintype "passive"))
      (node (ref "U1101") (pin "P$3") (pinfunction "VSS_PAD_P$3") (pintype "passive"))
      (node (ref "U1101") (pin "P$4") (pinfunction "VSS_PAD_P$4") (pintype "passive"))
      (node (ref "U1101") (pin "P$5") (pinfunction "VSS_PAD_P$5") (pintype "passive"))
      (node (ref "U1101") (pin "P$6") (pinfunction "VSS_PAD_P$6") (pintype "passive"))
      (node (ref "U1101") (pin "P$7") (pinfunction "VSS_PAD_P$7") (pintype "passive"))
      (node (ref "U1101") (pin "P$8") (pinfunction "VSS_PAD_P$8") (pintype "passive"))
      (node (ref "U1101") (pin "P$9") (pinfunction "VSS_PAD_P$9") (pintype "passive"))
      (node (ref "U1211") (pin "13") (pinfunction "VSS_13") (pintype "passive"))
      (node (ref "U1211") (pin "14") (pinfunction "VSS_14") (pintype "passive"))
      (node (ref "U1211") (pin "3") (pinfunction "VSS_3") (pintype "passive"))
      (node (ref "U1211") (pin "4") (pinfunction "EN_VIN_SW_4") (pintype "input"))
      (node (ref "U1211") (pin "8") (pinfunction "VSEL4_8") (pintype "input"))
      (node (ref "U1211") (pin "G1") (pinfunction "VSS_G1") (pintype "passive"))
      (node (ref "U1211") (pin "G2") (pinfunction "VSS_G2") (pintype "passive"))
      (node (ref "U1211") (pin "G3") (pinfunction "VSS_G3") (pintype "passive"))
      (node (ref "X0891") (pin "GND1") (pinfunction "GND_GND1") (pintype "bidirectional"))
      (node (ref "X0891") (pin "GND2") (pinfunction "GND_GND2") (pintype "bidirectional"))
      (node (ref "X0891") (pin "GND3") (pinfunction "GND_GND3") (pintype "bidirectional"))
      (node (ref "X0891") (pin "GND4") (pinfunction "GND_GND4") (pintype "bidirectional"))
      (node (ref "X0895") (pin "GND1") (pinfunction "GND_GND1") (pintype "bidirectional"))
      (node (ref "X0895") (pin "GND2") (pinfunction "GND_GND2") (pintype "bidirectional"))
      (node (ref "X0895") (pin "GND3") (pinfunction "GND_GND3") (pintype "bidirectional"))
      (node (ref "X0895") (pin "GND4") (pinfunction "GND_GND4") (pintype "bidirectional"))
      (node (ref "X1011") (pin "C") (pinfunction "C_C") (pintype "passive"))
      (node (ref "X1011") (pin "D") (pinfunction "D_D") (pintype "passive"))
      (node (ref "X1311") (pin "GND") (pinfunction "GND_GND") (pintype "passive"))
      (node (ref "X1331") (pin "1") (pinfunction "1_1") (pintype "passive"))
      (node (ref "X1331") (pin "11") (pinfunction "11_11") (pintype "passive"))
      (node (ref "X1331") (pin "13") (pinfunction "13_13") (pintype "passive"))
      (node (ref "X1331") (pin "3") (pinfunction "3_3") (pintype "passive"))
      (node (ref "X1331") (pin "5") (pinfunction "5_5") (pintype "passive"))
      (node (ref "X1331") (pin "7") (pinfunction "7_7") (pintype "passive"))
      (node (ref "X1331") (pin "9") (pinfunction "9_9") (pintype "passive"))
      (node (ref "X1361") (pin "8") (pinfunction "8_8") (pintype "passive"))
    )
    (net (code "70") (name "LCD_BL_B") (class "Default")
      (node (ref "R0551") (pin "2") (pinfunction "2_2") (pintype "passive"))
      (node (ref "R0552") (pin "1") (pinfunction "1_1") (pintype "passive"))
      (node (ref "T0551") (pin "1") (pinfunction "B_1") (pintype "passive"))
    )
    (net (code "71") (name "LCD_NRST") (class "Default")
      (node (ref "R0531") (pin "2") (pinfunction "2_2") (pintype "passive"))
      (node (ref "R0532") (pin "2") (pinfunction "2_2") (pintype "passive"))
      (node (ref "U0501") (pin "8") (pinfunction "RST_8") (pintype "input"))
    )
    (net (code "72") (name "Net-(C0703-Pad1)") (class "Default")
      (node (ref "C0703") (pin "1") (pinfunction "1_1") (pintype "passive"))
      (node (ref "L0703") (pin "2") (pinfunction "2_2") (pintype "passive"))
      (node (ref "U0701") (pin "21") (pinfunction "DEVDD_21") (pintype "power_in"))
      (node (ref "U0701") (pin "29") (pinfunction "DEVDD_29") (pintype "power_in"))
      (node (ref "U0701") (pin "39") (pinfunction "DEVDD_39") (pintype "power_in"))
    )
    (net (code "73") (name "Net-(C0704-Pad1)") (class "Default")
      (node (ref "C0704") (pin "1") (pinfunction "1_1") (pintype "passive"))
      (node (ref "L0704") (pin "2") (pinfunction "2_2") (pintype "passive"))
      (node (ref "U0701") (pin "15") (pinfunction "EVDD_15") (pintype "power_in"))
      (node (ref "U0701") (pin "46") (pinfunction "EVDD_46") (pintype "power_in"))
    )
    (net (code "74") (name "Net-(C0891-Pad1)") (class "Default")
      (node (ref "C0891") (pin "1") (pinfunction "1_1") (pintype "passive"))
      (node (ref "L0892") (pin "2") (pinfunction "2_2") (pintype "passive"))
      (node (ref "X0891") (pin "ANT1") (pinfunction "SIGNAL_ANT1") (pintype "bidirectional"))
      (node (ref "X0891") (pin "ANT2") (pinfunction "SIGNAL_ANT2") (pintype "bidirectional"))
      (node (ref "X0891") (pin "ANT3") (pinfunction "SIGNAL_ANT3") (pintype "bidirectional"))
    )
    (net (code "75") (name "Net-(C0895-Pad1)") (class "Default")
      (node (ref "C0895") (pin "1") (pinfunction "1_1") (pintype "passive"))
      (node (ref "L0896") (pin "2") (pinfunction "2_2") (pintype "passive"))
      (node (ref "X0895") (pin "ANT1") (pinfunction "SIGNAL_ANT1") (pintype "bidirectional"))
      (node (ref "X0895") (pin "ANT2") (pinfunction "SIGNAL_ANT2") (pintype "bidirectional"))
      (node (ref "X0895") (pin "ANT3") (pinfunction "SIGNAL_ANT3") (pintype "bidirectional"))
    )
    (net (code "76") (name "Net-(C1011-Pad1)") (class "Default")
      (node (ref "C1011") (pin "1") (pinfunction "1_1") (pintype "passive"))
      (node (ref "R1011") (pin "1") (pinfunction "1_1") (pintype "passive"))
      (node (ref "X1011") (pin "A") (pinfunction "A_A") (pintype "passive"))
    )
    (net (code "77") (name "Net-(C1012-Pad1)") (class "Default")
      (node (ref "C1012") (pin "1") (pinfunction "1_1") (pintype "passive"))
      (node (ref "R1012") (pin "1") (pinfunction "1_1") (pintype "passive"))
      (node (ref "X1011") (pin "B") (pinfunction "B_B") (pintype "passive"))
    )
    (net (code "78") (name "Net-(C1013-Pad1)") (class "Default")
      (node (ref "C1013") (pin "1") (pinfunction "1_1") (pintype "passive"))
      (node (ref "R1013") (pin "1") (pinfunction "1_1") (pintype "passive"))
      (node (ref "X1011") (pin "E") (pinfunction "E_E") (pintype "passive"))
    )
    (net (code "79") (name "Net-(C1108-Pad1)") (class "Default")
      (node (ref "C1108") (pin "1") (pinfunction "1_1") (pintype "passive"))
      (node (ref "L1101") (pin "2") (pinfunction "2_2") (pintype "passive"))
      (node (ref "R1122") (pin "2") (pinfunction "2_2") (pintype "passive"))
      (node (ref "R1131") (pin "1") (pinfunction "1_1") (pintype "passive"))
      (node (ref "U1101") (pin "10") (pinfunction "LL_10") (pintype "passive"))
      (node (ref "U1101") (pin "11") (pinfunction "LL_11") (pintype "passive"))
      (node (ref "U1101") (pin "6") (pinfunction "LL_6") (pintype "passive"))
      (node (ref "U1101") (pin "7") (pinfunction "LL_7") (pintype "passive"))
      (node (ref "U1101") (pin "8") (pinfunction "LL_8") (pintype "passive"))
      (node (ref "U1101") (pin "9") (pinfunction "LL_9") (pintype "passive"))
    )
    (net (code "80") (name "Net-(C1108-Pad2)") (class "Default")
      (node (ref "C1108") (pin "2") (pinfunction "2_2") (pintype "passive"))
      (node (ref "R1108") (pin "2") (pinfunction "2_2") (pintype "passive"))
    )
    (net (code "81") (name "Net-(C1122-Pad1)") (class "Default")
      (node (ref "C1122") (pin "1") (pinfunction "1_1") (pintype "passive"))
      (node (ref "R1122") (pin "1") (pinfunction "1_1") (pintype "passive"))
    )
    (net (code "82") (name "Net-(C1131-Pad2)") (class "Default")
      (node (ref "C1131") (pin "2") (pinfunction "2_2") (pintype "passive"))
      (node (ref "C1132") (pin "1") (pinfunction "1_1") (pintype "passive"))
      (node (ref "R1131") (pin "2") (pinfunction "2_2") (pintype "passive"))
    )
    (net (code "83") (name "Net-(C1311-Pad2)") (class "Default")
      (node (ref "C1311") (pin "2") (pinfunction "2_2") (pintype "passive"))
      (node (ref "R1311") (pin "2") (pinfunction "2_2") (pintype "passive"))
      (node (ref "X1311") (pin "JSHIELD") (pinfunction "SHIELD_JSHIELD") (pintype "passive"))
      (node (ref "X1311") (pin "JSHIELD@2") (pinfunction "SHIELD_JSHIELD@2") (pintype "passive"))
      (node (ref "X1311") (pin "JSHIELD@3") (pinfunction "SHIELD_JSHIELD@3") (pintype "passive"))
      (node (ref "X1311") (pin "JSHIELD@4") (pinfunction "SHIELD_JSHIELD@4") (pintype "passive"))
      (node (ref "X1311") (pin "JSHIELD@5") (pinfunction "SHIELD_JSHIELD@5") (pintype "passive"))
      (node (ref "X1311") (pin "JSHIELD@6") (pinfunction "SHIELD_JSHIELD@6") (pintype "passive"))
    )
    (net (code "84") (name "Net-(D0971-PadC)") (class "Default")
      (node (ref "D0971") (pin "C") (pinfunction "C_C") (pintype "passive"))
      (node (ref "R0971") (pin "2") (pinfunction "2_2") (pintype "passive"))
    )
    (net (code "85") (name "Net-(D0972-PadC)") (class "Default")
      (node (ref "D0972") (pin "C") (pinfunction "C_C") (pintype "passive"))
      (node (ref "R0972") (pin "2") (pinfunction "2_2") (pintype "passive"))
    )
    (net (code "86") (name "Net-(D1021-BA)") (class "Default")
      (node (ref "D1021") (pin "6") (pinfunction "BA_6") (pintype "passive"))
      (node (ref "R1023") (pin "1") (pinfunction "1_1") (pintype "passive"))
    )
    (net (code "87") (name "Net-(D1021-GA)") (class "Default")
      (node (ref "D1021") (pin "5") (pinfunction "GA_5") (pintype "passive"))
      (node (ref "R1022") (pin "1") (pinfunction "1_1") (pintype "passive"))
    )
    (net (code "88") (name "Net-(D1021-RA)") (class "Default")
      (node (ref "D1021") (pin "4") (pinfunction "RA_4") (pintype "passive"))
      (node (ref "R1021") (pin "1") (pinfunction "1_1") (pintype "passive"))
    )
    (net (code "89") (name "Net-(J1411-Pad1)") (class "Default")
      (node (ref "J1411") (pin "1") (pinfunction "1_1") (pintype "passive"))
      (node (ref "R1421") (pin "2") (pinfunction "2_2") (pintype "passive"))
    )
    (net (code "90") (name "Net-(J1411-Pad12)") (class "Default")
      (node (ref "J1411") (pin "12") (pinfunction "12_12") (pintype "passive"))
      (node (ref "R1422") (pin "2") (pinfunction "2_2") (pintype "passive"))
    )
    (net (code "91") (name "Net-(JB1-EN1)") (class "Default")
      (node (ref "FPGA_EN1") (pin "TP") (pinfunction "TP_TP") (pintype "input"))
      (node (ref "JB1") (pin "27") (pinfunction "EN1_27") (pintype "input"))
    )
    (net (code "92") (name "Net-(JB1-MODE)") (class "Default")
      (node (ref "FPGA_MODE") (pin "TP") (pinfunction "TP_TP") (pintype "input"))
      (node (ref "JB1") (pin "31") (pinfunction "MODE_31") (pintype "input"))
    )
    (net (code "93") (name "Net-(JB1-PGOOD)") (class "Default")
      (node (ref "JB1") (pin "29") (pinfunction "PGOOD_29") (pintype "output"))
      (node (ref "PGOOD") (pin "TP") (pinfunction "TP_TP") (pintype "input"))
    )
    (net (code "94") (name "Net-(JB2-RESIN)") (class "Default")
      (node (ref "JB2") (pin "17") (pinfunction "RESIN_17") (pintype "input"))
      (node (ref "R0203") (pin "1") (pinfunction "1_1") (pintype "passive"))
      (node (ref "TP_RESIN") (pin "TP") (pinfunction "TP_TP") (pintype "input"))
    )
    (net (code "95") (name "Net-(L0721-B1)") (class "Default")
      (node (ref "L0721") (pin "3") (pinfunction "B1_3") (pintype "passive"))
      (node (ref "U0701") (pin "8") (pinfunction "RF09P_8") (pintype "passive"))
    )
    (net (code "96") (name "Net-(L0721-B2)") (class "Default")
      (node (ref "L0721") (pin "2") (pinfunction "B2_2") (pintype "passive"))
      (node (ref "U0701") (pin "9") (pinfunction "RF09N_9") (pintype "passive"))
    )
    (net (code "97") (name "Net-(L0722-B1)") (class "Default")
      (node (ref "L0722") (pin "3") (pinfunction "B1_3") (pintype "passive"))
      (node (ref "U0701") (pin "4") (pinfunction "RF24P_4") (pintype "passive"))
    )
    (net (code "98") (name "Net-(L0722-B2)") (class "Default")
      (node (ref "L0722") (pin "4") (pinfunction "B2_4") (pintype "passive"))
      (node (ref "U0701") (pin "5") (pinfunction "RF24N_5") (pintype "passive"))
    )
    (net (code "99") (name "Net-(L0911-Pad2)") (class "Default")
      (node (ref "L0911") (pin "2") (pinfunction "2_2") (pintype "passive"))
      (node (ref "U0911") (pin "4") (pinfunction "AGND_4") (pintype "passive"))
      (node (ref "U0911") (pin "41") (pinfunction "AGND_41") (pintype "passive"))
      (node (ref "U0911") (pin "9") (pinfunction "AGND_9") (pintype "passive"))
    )
    (net (code "100") (name "Net-(R1331-Pad1)") (class "Default")
      (node (ref "R1331") (pin "1") (pinfunction "1_1") (pintype "passive"))
      (node (ref "X1331") (pin "2") (pinfunction "2_2") (pintype "passive"))
    )
    (net (code "101") (name "Net-(R1332-Pad1)") (class "Default")
      (node (ref "R1332") (pin "1") (pinfunction "1_1") (pintype "passive"))
      (node (ref "X1331") (pin "4") (pinfunction "4_4") (pintype "passive"))
    )
    (net (code "102") (name "Net-(R1333-Pad1)") (class "Default")
      (node (ref "R1333") (pin "1") (pinfunction "1_1") (pintype "passive"))
      (node (ref "X1331") (pin "6") (pinfunction "6_6") (pintype "passive"))
    )
    (net (code "103") (name "Net-(R1334-Pad1)") (class "Default")
      (node (ref "R1334") (pin "1") (pinfunction "1_1") (pintype "passive"))
      (node (ref "X1331") (pin "8") (pinfunction "8_8") (pintype "passive"))
    )
    (net (code "104") (name "Net-(R1335-Pad1)") (class "Default")
      (node (ref "R1335") (pin "1") (pinfunction "1_1") (pintype "passive"))
      (node (ref "X1331") (pin "10") (pinfunction "10_10") (pintype "passive"))
    )
    (net (code "105") (name "Net-(R1337-Pad1)") (class "Default")
      (node (ref "R1337") (pin "1") (pinfunction "1_1") (pintype "passive"))
      (node (ref "X1331") (pin "14") (pinfunction "14_14") (pintype "passive"))
    )
    (net (code "106") (name "Net-(R1338-Pad1)") (class "Default")
      (node (ref "R1338") (pin "1") (pinfunction "1_1") (pintype "passive"))
      (node (ref "R1339") (pin "1") (pinfunction "1_1") (pintype "passive"))
      (node (ref "X1332") (pin "2") (pinfunction "2_2") (pintype "passive"))
    )
    (net (code "107") (name "Net-(R1351-Pad2)") (class "Default")
      (node (ref "R1351") (pin "2") (pinfunction "2_2") (pintype "passive"))
      (node (ref "X1351") (pin "1") (pinfunction "1_1") (pintype "passive"))
    )
    (net (code "108") (name "Net-(R1352-Pad2)") (class "Default")
      (node (ref "R1352") (pin "2") (pinfunction "2_2") (pintype "passive"))
      (node (ref "X1351") (pin "2") (pinfunction "2_2") (pintype "passive"))
    )
    (net (code "109") (name "Net-(R1353-Pad2)") (class "Default")
      (node (ref "R1353") (pin "2") (pinfunction "2_2") (pintype "passive"))
      (node (ref "X1351") (pin "3") (pinfunction "3_3") (pintype "passive"))
    )
    (net (code "110") (name "Net-(R1354-Pad2)") (class "Default")
      (node (ref "R1354") (pin "2") (pinfunction "2_2") (pintype "passive"))
      (node (ref "X1351") (pin "4") (pinfunction "4_4") (pintype "passive"))
    )
    (net (code "111") (name "Net-(R1355-Pad2)") (class "Default")
      (node (ref "R1355") (pin "2") (pinfunction "2_2") (pintype "passive"))
      (node (ref "X1351") (pin "5") (pinfunction "5_5") (pintype "passive"))
    )
    (net (code "112") (name "Net-(R1356-Pad2)") (class "Default")
      (node (ref "R1356") (pin "2") (pinfunction "2_2") (pintype "passive"))
      (node (ref "X1351") (pin "6") (pinfunction "6_6") (pintype "passive"))
    )
    (net (code "113") (name "Net-(R1357-Pad2)") (class "Default")
      (node (ref "R1357") (pin "2") (pinfunction "2_2") (pintype "passive"))
      (node (ref "X1351") (pin "7") (pinfunction "7_7") (pintype "passive"))
    )
    (net (code "114") (name "Net-(R1358-Pad2)") (class "Default")
      (node (ref "R1358") (pin "2") (pinfunction "2_2") (pintype "passive"))
      (node (ref "X1351") (pin "8") (pinfunction "8_8") (pintype "passive"))
    )
    (net (code "115") (name "Net-(R1361-Pad2)") (class "Default")
      (node (ref "R1361") (pin "2") (pinfunction "2_2") (pintype "passive"))
      (node (ref "X1361") (pin "1") (pinfunction "1_1") (pintype "passive"))
    )
    (net (code "116") (name "Net-(R1362-Pad2)") (class "Default")
      (node (ref "R1362") (pin "2") (pinfunction "2_2") (pintype "passive"))
      (node (ref "X1361") (pin "2") (pinfunction "2_2") (pintype "passive"))
    )
    (net (code "117") (name "Net-(R1363-Pad2)") (class "Default")
      (node (ref "R1363") (pin "2") (pinfunction "2_2") (pintype "passive"))
      (node (ref "X1361") (pin "3") (pinfunction "3_3") (pintype "passive"))
    )
    (net (code "118") (name "Net-(R1364-Pad2)") (class "Default")
      (node (ref "R1364") (pin "2") (pinfunction "2_2") (pintype "passive"))
      (node (ref "X1361") (pin "4") (pinfunction "4_4") (pintype "passive"))
    )
    (net (code "119") (name "Net-(R1365-Pad2)") (class "Default")
      (node (ref "R1365") (pin "2") (pinfunction "2_2") (pintype "passive"))
      (node (ref "X1361") (pin "5") (pinfunction "5_5") (pintype "passive"))
    )
    (net (code "120") (name "Net-(R1366-Pad2)") (class "Default")
      (node (ref "R1366") (pin "2") (pinfunction "2_2") (pintype "passive"))
      (node (ref "X1361") (pin "6") (pinfunction "6_6") (pintype "passive"))
    )
    (net (code "121") (name "Net-(S1321-P)") (class "Default")
      (node (ref "R1321") (pin "2") (pinfunction "2_2") (pintype "passive"))
      (node (ref "S1321") (pin "1") (pinfunction "P_1") (pintype "passive"))
    )
    (net (code "122") (name "Net-(T0551-C)") (class "Default")
      (node (ref "T0551") (pin "3") (pinfunction "C_3") (pintype "passive"))
      (node (ref "U0501") (pin "11") (pinfunction "K_BL_11") (pintype "passive"))
    )
    (net (code "123") (name "Net-(T0551-E)") (class "Default")
      (node (ref "R0553") (pin "2") (pinfunction "2_2") (pintype "passive"))
      (node (ref "T0551") (pin "2") (pinfunction "E_2") (pintype "passive"))
    )
    (net (code "124") (name "Net-(U0501-CAP1N)") (class "Default")
      (node (ref "C0511") (pin "2") (pinfunction "2_2") (pintype "passive"))
      (node (ref "U0501") (pin "2") (pinfunction "CAP1N_2") (pintype "passive"))
    )
    (net (code "125") (name "Net-(U0501-CAP1P)") (class "Default")
      (node (ref "C0511") (pin "1") (pinfunction "1_1") (pintype "passive"))
      (node (ref "U0501") (pin "3") (pinfunction "CAP1P_3") (pintype "passive"))
    )
    (net (code "126") (name "Net-(U0501-VOUT)") (class "Default")
      (node (ref "C0512") (pin "1") (pinfunction "1_1") (pintype "passive"))
      (node (ref "U0501") (pin "1") (pinfunction "VOUT_1") (pintype "passive"))
    )
    (net (code "127") (name "Net-(U0601-REF)") (class "Default")
      (node (ref "C0611") (pin "1") (pinfunction "1_1") (pintype "passive"))
      (node (ref "U0601") (pin "1") (pinfunction "REF_1") (pintype "passive"))
      (node (ref "U0651") (pin "5") (pinfunction "VOUT_5") (pintype "power_in"))
    )
    (net (code "128") (name "Net-(U0701-AVDD0)") (class "Default")
      (node (ref "C0707") (pin "2") (pinfunction "2_2") (pintype "passive"))
      (node (ref "U0701") (pin "14") (pinfunction "AVDD0_14") (pintype "passive"))
    )
    (net (code "129") (name "Net-(U0701-AVDD1)") (class "Default")
      (node (ref "C0708") (pin "2") (pinfunction "2_2") (pintype "passive"))
      (node (ref "U0701") (pin "47") (pinfunction "AVDD1_47") (pintype "passive"))
    )
    (net (code "130") (name "Net-(U0701-CLKO)") (class "Default")
      (node (ref "R0711") (pin "2") (pinfunction "2_2") (pintype "passive"))
      (node (ref "U0701") (pin "22") (pinfunction "CLKO_22") (pintype "output"))
    )
    (net (code "131") (name "Net-(U0701-DVDD)") (class "Default")
      (node (ref "C0706") (pin "2") (pinfunction "2_2") (pintype "passive"))
      (node (ref "U0701") (pin "37") (pinfunction "DVDD_37") (pintype "passive"))
    )
    (net (code "132") (name "Net-(U0701-IRQ)") (class "Default")
      (node (ref "R0756") (pin "1") (pinfunction "1_1") (pintype "passive"))
      (node (ref "U0701") (pin "40") (pinfunction "IRQ_40") (pintype "output"))
    )
    (net (code "133") (name "Net-(U0701-MISO)") (class "Default")
      (node (ref "R0754") (pin "1") (pinfunction "1_1") (pintype "passive"))
      (node (ref "U0701") (pin "44") (pinfunction "MISO_44") (pintype "output"))
    )
    (net (code "134") (name "Net-(U0701-MOSI)") (class "Default")
      (node (ref "R0753") (pin "1") (pinfunction "1_1") (pintype "passive"))
      (node (ref "U0701") (pin "43") (pinfunction "MOSI_43") (pintype "input"))
    )
    (net (code "135") (name "Net-(U0701-RSTN)") (class "Default")
      (node (ref "R0755") (pin "1") (pinfunction "1_1") (pintype "passive"))
      (node (ref "U0701") (pin "13") (pinfunction "RSTN_13") (pintype "input"))
    )
    (net (code "136") (name "Net-(U0701-SCLK)") (class "Default")
      (node (ref "R0751") (pin "1") (pinfunction "1_1") (pintype "passive"))
      (node (ref "U0701") (pin "41") (pinfunction "SCLK_41") (pintype "input"))
    )
    (net (code "137") (name "Net-(U0701-SELN)") (class "Default")
      (node (ref "R0752") (pin "1") (pinfunction "1_1") (pintype "passive"))
      (node (ref "U0701") (pin "42") (pinfunction "SELN_42") (pintype "input"))
    )
    (net (code "138") (name "Net-(U0701-TCXO)") (class "Default")
      (node (ref "C0712") (pin "2") (pinfunction "2_2") (pintype "passive"))
      (node (ref "U0701") (pin "17") (pinfunction "TCXO_17") (pintype "input"))
    )
    (net (code "139") (name "Net-(U0711-OUT)") (class "Default")
      (node (ref "C0712") (pin "1") (pinfunction "1_1") (pintype "passive"))
      (node (ref "U0711") (pin "3") (pinfunction "OUT_3") (pintype "output"))
    )
    (net (code "140") (name "Net-(U0811-RF1)") (class "Default")
      (node (ref "C0831") (pin "2") (pinfunction "2_2") (pintype "passive"))
      (node (ref "U0811") (pin "1") (pinfunction "RF1_1") (pintype "passive"))
    )
    (net (code "141") (name "Net-(U0811-RF2)") (class "Default")
      (node (ref "C0832") (pin "2") (pinfunction "2_2") (pintype "passive"))
      (node (ref "U0811") (pin "3") (pinfunction "RF2_3") (pintype "passive"))
    )
    (net (code "142") (name "Net-(U0811-RFC)") (class "Default")
      (node (ref "C0821") (pin "1") (pinfunction "1_1") (pintype "passive"))
      (node (ref "U0811") (pin "5") (pinfunction "RFC_5") (pintype "passive"))
    )
    (net (code "143") (name "Net-(U0821-IND)") (class "Default")
      (node (ref "L0821") (pin "1") (pinfunction "1_1") (pintype "passive"))
      (node (ref "U0821") (pin "10") (pinfunction "IND_10") (pintype "passive"))
    )
    (net (code "144") (name "Net-(U0821-MODE)") (class "Default")
      (node (ref "R0861") (pin "2") (pinfunction "2_2") (pintype "passive"))
      (node (ref "U0821") (pin "16") (pinfunction "MODE_16") (pintype "input"))
    )
    (net (code "145") (name "Net-(U0821-RXEN)") (class "Default")
      (node (ref "R0862") (pin "2") (pinfunction "2_2") (pintype "passive"))
      (node (ref "U0821") (pin "1") (pinfunction "RXEN_1") (pintype "input"))
    )
    (net (code "146") (name "Net-(U0821-VDD3)") (class "Default")
      (node (ref "L0853") (pin "2") (pinfunction "2_2") (pintype "passive"))
      (node (ref "U0821") (pin "7") (pinfunction "VDD3_7") (pintype "power_in"))
    )
    (net (code "147") (name "Net-(U0881-OUT)") (class "Default")
      (node (ref "C0893") (pin "1") (pinfunction "1_1") (pintype "passive"))
      (node (ref "L0892") (pin "1") (pinfunction "1_1") (pintype "passive"))
      (node (ref "U0881") (pin "5") (pinfunction "OUT_5") (pintype "passive"))
    )
    (net (code "148") (name "Net-(U0911-ACBUS3)") (class "Default")
      (node (ref "R0971") (pin "1") (pinfunction "1_1") (pintype "passive"))
      (node (ref "U0911") (pin "27") (pinfunction "ACBUS3_27") (pintype "output"))
    )
    (net (code "149") (name "Net-(U0911-ACBUS4)") (class "Default")
      (node (ref "R0972") (pin "1") (pinfunction "1_1") (pintype "passive"))
      (node (ref "U0911") (pin "28") (pinfunction "ACBUS4_28") (pintype "output"))
    )
    (net (code "150") (name "Net-(U0911-ACBUS7)") (class "Default")
      (node (ref "R0991") (pin "2") (pinfunction "2_2") (pintype "passive"))
      (node (ref "U0911") (pin "31") (pinfunction "ACBUS7_31") (pintype "tri_state"))
    )
    (net (code "151") (name "Net-(U0911-ADBUS0)") (class "Default")
      (node (ref "R0961") (pin "1") (pinfunction "1_1") (pintype "passive"))
      (node (ref "U0911") (pin "13") (pinfunction "ADBUS0_13") (pintype "output"))
    )
    (net (code "152") (name "Net-(U0911-ADBUS1)") (class "Default")
      (node (ref "R0962") (pin "1") (pinfunction "1_1") (pintype "passive"))
      (node (ref "U0911") (pin "14") (pinfunction "ADBUS1_14") (pintype "input"))
    )
    (net (code "153") (name "Net-(U0911-ADBUS2)") (class "Default")
      (node (ref "R0963") (pin "1") (pinfunction "1_1") (pintype "passive"))
      (node (ref "U0911") (pin "15") (pinfunction "ADBUS2_15") (pintype "output"))
    )
    (net (code "154") (name "Net-(U0911-ADBUS3)") (class "Default")
      (node (ref "R0964") (pin "1") (pinfunction "1_1") (pintype "passive"))
      (node (ref "U0911") (pin "16") (pinfunction "ADBUS3_16") (pintype "input"))
    )
    (net (code "155") (name "Net-(U0911-ADBUS4)") (class "Default")
      (node (ref "R0965") (pin "1") (pinfunction "1_1") (pintype "passive"))
      (node (ref "U0911") (pin "17") (pinfunction "ADBUS4_17") (pintype "output"))
    )
    (net (code "156") (name "Net-(U0911-ADBUS5)") (class "Default")
      (node (ref "R0966") (pin "1") (pinfunction "1_1") (pintype "passive"))
      (node (ref "U0911") (pin "18") (pinfunction "ADBUS5_18") (pintype "input"))
    )
    (net (code "157") (name "Net-(U0911-ADBUS6)") (class "Default")
      (node (ref "R0967") (pin "1") (pinfunction "1_1") (pintype "passive"))
      (node (ref "U0911") (pin "19") (pinfunction "ADBUS6_19") (pintype "input"))
    )
    (net (code "158") (name "Net-(U0911-ADBUS7)") (class "Default")
      (node (ref "R0968") (pin "1") (pinfunction "1_1") (pintype "passive"))
      (node (ref "U0911") (pin "20") (pinfunction "ADBUS7_20") (pintype "input"))
    )
    (net (code "159") (name "Net-(U0911-EEDATA)") (class "Default")
      (node (ref "R0931") (pin "1") (pinfunction "1_1") (pintype "passive"))
      (node (ref "U0911") (pin "43") (pinfunction "EEDATA_43") (pintype "bidirectional"))
    )
    (net (code "160") (name "Net-(U0911-OSCI)") (class "Default")
      (node (ref "R0941") (pin "2") (pinfunction "2_2") (pintype "passive"))
      (node (ref "U0911") (pin "1") (pinfunction "OSCI_1") (pintype "passive"))
    )
    (net (code "161") (name "Net-(U0911-REF)") (class "Default")
      (node (ref "R0911") (pin "2") (pinfunction "2_2") (pintype "passive"))
      (node (ref "U0911") (pin "5") (pinfunction "REF_5") (pintype "passive"))
    )
    (net (code "162") (name "Net-(U0911-VCCA)") (class "Default")
      (node (ref "C0914") (pin "2") (pinfunction "2_2") (pintype "passive"))
      (node (ref "U0911") (pin "37") (pinfunction "VCCA_37") (pintype "passive"))
    )
    (net (code "163") (name "Net-(U0911-VCCCORE)") (class "Default")
      (node (ref "C0913") (pin "2") (pinfunction "2_2") (pintype "passive"))
      (node (ref "U0911") (pin "38") (pinfunction "VCCCORE_38") (pintype "passive"))
    )
    (net (code "164") (name "Net-(U0911-VPHY)") (class "Default")
      (node (ref "C0922") (pin "2") (pinfunction "2_2") (pintype "passive"))
      (node (ref "C0924") (pin "1") (pinfunction "1_1") (pintype "passive"))
      (node (ref "L0922") (pin "1") (pinfunction "1_1") (pintype "passive"))
      (node (ref "U0911") (pin "3") (pinfunction "VPHY_3") (pintype "power_in"))
    )
    (net (code "165") (name "Net-(U0911-VPLL)") (class "Default")
      (node (ref "C0921") (pin "2") (pinfunction "2_2") (pintype "passive"))
      (node (ref "C0923") (pin "1") (pinfunction "1_1") (pintype "passive"))
      (node (ref "L0921") (pin "1") (pinfunction "1_1") (pintype "passive"))
      (node (ref "U0911") (pin "8") (pinfunction "VPLL_8") (pintype "power_in"))
    )
    (net (code "166") (name "Net-(U0911-~{RESET})") (class "Default")
      (node (ref "R0912") (pin "2") (pinfunction "2_2") (pintype "passive"))
      (node (ref "R0913") (pin "2") (pinfunction "2_2") (pintype "passive"))
      (node (ref "U0911") (pin "34") (pinfunction "~{RESET}_34") (pintype "input"))
    )
    (net (code "167") (name "Net-(U1101-EN)") (class "Default")
      (node (ref "D1161") (pin "A") (pinfunction "A_A") (pintype "passive"))
      (node (ref "R1161") (pin "1") (pinfunction "1_1") (pintype "passive"))
      (node (ref "U1101") (pin "2") (pinfunction "EN_2") (pintype "input"))
    )
    (net (code "168") (name "Net-(U1101-VBST)") (class "Default")
      (node (ref "R1108") (pin "1") (pinfunction "1_1") (pintype "passive"))
      (node (ref "U1101") (pin "4") (pinfunction "VBST_4") (pintype "passive"))
    )
    (net (code "169") (name "Net-(U1101-VFB)") (class "Default")
      (node (ref "C1132") (pin "2") (pinfunction "2_2") (pintype "passive"))
      (node (ref "R1101") (pin "2") (pinfunction "2_2") (pintype "passive"))
      (node (ref "R1102") (pin "1") (pinfunction "1_1") (pintype "passive"))
      (node (ref "U1101") (pin "1") (pinfunction "VFB_1") (pintype "passive"))
    )
    (net (code "170") (name "Net-(U1211-EN)") (class "Default")
      (node (ref "R1211") (pin "2") (pinfunction "2_2") (pintype "passive"))
      (node (ref "U1211") (pin "12") (pinfunction "EN_12") (pintype "input"))
    )
    (net (code "171") (name "Net-(U1211-SW)") (class "Default")
      (node (ref "L1211") (pin "2") (pinfunction "2_2") (pintype "passive"))
      (node (ref "U1211") (pin "2") (pinfunction "SW_2") (pintype "passive"))
    )
    (net (code "172") (name "Net-(X1311-J_VUSB)") (class "Default")
      (node (ref "PF1311") (pin "2") (pinfunction "2_2") (pintype "passive"))
      (node (ref "X1311") (pin "VBUS") (pinfunction "J_VUSB_VBUS") (pintype "power_in"))
    )
    (net (code "173") (name "RFX_DET") (class "Default")
      (node (ref "R0821") (pin "1") (pinfunction "1_1") (pintype "passive"))
      (node (ref "R0822") (pin "2") (pinfunction "2_2") (pintype "passive"))
      (node (ref "U0821") (pin "5") (pinfunction "DET_5") (pintype "output"))
    )
    (net (code "174") (name "RFX_TXEN") (class "Default")
      (node (ref "R0863") (pin "2") (pinfunction "2_2") (pintype "passive"))
      (node (ref "U0811") (pin "4") (pinfunction "CTRL_4") (pintype "input"))
      (node (ref "U0821") (pin "2") (pinfunction "TXEN_2") (pintype "input"))
    )
    (net (code "175") (name "TPS_MODE") (class "Default")
      (node (ref "R1106") (pin "2") (pinfunction "2_2") (pintype "passive"))
      (node (ref "U1101") (pin "20") (pinfunction "MODE_20") (pintype "passive"))
    )
    (net (code "176") (name "TPS_PGOOD") (class "Default")
      (node (ref "R1107") (pin "1") (pinfunction "1_1") (pintype "passive"))
      (node (ref "U1101") (pin "3") (pinfunction "PGOOD_3") (pintype "open_collector"))
    )
    (net (code "177") (name "TPS_RF") (class "Default")
      (node (ref "R1103") (pin "2") (pinfunction "2_2") (pintype "passive"))
      (node (ref "R1104") (pin "2") (pinfunction "2_2") (pintype "passive"))
      (node (ref "U1101") (pin "22") (pinfunction "RF_22") (pintype "passive"))
    )
    (net (code "178") (name "TPS_TRIP") (class "Default")
      (node (ref "R1105") (pin "2") (pinfunction "2_2") (pintype "passive"))
      (node (ref "U1101") (pin "21") (pinfunction "TRIP_21") (pintype "passive"))
    )
    (net (code "179") (name "TPS_VIN") (class "Default")
      (node (ref "C1101") (pin "2") (pinfunction "2_2") (pintype "passive"))
      (node (ref "C1111") (pin "2") (pinfunction "2_2") (pintype "passive"))
      (node (ref "C1112") (pin "2") (pinfunction "2_2") (pintype "passive"))
      (node (ref "C1113") (pin "2") (pinfunction "2_2") (pintype "passive"))
      (node (ref "C1114") (pin "2") (pinfunction "2_2") (pintype "passive"))
      (node (ref "D1111") (pin "C") (pinfunction "C_C") (pintype "passive"))
      (node (ref "D1112") (pin "C") (pinfunction "C_C") (pintype "passive"))
      (node (ref "R1161") (pin "2") (pinfunction "2_2") (pintype "passive"))
      (node (ref "U1101") (pin "12") (pinfunction "VIN_12") (pintype "power_in"))
      (node (ref "U1101") (pin "13") (pinfunction "VIN_13") (pintype "power_in"))
      (node (ref "U1101") (pin "14") (pinfunction "VIN_14") (pintype "power_in"))
      (node (ref "U1101") (pin "15") (pinfunction "VIN_15") (pintype "power_in"))
      (node (ref "U1101") (pin "16") (pinfunction "VIN_16") (pintype "power_in"))
      (node (ref "U1101") (pin "17") (pinfunction "VIN_17") (pintype "power_in"))
      (node (ref "U1101") (pin "19") (pinfunction "VDD_19") (pintype "power_in"))
    )
    (net (code "180") (name "TPS_VREG") (class "Default")
      (node (ref "C1102") (pin "2") (pinfunction "2_2") (pintype "passive"))
      (node (ref "D1161") (pin "C") (pinfunction "C_C") (pintype "passive"))
      (node (ref "R1107") (pin "2") (pinfunction "2_2") (pintype "passive"))
      (node (ref "U1101") (pin "18") (pinfunction "VREG_18") (pintype "power_in"))
    )
    (net (code "181") (name "TRX_CLK_26MHZ") (class "Default")
      (node (ref "C0713") (pin "2") (pinfunction "2_2") (pintype "passive"))
      (node (ref "JB2") (pin "52") (pinfunction "B15_L11_CLK_P_52") (pintype "passive"))
      (node (ref "R0711") (pin "1") (pinfunction "1_1") (pintype "passive"))
    )
    (net (code "182") (name "TRX_FEA09") (class "Default")
      (node (ref "R0863") (pin "1") (pinfunction "1_1") (pintype "passive"))
      (node (ref "U0701") (pin "11") (pinfunction "FEA09_11") (pintype "output"))
    )
    (net (code "183") (name "TRX_FEA24") (class "Default")
      (node (ref "U0701") (pin "1") (pinfunction "FEA24_1") (pintype "output"))
    )
    (net (code "184") (name "TRX_FEB09") (class "Default")
      (node (ref "R0862") (pin "1") (pinfunction "1_1") (pintype "passive"))
      (node (ref "U0701") (pin "12") (pinfunction "FEB09_12") (pintype "output"))
    )
    (net (code "185") (name "TRX_FEB24") (class "Default")
      (node (ref "U0701") (pin "2") (pinfunction "FEB24_2") (pintype "output"))
    )
    (net (code "186") (name "TRX_IRQ") (class "Default")
      (node (ref "JB2") (pin "68") (pinfunction "B15_L16_N_68") (pintype "passive"))
      (node (ref "R0756") (pin "2") (pinfunction "2_2") (pintype "passive"))
    )
    (net (code "187") (name "TRX_MISO") (class "Default")
      (node (ref "JB2") (pin "78") (pinfunction "B15_L2_P_78") (pintype "passive"))
      (node (ref "R0754") (pin "2") (pinfunction "2_2") (pintype "passive"))
    )
    (net (code "188") (name "TRX_MOSI") (class "Default")
      (node (ref "JB2") (pin "76") (pinfunction "B15_L2_N_76") (pintype "passive"))
      (node (ref "R0753") (pin "2") (pinfunction "2_2") (pintype "passive"))
    )
    (net (code "189") (name "TRX_RF09") (class "Default")
      (node (ref "C0821") (pin "2") (pinfunction "2_2") (pintype "passive"))
      (node (ref "L0721") (pin "4") (pinfunction "UB_4") (pintype "passive"))
    )
    (net (code "190") (name "TRX_RF24") (class "Default")
      (node (ref "C0897") (pin "1") (pinfunction "1_1") (pintype "passive"))
      (node (ref "L0722") (pin "1") (pinfunction "UB_1") (pintype "passive"))
      (node (ref "L0896") (pin "1") (pinfunction "1_1") (pintype "passive"))
    )
    (net (code "191") (name "TRX_RSTN") (class "Default")
      (node (ref "JB2") (pin "66") (pinfunction "B15_L16_P_66") (pintype "passive"))
      (node (ref "R0755") (pin "2") (pinfunction "2_2") (pintype "passive"))
    )
    (net (code "192") (name "TRX_RXCLK_N") (class "Default")
      (node (ref "JB1") (pin "22") (pinfunction "B13_L11_N_22") (pintype "passive"))
      (node (ref "U0701") (pin "33") (pinfunction "RXCLKN_33") (pintype "output"))
    )
    (net (code "193") (name "TRX_RXCLK_P") (class "Default")
      (node (ref "JB1") (pin "24") (pinfunction "B13_L11_P_24") (pintype "passive"))
      (node (ref "U0701") (pin "34") (pinfunction "RXCLKP_34") (pintype "output"))
    )
    (net (code "194") (name "TRX_RXD09_N") (class "Default")
      (node (ref "JB1") (pin "20") (pinfunction "B13_L3_N_20") (pintype "passive"))
      (node (ref "U0701") (pin "30") (pinfunction "RXD09N_30") (pintype "output"))
    )
    (net (code "195") (name "TRX_RXD09_P") (class "Default")
      (node (ref "JB1") (pin "18") (pinfunction "B13_L3_P_18") (pintype "passive"))
      (node (ref "U0701") (pin "31") (pinfunction "RXD09P_31") (pintype "output"))
    )
    (net (code "196") (name "TRX_RXD24_N") (class "Default")
      (node (ref "JB1") (pin "26") (pinfunction "B13_L9_N_26") (pintype "passive"))
      (node (ref "U0701") (pin "35") (pinfunction "RXD24N_35") (pintype "output"))
    )
    (net (code "197") (name "TRX_RXD24_P") (class "Default")
      (node (ref "JB1") (pin "28") (pinfunction "B13_L9_P_28") (pintype "passive"))
      (node (ref "U0701") (pin "36") (pinfunction "RXD24P_36") (pintype "output"))
    )
    (net (code "198") (name "TRX_SCLK") (class "Default")
      (node (ref "JB2") (pin "72") (pinfunction "B15_L1_P_72") (pintype "passive"))
      (node (ref "R0751") (pin "2") (pinfunction "2_2") (pintype "passive"))
    )
    (net (code "199") (name "TRX_SELN") (class "Default")
      (node (ref "JB2") (pin "74") (pinfunction "B15_L1_N_74") (pintype "passive"))
      (node (ref "R0752") (pin "2") (pinfunction "2_2") (pintype "passive"))
    )
    (net (code "200") (name "TRX_TXCLK_N") (class "Default")
      (node (ref "JB1") (pin "15") (pinfunction "B13_L6_N_15") (pintype "passive"))
      (node (ref "U0701") (pin "25") (pinfunction "TXCLKN_25") (pintype "input"))
    )
    (net (code "201") (name "TRX_TXCLK_P") (class "Default")
      (node (ref "JB1") (pin "17") (pinfunction "B13_L6_P_17") (pintype "passive"))
      (node (ref "U0701") (pin "26") (pinfunction "TXCLKP_26") (pintype "input"))
    )
    (net (code "202") (name "TRX_TXD_N") (class "Default")
      (node (ref "JB1") (pin "21") (pinfunction "B13_L5_N_21") (pintype "passive"))
      (node (ref "U0701") (pin "27") (pinfunction "TXDN_27") (pintype "input"))
    )
    (net (code "203") (name "TRX_TXD_P") (class "Default")
      (node (ref "JB1") (pin "23") (pinfunction "B13_L5_P_23") (pintype "passive"))
      (node (ref "U0701") (pin "28") (pinfunction "TXDP_28") (pintype "input"))
    )
    (net (code "204") (name "TRX_TXD_VOID_N") (class "Default")
      (node (ref "JB3") (pin "49") (pinfunction "B13_L4_N_49") (pintype "passive"))
    )
    (net (code "205") (name "TRX_TXD_VOID_P") (class "Default")
      (node (ref "JB3") (pin "47") (pinfunction "B13_L4_P_47") (pintype "passive"))
    )
    (net (code "206") (name "U1V5") (class "Default")
      (node (ref "JB2") (pin "20") (pinfunction "U1V5_20") (pintype "power_in"))
    )
    (net (code "207") (name "U1V8") (class "Default")
      (node (ref "JB1") (pin "40") (pinfunction "U1V8_40") (pintype "power_in"))
      (node (ref "R0202") (pin "1") (pinfunction "1_1") (pintype "passive"))
      (node (ref "R1383") (pin "2") (pinfunction "2_2") (pintype "passive"))
    )
    (net (code "208") (name "U3V3") (class "Default")
      (node (ref "JB1") (pin "13") (pinfunction "U3V3_13") (pintype "power_in"))
      (node (ref "JB2") (pin "10") (pinfunction "VCCIO15_10") (pintype "power_in"))
      (node (ref "JB2") (pin "11") (pinfunction "U3V3_11") (pintype "power_in"))
      (node (ref "JB2") (pin "8") (pinfunction "VCCIO15_8") (pintype "power_in"))
      (node (ref "JB2") (pin "9") (pinfunction "U3V3_9") (pintype "power_in"))
      (node (ref "R1211") (pin "1") (pinfunction "1_1") (pintype "passive"))
      (node (ref "R1381") (pin "2") (pinfunction "2_2") (pintype "passive"))
    )
    (net (code "209") (name "U3V3_JTAGREF") (class "Default")
      (node (ref "JB2") (pin "92") (pinfunction "U3V3_JTAGREF_92") (pintype "power_in"))
      (node (ref "R1331") (pin "2") (pinfunction "2_2") (pintype "passive"))
    )
    (net (code "210") (name "USB_D_N") (class "Default")
      (node (ref "U0911") (pin "6") (pinfunction "D_M_6") (pintype "passive"))
      (node (ref "X1311") (pin "D-") (pinfunction "J_D-_D-") (pintype "bidirectional"))
    )
    (net (code "211") (name "USB_D_P") (class "Default")
      (node (ref "U0911") (pin "7") (pinfunction "D_P_7") (pintype "passive"))
      (node (ref "X1311") (pin "D+") (pinfunction "J_D+_D+") (pintype "bidirectional"))
    )
    (net (code "212") (name "USB_ID") (class "Default")
      (node (ref "X1311") (pin "ID") (pinfunction "J_ID_ID") (pintype "bidirectional"))
    )
    (net (code "213") (name "VBAT_IN") (class "Default")
      (node (ref "JB1") (pin "80") (pinfunction "VBAT_IN_80") (pintype "power_in"))
    )
    (net (code "214") (name "VCCIO13") (class "Default")
      (node (ref "JB2") (pin "2") (pinfunction "VCCIO13_2") (pintype "power_in"))
      (node (ref "JB2") (pin "4") (pinfunction "VCCIO13_4") (pintype "power_in"))
      (node (ref "R0201") (pin "2") (pinfunction "2_2") (pintype "passive"))
      (node (ref "R0202") (pin "2") (pinfunction "2_2") (pintype "passive"))
      (node (ref "S1321") (pin "2") (pinfunction "S_2") (pintype "passive"))
    )
    (net (code "215") (name "VCCIO16") (class "Default")
      (node (ref "C1381") (pin "2") (pinfunction "2_2") (pintype "passive"))
      (node (ref "JB1") (pin "10") (pinfunction "VCCIO16_10") (pintype "power_in"))
      (node (ref "JB1") (pin "12") (pinfunction "VCCIO16_12") (pintype "power_in"))
      (node (ref "R1381") (pin "1") (pinfunction "1_1") (pintype "passive"))
      (node (ref "R1382") (pin "1") (pinfunction "1_1") (pintype "passive"))
      (node (ref "R1383") (pin "1") (pinfunction "1_1") (pintype "passive"))
    )
    (net (code "216") (name "VCTCXO_VC") (class "Default")
      (node (ref "C0621") (pin "1") (pinfunction "1_1") (pintype "passive"))
      (node (ref "R0621") (pin "2") (pinfunction "2_2") (pintype "passive"))
      (node (ref "U0711") (pin "1") (pinfunction "VC_1") (pintype "input"))
    )
    (net (code "217") (name "VIN_PWR") (class "Default")
      (node (ref "D1111") (pin "A") (pinfunction "A_A") (pintype "passive"))
      (node (ref "X1361") (pin "7") (pinfunction "7_7") (pintype "passive"))
    )
    (net (code "218") (name "unconnected-(J1411-Pad9)") (class "Default")
      (node (ref "J1411") (pin "9") (pinfunction "9_9") (pintype "no_connect"))
    )
    (net (code "219") (name "unconnected-(JB1-B14_L18_MIO_P-Pad88)") (class "Default")
      (node (ref "JB1") (pin "88") (pinfunction "B14_L18_MIO_P_88") (pintype "passive"))
    )
    (net (code "220") (name "unconnected-(JB1-B16_L1_N-Pad97)") (class "Default")
      (node (ref "JB1") (pin "97") (pinfunction "B16_L1_N_97") (pintype "passive"))
    )
    (net (code "221") (name "unconnected-(JB1-B16_L1_P-Pad99)") (class "Default")
      (node (ref "JB1") (pin "99") (pinfunction "B16_L1_P_99") (pintype "passive"))
    )
    (net (code "222") (name "unconnected-(JB1-B16_L3_N-Pad70)") (class "Default")
      (node (ref "JB1") (pin "70") (pinfunction "B16_L3_N_70") (pintype "passive"))
    )
    (net (code "223") (name "unconnected-(JB1-B16_L3_P-Pad72)") (class "Default")
      (node (ref "JB1") (pin "72") (pinfunction "B16_L3_P_72") (pintype "passive"))
    )
    (net (code "224") (name "unconnected-(JB1-B16_L4_N-Pad93)") (class "Default")
      (node (ref "JB1") (pin "93") (pinfunction "B16_L4_N_93") (pintype "passive"))
    )
    (net (code "225") (name "unconnected-(JB1-B16_L4_P-Pad95)") (class "Default")
      (node (ref "JB1") (pin "95") (pinfunction "B16_L4_P_95") (pintype "passive"))
    )
    (net (code "226") (name "unconnected-(JB1-B16_L12_CLK_N-Pad78)") (class "Default")
      (node (ref "JB1") (pin "78") (pinfunction "B16_L12_CLK_N_78") (pintype "passive"))
    )
    (net (code "227") (name "unconnected-(JB1-B16_L12_CLK_P-Pad76)") (class "Default")
      (node (ref "JB1") (pin "76") (pinfunction "B16_L12_CLK_P_76") (pintype "passive"))
    )
    (net (code "228") (name "unconnected-(JB1-B16_L13_CLK_N-Pad62)") (class "Default")
      (node (ref "JB1") (pin "62") (pinfunction "B16_L13_CLK_N_62") (pintype "passive"))
    )
    (net (code "229") (name "unconnected-(JB1-B16_L13_CLK_P-Pad60)") (class "Default")
      (node (ref "JB1") (pin "60") (pinfunction "B16_L13_CLK_P_60") (pintype "passive"))
    )
    (net (code "230") (name "unconnected-(JB1-B16_L14_N-Pad68)") (class "Default")
      (node (ref "JB1") (pin "68") (pinfunction "B16_L14_N_68") (pintype "passive"))
    )
    (net (code "231") (name "unconnected-(JB1-B16_L14_P-Pad66)") (class "Default")
      (node (ref "JB1") (pin "66") (pinfunction "B16_L14_P_66") (pintype "passive"))
    )
    (net (code "232") (name "unconnected-(JB1-B16_L15_N-Pad48)") (class "Default")
      (node (ref "JB1") (pin "48") (pinfunction "B16_L15_N_48") (pintype "passive"))
    )
    (net (code "233") (name "unconnected-(JB1-B16_L15_P-Pad46)") (class "Default")
      (node (ref "JB1") (pin "46") (pinfunction "B16_L15_P_46") (pintype "passive"))
    )
    (net (code "234") (name "unconnected-(JB1-B16_L20_N-Pad52)") (class "Default")
      (node (ref "JB1") (pin "52") (pinfunction "B16_L20_N_52") (pintype "passive"))
    )
    (net (code "235") (name "unconnected-(JB1-B16_L20_P-Pad50)") (class "Default")
      (node (ref "JB1") (pin "50") (pinfunction "B16_L20_P_50") (pintype "passive"))
    )
    (net (code "236") (name "unconnected-(JB1-B16_L21_N-Pad58)") (class "Default")
      (node (ref "JB1") (pin "58") (pinfunction "B16_L21_N_58") (pintype "passive"))
    )
    (net (code "237") (name "unconnected-(JB1-B16_L21_P-Pad56)") (class "Default")
      (node (ref "JB1") (pin "56") (pinfunction "B16_L21_P_56") (pintype "passive"))
    )
    (net (code "238") (name "unconnected-(JB1-B16_L22_N-Pad34)") (class "Default")
      (node (ref "JB1") (pin "34") (pinfunction "B16_L22_N_34") (pintype "passive"))
    )
    (net (code "239") (name "unconnected-(JB1-B16_L22_P-Pad32)") (class "Default")
      (node (ref "JB1") (pin "32") (pinfunction "B16_L22_P_32") (pintype "passive"))
    )
    (net (code "240") (name "unconnected-(JB1-B16_L23_N-Pad44)") (class "Default")
      (node (ref "JB1") (pin "44") (pinfunction "B16_L23_N_44") (pintype "passive"))
    )
    (net (code "241") (name "unconnected-(JB1-B16_L23_P-Pad42)") (class "Default")
      (node (ref "JB1") (pin "42") (pinfunction "B16_L23_P_42") (pintype "passive"))
    )
    (net (code "242") (name "unconnected-(JB1-B16_L24_N-Pad36)") (class "Default")
      (node (ref "JB1") (pin "36") (pinfunction "B16_L24_N_36") (pintype "passive"))
    )
    (net (code "243") (name "unconnected-(JB1-B16_L24_P-Pad38)") (class "Default")
      (node (ref "JB1") (pin "38") (pinfunction "B16_L24_P_38") (pintype "passive"))
    )
    (net (code "244") (name "unconnected-(JB1-NOSEQ-Pad8)") (class "Default")
      (node (ref "JB1") (pin "8") (pinfunction "NOSEQ_8") (pintype "passive"))
    )
    (net (code "245") (name "unconnected-(JB2-B14_L8_N-Pad12)") (class "Default")
      (node (ref "JB2") (pin "12") (pinfunction "B14_L8_N_12") (pintype "passive"))
    )
    (net (code "246") (name "unconnected-(JB2-B14_L10_N-Pad13)") (class "Default")
      (node (ref "JB2") (pin "13") (pinfunction "B14_L10_N_13") (pintype "passive"))
    )
    (net (code "247") (name "unconnected-(JB2-B14_L10_P-Pad15)") (class "Default")
      (node (ref "JB2") (pin "15") (pinfunction "B14_L10_P_15") (pintype "passive"))
    )
    (net (code "248") (name "unconnected-(JB2-B14_L11_N-Pad27)") (class "Default")
      (node (ref "JB2") (pin "27") (pinfunction "B14_L11_N_27") (pintype "passive"))
    )
    (net (code "249") (name "unconnected-(JB2-B14_L11_P-Pad25)") (class "Default")
      (node (ref "JB2") (pin "25") (pinfunction "B14_L11_P_25") (pintype "passive"))
    )
    (net (code "250") (name "unconnected-(JB2-B14_L12_N-Pad23)") (class "Default")
      (node (ref "JB2") (pin "23") (pinfunction "B14_L12_N_23") (pintype "passive"))
    )
    (net (code "251") (name "unconnected-(JB2-B14_L12_P-Pad21)") (class "Default")
      (node (ref "JB2") (pin "21") (pinfunction "B14_L12_P_21") (pintype "passive"))
    )
    (net (code "252") (name "unconnected-(JB2-B14_L13_CLK_N-Pad28)") (class "Default")
      (node (ref "JB2") (pin "28") (pinfunction "B14_L13_CLK_N_28") (pintype "passive"))
    )
    (net (code "253") (name "unconnected-(JB2-B14_L15_N-Pad38)") (class "Default")
      (node (ref "JB2") (pin "38") (pinfunction "B14_L15_N_38") (pintype "passive"))
    )
    (net (code "254") (name "unconnected-(JB2-B14_L15_P-Pad36)") (class "Default")
      (node (ref "JB2") (pin "36") (pinfunction "B14_L15_P_36") (pintype "passive"))
    )
    (net (code "255") (name "unconnected-(JB2-B14_L16_N-Pad34)") (class "Default")
      (node (ref "JB2") (pin "34") (pinfunction "B14_L16_N_34") (pintype "passive"))
    )
    (net (code "256") (name "unconnected-(JB2-B14_L16_P-Pad32)") (class "Default")
      (node (ref "JB2") (pin "32") (pinfunction "B14_L16_P_32") (pintype "passive"))
    )
    (net (code "257") (name "unconnected-(JB2-B15_L3_N-Pad58)") (class "Default")
      (node (ref "JB2") (pin "58") (pinfunction "B15_L3_N_58") (pintype "passive"))
    )
    (net (code "258") (name "unconnected-(JB2-B15_L3_P-Pad56)") (class "Default")
      (node (ref "JB2") (pin "56") (pinfunction "B15_L3_P_56") (pintype "passive"))
    )
    (net (code "259") (name "unconnected-(JB2-B15_L4_N-Pad84)") (class "Default")
      (node (ref "JB2") (pin "84") (pinfunction "B15_L4_N_84") (pintype "passive"))
    )
    (net (code "260") (name "unconnected-(JB2-B15_L4_P-Pad82)") (class "Default")
      (node (ref "JB2") (pin "82") (pinfunction "B15_L4_P_82") (pintype "passive"))
    )
    (net (code "261") (name "unconnected-(JB2-B15_L5_N-Pad86)") (class "Default")
      (node (ref "JB2") (pin "86") (pinfunction "B15_L5_N_86") (pintype "passive"))
    )
    (net (code "262") (name "unconnected-(JB2-B15_L5_P-Pad88)") (class "Default")
      (node (ref "JB2") (pin "88") (pinfunction "B15_L5_P_88") (pintype "passive"))
    )
    (net (code "263") (name "unconnected-(JB2-B15_L6_N-Pad81)") (class "Default")
      (node (ref "JB2") (pin "81") (pinfunction "B15_L6_N_81") (pintype "passive"))
    )
    (net (code "264") (name "unconnected-(JB2-B15_L6_P-Pad83)") (class "Default")
      (node (ref "JB2") (pin "83") (pinfunction "B15_L6_P_83") (pintype "passive"))
    )
    (net (code "265") (name "unconnected-(JB2-B15_L7_N-Pad41)") (class "Default")
      (node (ref "JB2") (pin "41") (pinfunction "B15_L7_N_41") (pintype "passive"))
    )
    (net (code "266") (name "unconnected-(JB2-B15_L7_P-Pad43)") (class "Default")
      (node (ref "JB2") (pin "43") (pinfunction "B15_L7_P_43") (pintype "passive"))
    )
    (net (code "267") (name "unconnected-(JB2-B15_L8_N-Pad35)") (class "Default")
      (node (ref "JB2") (pin "35") (pinfunction "B15_L8_N_35") (pintype "passive"))
    )
    (net (code "268") (name "unconnected-(JB2-B15_L8_P-Pad37)") (class "Default")
      (node (ref "JB2") (pin "37") (pinfunction "B15_L8_P_37") (pintype "passive"))
    )
    (net (code "269") (name "unconnected-(JB2-B15_L9_N-Pad31)") (class "Default")
      (node (ref "JB2") (pin "31") (pinfunction "B15_L9_N_31") (pintype "passive"))
    )
    (net (code "270") (name "unconnected-(JB2-B15_L9_P-Pad33)") (class "Default")
      (node (ref "JB2") (pin "33") (pinfunction "B15_L9_P_33") (pintype "passive"))
    )
    (net (code "271") (name "unconnected-(JB2-B15_L10_N-Pad61)") (class "Default")
      (node (ref "JB2") (pin "61") (pinfunction "B15_L10_N_61") (pintype "passive"))
    )
    (net (code "272") (name "unconnected-(JB2-B15_L10_P-Pad63)") (class "Default")
      (node (ref "JB2") (pin "63") (pinfunction "B15_L10_P_63") (pintype "passive"))
    )
    (net (code "273") (name "unconnected-(JB2-B15_L11_CLK_N-Pad54)") (class "Default")
      (node (ref "JB2") (pin "54") (pinfunction "B15_L11_CLK_N_54") (pintype "passive"))
    )
    (net (code "274") (name "unconnected-(JB2-B15_L12_CLK_N-Pad57)") (class "Default")
      (node (ref "JB2") (pin "57") (pinfunction "B15_L12_CLK_N_57") (pintype "passive"))
    )
    (net (code "275") (name "unconnected-(JB2-B15_L12_CLK_P-Pad55)") (class "Default")
      (node (ref "JB2") (pin "55") (pinfunction "B15_L12_CLK_P_55") (pintype "passive"))
    )
    (net (code "276") (name "unconnected-(JB2-B15_L13_CLK_N-Pad47)") (class "Default")
      (node (ref "JB2") (pin "47") (pinfunction "B15_L13_CLK_N_47") (pintype "passive"))
    )
    (net (code "277") (name "unconnected-(JB2-B15_L13_CLK_P-Pad45)") (class "Default")
      (node (ref "JB2") (pin "45") (pinfunction "B15_L13_CLK_P_45") (pintype "passive"))
    )
    (net (code "278") (name "unconnected-(JB2-B15_L14_CLK_N-Pad53)") (class "Default")
      (node (ref "JB2") (pin "53") (pinfunction "B15_L14_CLK_N_53") (pintype "passive"))
    )
    (net (code "279") (name "unconnected-(JB2-B15_L14_CLK_P-Pad51)") (class "Default")
      (node (ref "JB2") (pin "51") (pinfunction "B15_L14_CLK_P_51") (pintype "passive"))
    )
    (net (code "280") (name "unconnected-(JB2-B15_L17_N-Pad62)") (class "Default")
      (node (ref "JB2") (pin "62") (pinfunction "B15_L17_N_62") (pintype "passive"))
    )
    (net (code "281") (name "unconnected-(JB2-B15_L17_P-Pad64)") (class "Default")
      (node (ref "JB2") (pin "64") (pinfunction "B15_L17_P_64") (pintype "passive"))
    )
    (net (code "282") (name "unconnected-(JB2-B15_L18_N-Pad67)") (class "Default")
      (node (ref "JB2") (pin "67") (pinfunction "B15_L18_N_67") (pintype "passive"))
    )
    (net (code "283") (name "unconnected-(JB2-B15_L18_P-Pad65)") (class "Default")
      (node (ref "JB2") (pin "65") (pinfunction "B15_L18_P_65") (pintype "passive"))
    )
    (net (code "284") (name "unconnected-(JB2-B15_L19_N-Pad48)") (class "Default")
      (node (ref "JB2") (pin "48") (pinfunction "B15_L19_N_48") (pintype "passive"))
    )
    (net (code "285") (name "unconnected-(JB2-B15_L19_P-Pad46)") (class "Default")
      (node (ref "JB2") (pin "46") (pinfunction "B15_L19_P_46") (pintype "passive"))
    )
    (net (code "286") (name "unconnected-(JB2-B15_L20_N-Pad73)") (class "Default")
      (node (ref "JB2") (pin "73") (pinfunction "B15_L20_N_73") (pintype "passive"))
    )
    (net (code "287") (name "unconnected-(JB2-B15_L20_P-Pad71)") (class "Default")
      (node (ref "JB2") (pin "71") (pinfunction "B15_L20_P_71") (pintype "passive"))
    )
    (net (code "288") (name "unconnected-(JB2-B15_L23_N-Pad44)") (class "Default")
      (node (ref "JB2") (pin "44") (pinfunction "B15_L23_N_44") (pintype "passive"))
    )
    (net (code "289") (name "unconnected-(JB2-B15_L23_P-Pad42)") (class "Default")
      (node (ref "JB2") (pin "42") (pinfunction "B15_L23_P_42") (pintype "passive"))
    )
    (net (code "290") (name "unconnected-(JB2-NC-Pad6)") (class "Default")
      (node (ref "JB2") (pin "6") (pinfunction "NC_6") (pintype "no_connect"))
    )
    (net (code "291") (name "unconnected-(JB2-NC-Pad30)") (class "Default")
      (node (ref "JB2") (pin "30") (pinfunction "NC_30") (pintype "no_connect"))
    )
    (net (code "292") (name "unconnected-(JB3-B13_L1_P-Pad41)") (class "Default")
      (node (ref "JB3") (pin "41") (pinfunction "B13_L1_P_41") (pintype "passive"))
    )
    (net (code "293") (name "unconnected-(JB3-B13_L2_N-Pad51)") (class "Default")
      (node (ref "JB3") (pin "51") (pinfunction "B13_L2_N_51") (pintype "passive"))
    )
    (net (code "294") (name "unconnected-(JB3-B13_L2_P-Pad53)") (class "Default")
      (node (ref "JB3") (pin "53") (pinfunction "B13_L2_P_53") (pintype "passive"))
    )
    (net (code "295") (name "unconnected-(JB3-B13_L10_N-Pad40)") (class "Default")
      (node (ref "JB3") (pin "40") (pinfunction "B13_L10_N_40") (pintype "passive"))
    )
    (net (code "296") (name "unconnected-(JB3-B13_L10_P-Pad38)") (class "Default")
      (node (ref "JB3") (pin "38") (pinfunction "B13_L10_P_38") (pintype "passive"))
    )
    (net (code "297") (name "unconnected-(JB3-B13_L12_CLK_N-Pad59)") (class "Default")
      (node (ref "JB3") (pin "59") (pinfunction "B13_L12_CLK_N_59") (pintype "passive"))
    )
    (net (code "298") (name "unconnected-(JB3-B13_L12_CLK_P-Pad57)") (class "Default")
      (node (ref "JB3") (pin "57") (pinfunction "B13_L12_CLK_P_57") (pintype "passive"))
    )
    (net (code "299") (name "unconnected-(JB3-B13_L13_N-Pad60)") (class "Default")
      (node (ref "JB3") (pin "60") (pinfunction "B13_L13_N_60") (pintype "passive"))
    )
    (net (code "300") (name "unconnected-(JB3-B13_L13_P-Pad58)") (class "Default")
      (node (ref "JB3") (pin "58") (pinfunction "B13_L13_P_58") (pintype "passive"))
    )
    (net (code "301") (name "unconnected-(JB3-B13_L14_N-Pad3)") (class "Default")
      (node (ref "JB3") (pin "3") (pinfunction "B13_L14_N_3") (pintype "passive"))
    )
    (net (code "302") (name "unconnected-(JB3-B13_L14_P-Pad1)") (class "Default")
      (node (ref "JB3") (pin "1") (pinfunction "B13_L14_P_1") (pintype "passive"))
    )
    (net (code "303") (name "unconnected-(JB3-B13_L15_N-Pad44)") (class "Default")
      (node (ref "JB3") (pin "44") (pinfunction "B13_L15_N_44") (pintype "passive"))
    )
    (net (code "304") (name "unconnected-(JB3-B13_L15_P-Pad42)") (class "Default")
      (node (ref "JB3") (pin "42") (pinfunction "B13_L15_P_42") (pintype "passive"))
    )
    (net (code "305") (name "unconnected-(JB3-B13_L17_N-Pad4)") (class "Default")
      (node (ref "JB3") (pin "4") (pinfunction "B13_L17_N_4") (pintype "passive"))
    )
    (net (code "306") (name "unconnected-(JB3-B13_L17_P-Pad2)") (class "Default")
      (node (ref "JB3") (pin "2") (pinfunction "B13_L17_P_2") (pintype "passive"))
    )
    (net (code "307") (name "unconnected-(JB3-B14_L5_N-Pad50)") (class "Default")
      (node (ref "JB3") (pin "50") (pinfunction "B14_L5_N_50") (pintype "passive"))
    )
    (net (code "308") (name "unconnected-(JB3-B14_L5_P-Pad48)") (class "Default")
      (node (ref "JB3") (pin "48") (pinfunction "B14_L5_P_48") (pintype "passive"))
    )
    (net (code "309") (name "unconnected-(JB3-B14_L20_N-Pad54)") (class "Default")
      (node (ref "JB3") (pin "54") (pinfunction "B14_L20_N_54") (pintype "passive"))
    )
    (net (code "310") (name "unconnected-(JB3-B14_L20_P-Pad52)") (class "Default")
      (node (ref "JB3") (pin "52") (pinfunction "B14_L20_P_52") (pintype "passive"))
    )
    (net (code "311") (name "unconnected-(JB3-DC-Pad55)") (class "Default")
      (node (ref "JB3") (pin "55") (pinfunction "DC_55") (pintype "no_connect"))
    )
    (net (code "312") (name "unconnected-(JB3-DC-Pad56)") (class "Default")
      (node (ref "JB3") (pin "56") (pinfunction "DC_56") (pintype "no_connect"))
    )
    (net (code "313") (name "unconnected-(JB3-GND-Pad12)") (class "Default")
      (node (ref "JB3") (pin "12") (pinfunction "GND_12") (pintype "passive"))
    )
    (net (code "314") (name "unconnected-(JB3-MGT_CLK1_CLK_N-Pad32)") (class "Default")
      (node (ref "JB3") (pin "32") (pinfunction "MGT_CLK1_CLK_N_32") (pintype "passive"))
    )
    (net (code "315") (name "unconnected-(JB3-MGT_CLK1_CLK_P-Pad34)") (class "Default")
      (node (ref "JB3") (pin "34") (pinfunction "MGT_CLK1_CLK_P_34") (pintype "passive"))
    )
    (net (code "316") (name "unconnected-(JB3-MGT_RX0_N-Pad7)") (class "Default")
      (node (ref "JB3") (pin "7") (pinfunction "MGT_RX0_N_7") (pintype "passive"))
    )
    (net (code "317") (name "unconnected-(JB3-MGT_RX0_P-Pad9)") (class "Default")
      (node (ref "JB3") (pin "9") (pinfunction "MGT_RX0_P_9") (pintype "passive"))
    )
    (net (code "318") (name "unconnected-(JB3-MGT_RX1_N-Pad13)") (class "Default")
      (node (ref "JB3") (pin "13") (pinfunction "MGT_RX1_N_13") (pintype "passive"))
    )
    (net (code "319") (name "unconnected-(JB3-MGT_RX1_P-Pad15)") (class "Default")
      (node (ref "JB3") (pin "15") (pinfunction "MGT_RX1_P_15") (pintype "passive"))
    )
    (net (code "320") (name "unconnected-(JB3-MGT_RX2_N-Pad19)") (class "Default")
      (node (ref "JB3") (pin "19") (pinfunction "MGT_RX2_N_19") (pintype "passive"))
    )
    (net (code "321") (name "unconnected-(JB3-MGT_RX2_P-Pad21)") (class "Default")
      (node (ref "JB3") (pin "21") (pinfunction "MGT_RX2_P_21") (pintype "passive"))
    )
    (net (code "322") (name "unconnected-(JB3-MGT_RX3_N-Pad25)") (class "Default")
      (node (ref "JB3") (pin "25") (pinfunction "MGT_RX3_N_25") (pintype "passive"))
    )
    (net (code "323") (name "unconnected-(JB3-MGT_RX3_P-Pad27)") (class "Default")
      (node (ref "JB3") (pin "27") (pinfunction "MGT_RX3_P_27") (pintype "passive"))
    )
    (net (code "324") (name "unconnected-(JB3-MGT_TX0_N-Pad8)") (class "Default")
      (node (ref "JB3") (pin "8") (pinfunction "MGT_TX0_N_8") (pintype "passive"))
    )
    (net (code "325") (name "unconnected-(JB3-MGT_TX0_P-Pad10)") (class "Default")
      (node (ref "JB3") (pin "10") (pinfunction "MGT_TX0_P_10") (pintype "passive"))
    )
    (net (code "326") (name "unconnected-(JB3-MGT_TX1_N-Pad14)") (class "Default")
      (node (ref "JB3") (pin "14") (pinfunction "MGT_TX1_N_14") (pintype "passive"))
    )
    (net (code "327") (name "unconnected-(JB3-MGT_TX1_P-Pad16)") (class "Default")
      (node (ref "JB3") (pin "16") (pinfunction "MGT_TX1_P_16") (pintype "passive"))
    )
    (net (code "328") (name "unconnected-(JB3-MGT_TX2_N-Pad20)") (class "Default")
      (node (ref "JB3") (pin "20") (pinfunction "MGT_TX2_N_20") (pintype "passive"))
    )
    (net (code "329") (name "unconnected-(JB3-MGT_TX2_P-Pad22)") (class "Default")
      (node (ref "JB3") (pin "22") (pinfunction "MGT_TX2_P_22") (pintype "passive"))
    )
    (net (code "330") (name "unconnected-(JB3-MGT_TX3_N-Pad26)") (class "Default")
      (node (ref "JB3") (pin "26") (pinfunction "MGT_TX3_N_26") (pintype "passive"))
    )
    (net (code "331") (name "unconnected-(JB3-MGT_TX3_P-Pad28)") (class "Default")
      (node (ref "JB3") (pin "28") (pinfunction "MGT_TX3_P_28") (pintype "passive"))
    )
    (net (code "332") (name "unconnected-(U0651-REF-Pad1)") (class "Default")
      (node (ref "U0651") (pin "1") (pinfunction "REF_1") (pintype "passive"))
    )
    (net (code "333") (name "unconnected-(U0821-DC-Pad6)") (class "Default")
      (node (ref "U0821") (pin "6") (pinfunction "DC_6") (pintype "no_connect"))
    )
    (net (code "334") (name "unconnected-(U0821-DC-Pad11)") (class "Default")
      (node (ref "U0821") (pin "11") (pinfunction "DC_11") (pintype "no_connect"))
    )
    (net (code "335") (name "unconnected-(U0821-DC-Pad12)") (class "Default")
      (node (ref "U0821") (pin "12") (pinfunction "DC_12") (pintype "no_connect"))
    )
    (net (code "336") (name "unconnected-(U0911-ACBUS1-Pad25)") (class "Default")
      (node (ref "U0911") (pin "25") (pinfunction "ACBUS1_25") (pintype "tri_state"))
    )
    (net (code "337") (name "unconnected-(U0911-ACBUS2-Pad26)") (class "Default")
      (node (ref "U0911") (pin "26") (pinfunction "ACBUS2_26") (pintype "tri_state"))
    )
    (net (code "338") (name "unconnected-(U0911-ACBUS5-Pad29)") (class "Default")
      (node (ref "U0911") (pin "29") (pinfunction "ACBUS5_29") (pintype "tri_state"))
    )
    (net (code "339") (name "unconnected-(U0911-ACBUS6-Pad30)") (class "Default")
      (node (ref "U0911") (pin "30") (pinfunction "ACBUS6_30") (pintype "tri_state"))
    )
    (net (code "340") (name "unconnected-(U0911-ACBUS8-Pad32)") (class "Default")
      (node (ref "U0911") (pin "32") (pinfunction "ACBUS8_32") (pintype "tri_state"))
    )
    (net (code "341") (name "unconnected-(U0911-ACBUS9-Pad33)") (class "Default")
      (node (ref "U0911") (pin "33") (pinfunction "ACBUS9_33") (pintype "tri_state"))
    )
    (net (code "342") (name "unconnected-(U0911-EECLK-Pad44)") (class "Default")
      (node (ref "U0911") (pin "44") (pinfunction "EECLK_44") (pintype "output"))
    )
    (net (code "343") (name "unconnected-(U0911-EECS-Pad45)") (class "Default")
      (node (ref "U0911") (pin "45") (pinfunction "EECS_45") (pintype "bidirectional"))
    )
    (net (code "344") (name "unconnected-(U0911-OSCO-Pad2)") (class "Default")
      (node (ref "U0911") (pin "2") (pinfunction "OSCO_2") (pintype "passive"))
    )
    (net (code "345") (name "unconnected-(U1101-DC-Pad5)") (class "Default")
      (node (ref "U1101") (pin "5") (pinfunction "DC_5") (pintype "no_connect"))
    )
    (net (code "346") (name "unconnected-(U1211-PG-Pad7)") (class "Default")
      (node (ref "U1211") (pin "7") (pinfunction "PG_7") (pintype "open_collector"))
    )
    (net (code "347") (name "unconnected-(U1211-VIN_SW-Pad6)") (class "Default")
      (node (ref "U1211") (pin "6") (pinfunction "VIN_SW_6") (pintype "passive"))
    )
    (net (code "348") (name "unconnected-(X1331-Pad12)") (class "Default")
      (node (ref "X1331") (pin "12") (pinfunction "12_12") (pintype "passive"))
    )
  )
)
